# Open-Source_Control_Unitary_V2_R1.net
KiCad netlist of a schematic drawn in EAGLE
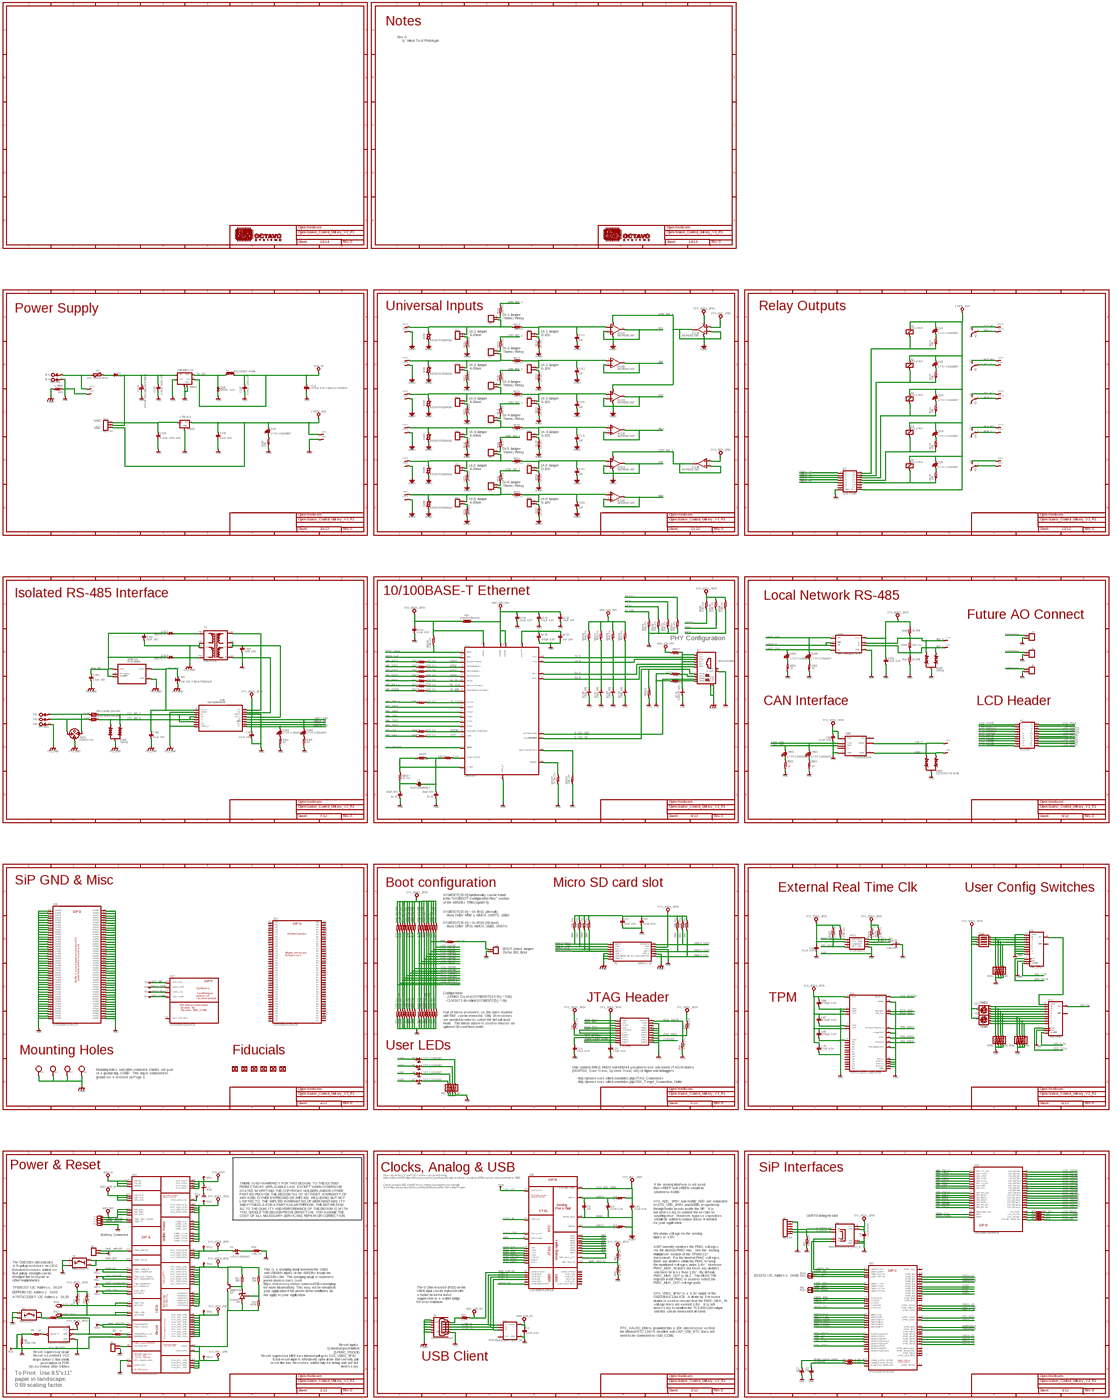
[diagram p0: schematic, sheet 1, overview]
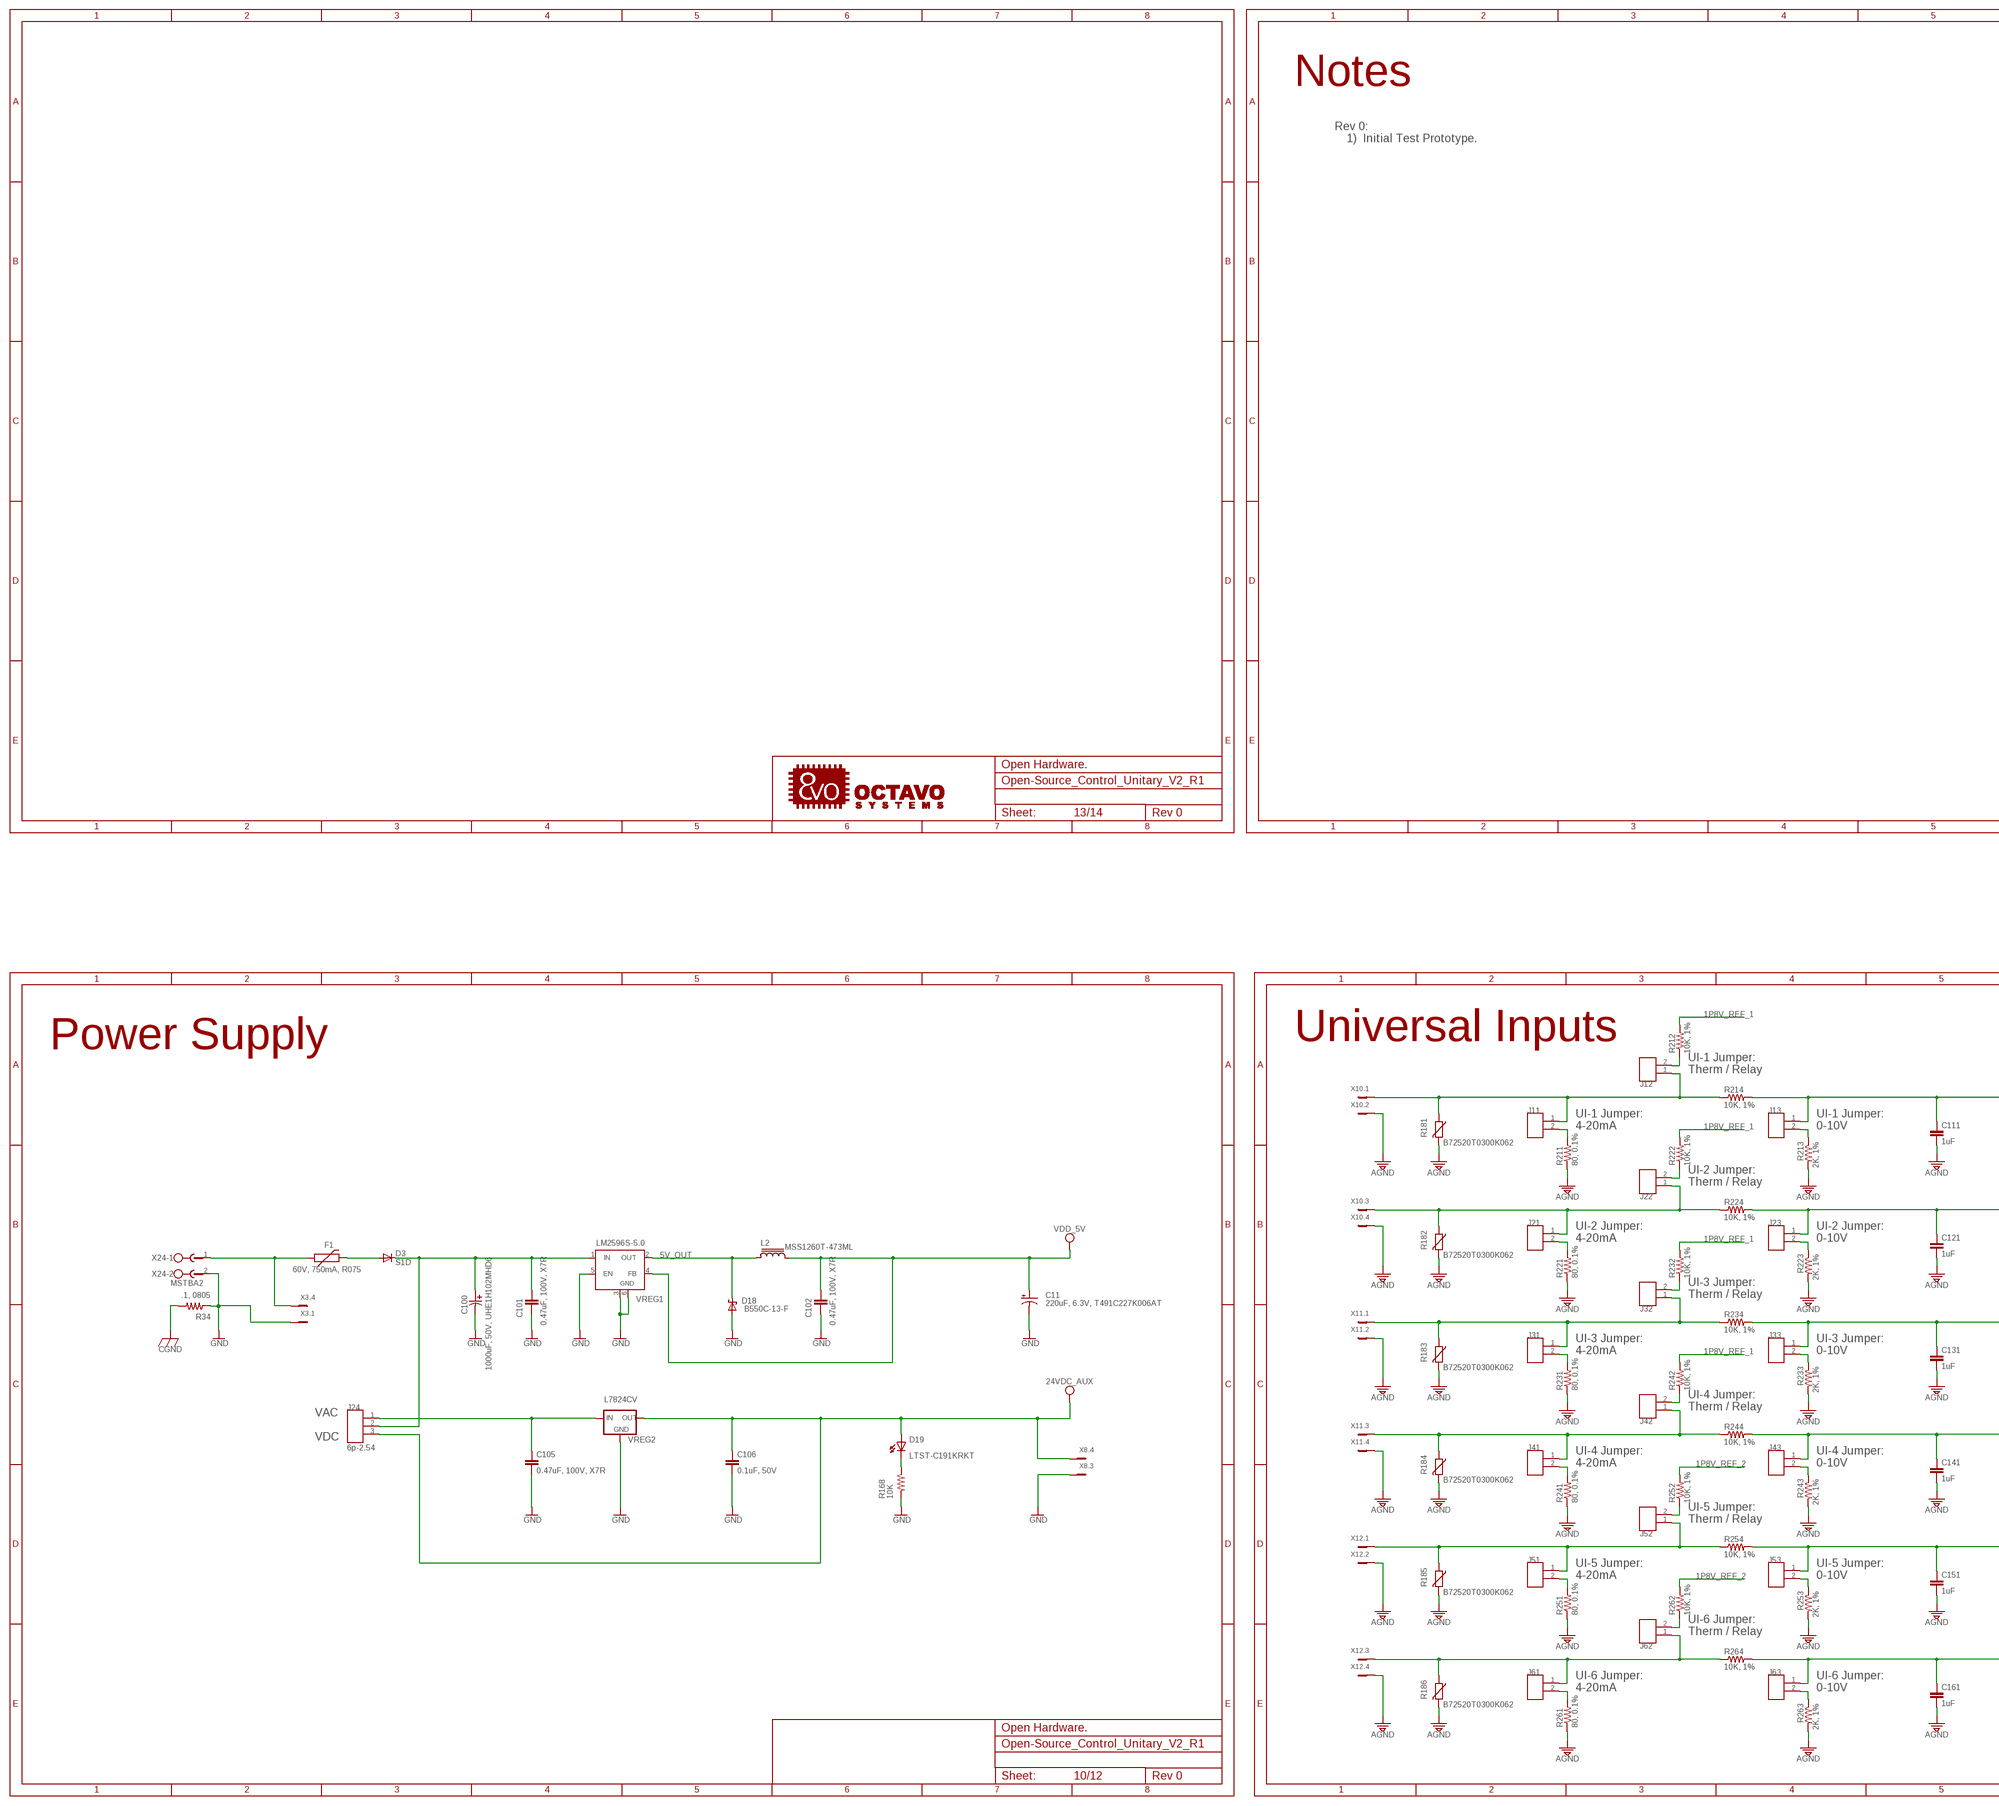
[diagram p1: schematic, sheet 1, part 1 of 6]
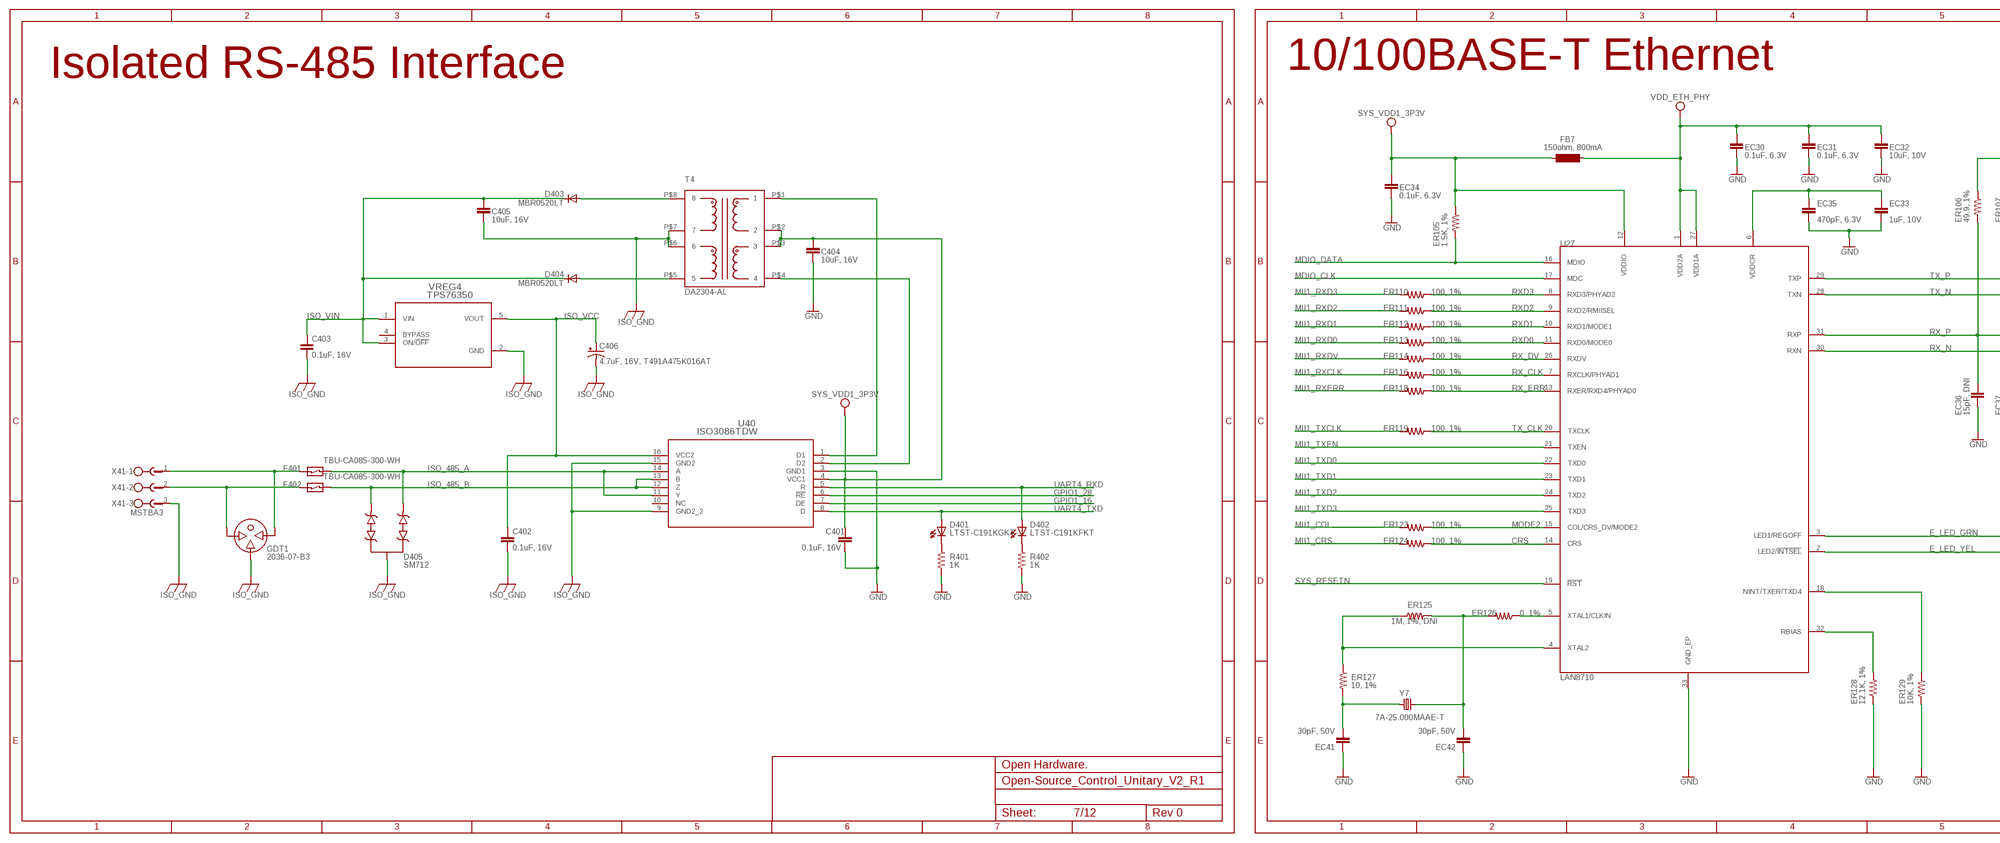
[diagram p2: schematic, sheet 1, part 2 of 6]
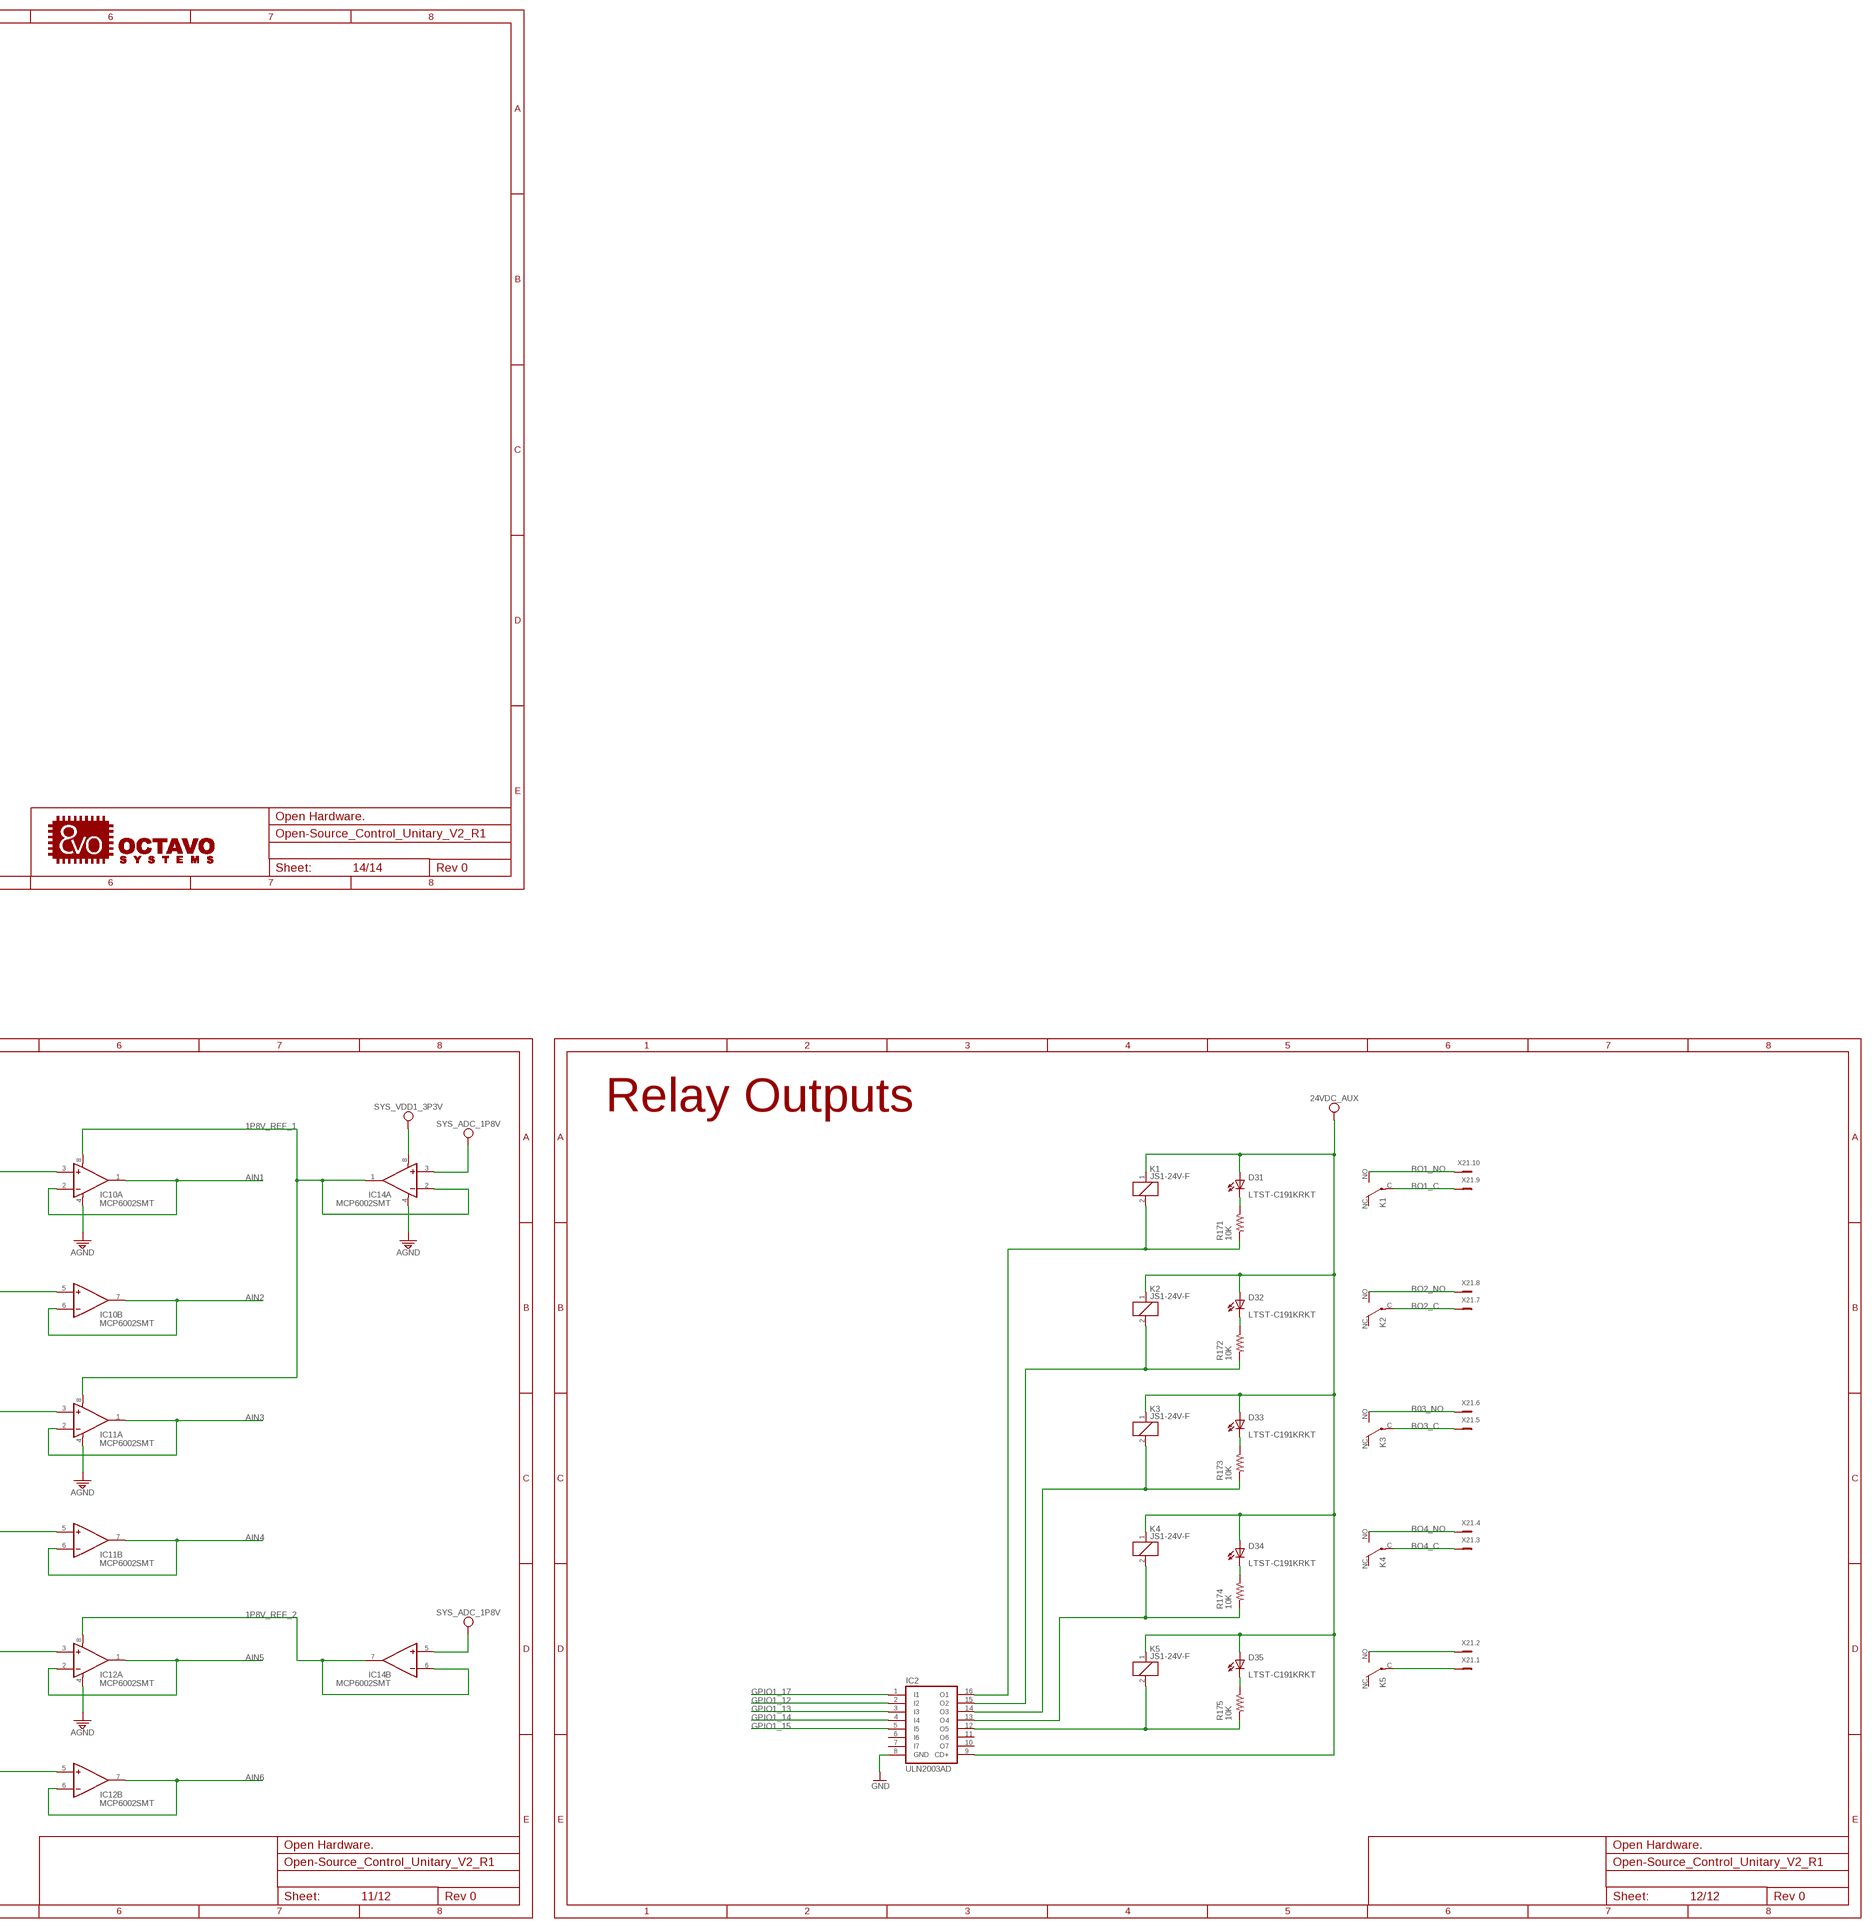
[diagram p3: schematic, sheet 1, part 3 of 6]
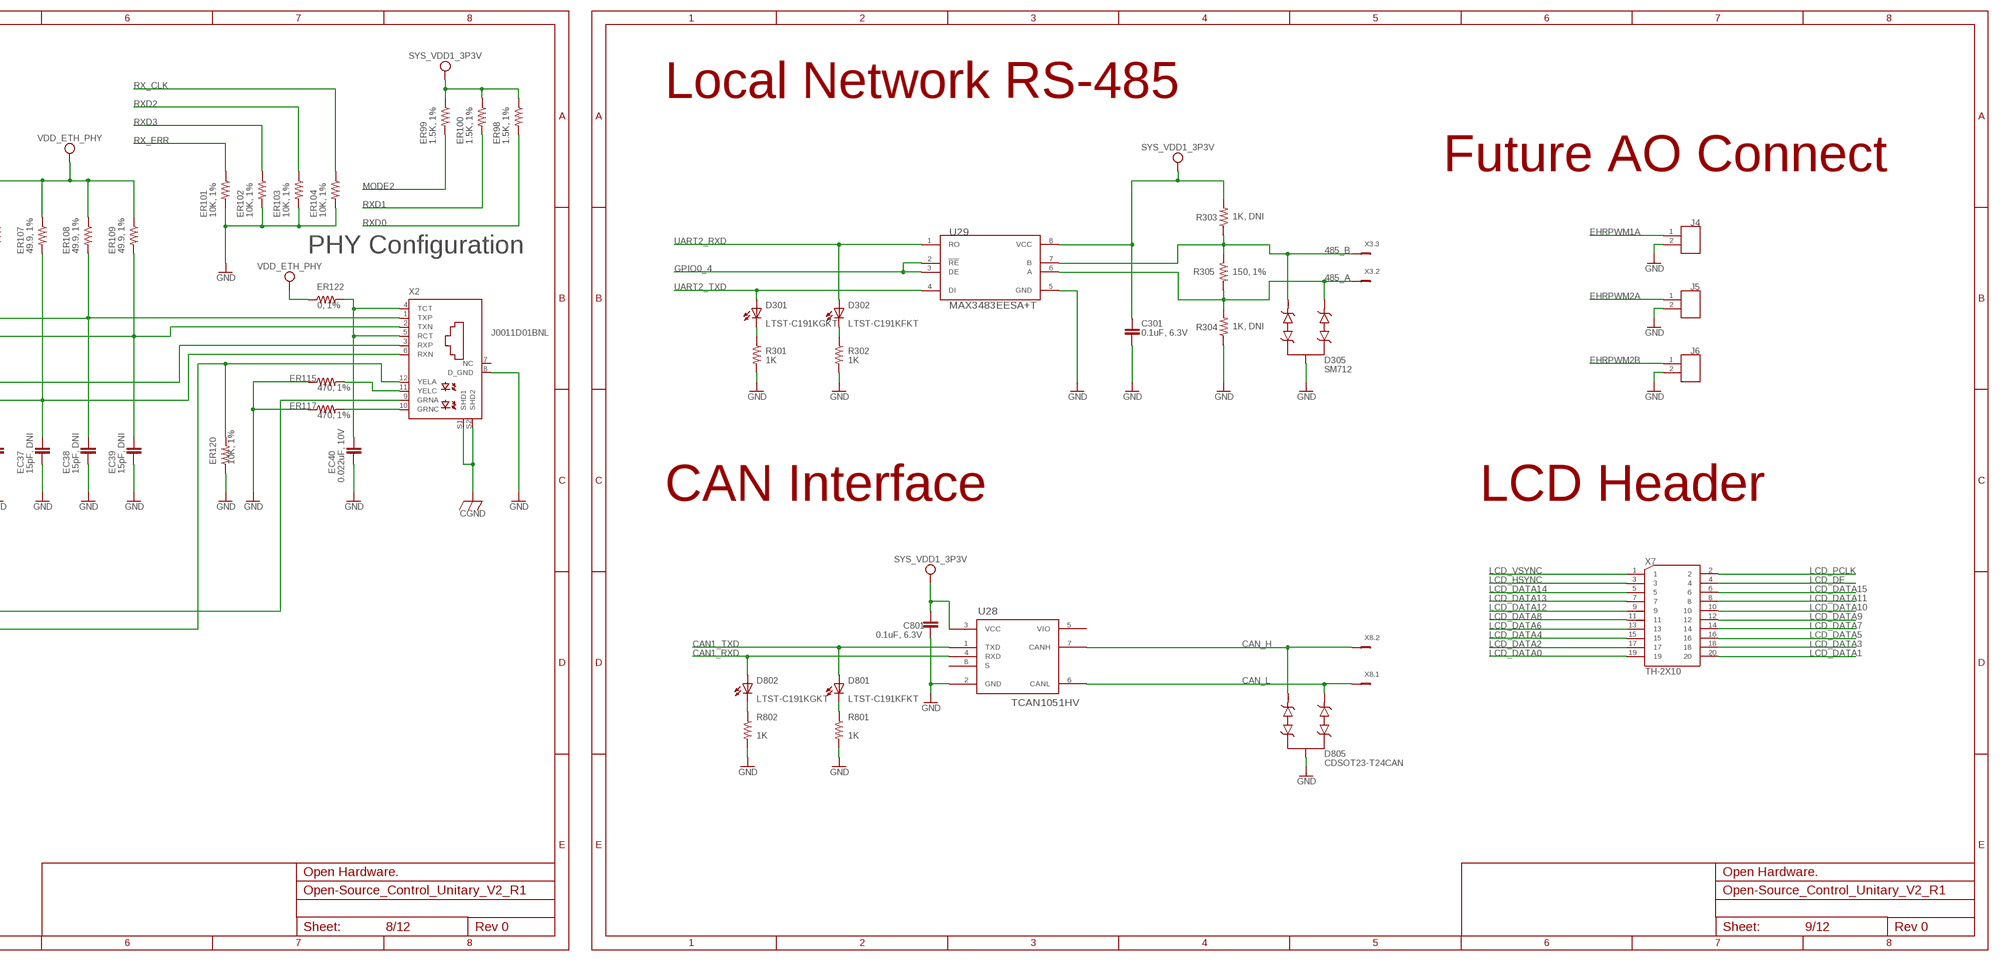
[diagram p4: schematic, sheet 1, part 4 of 6]
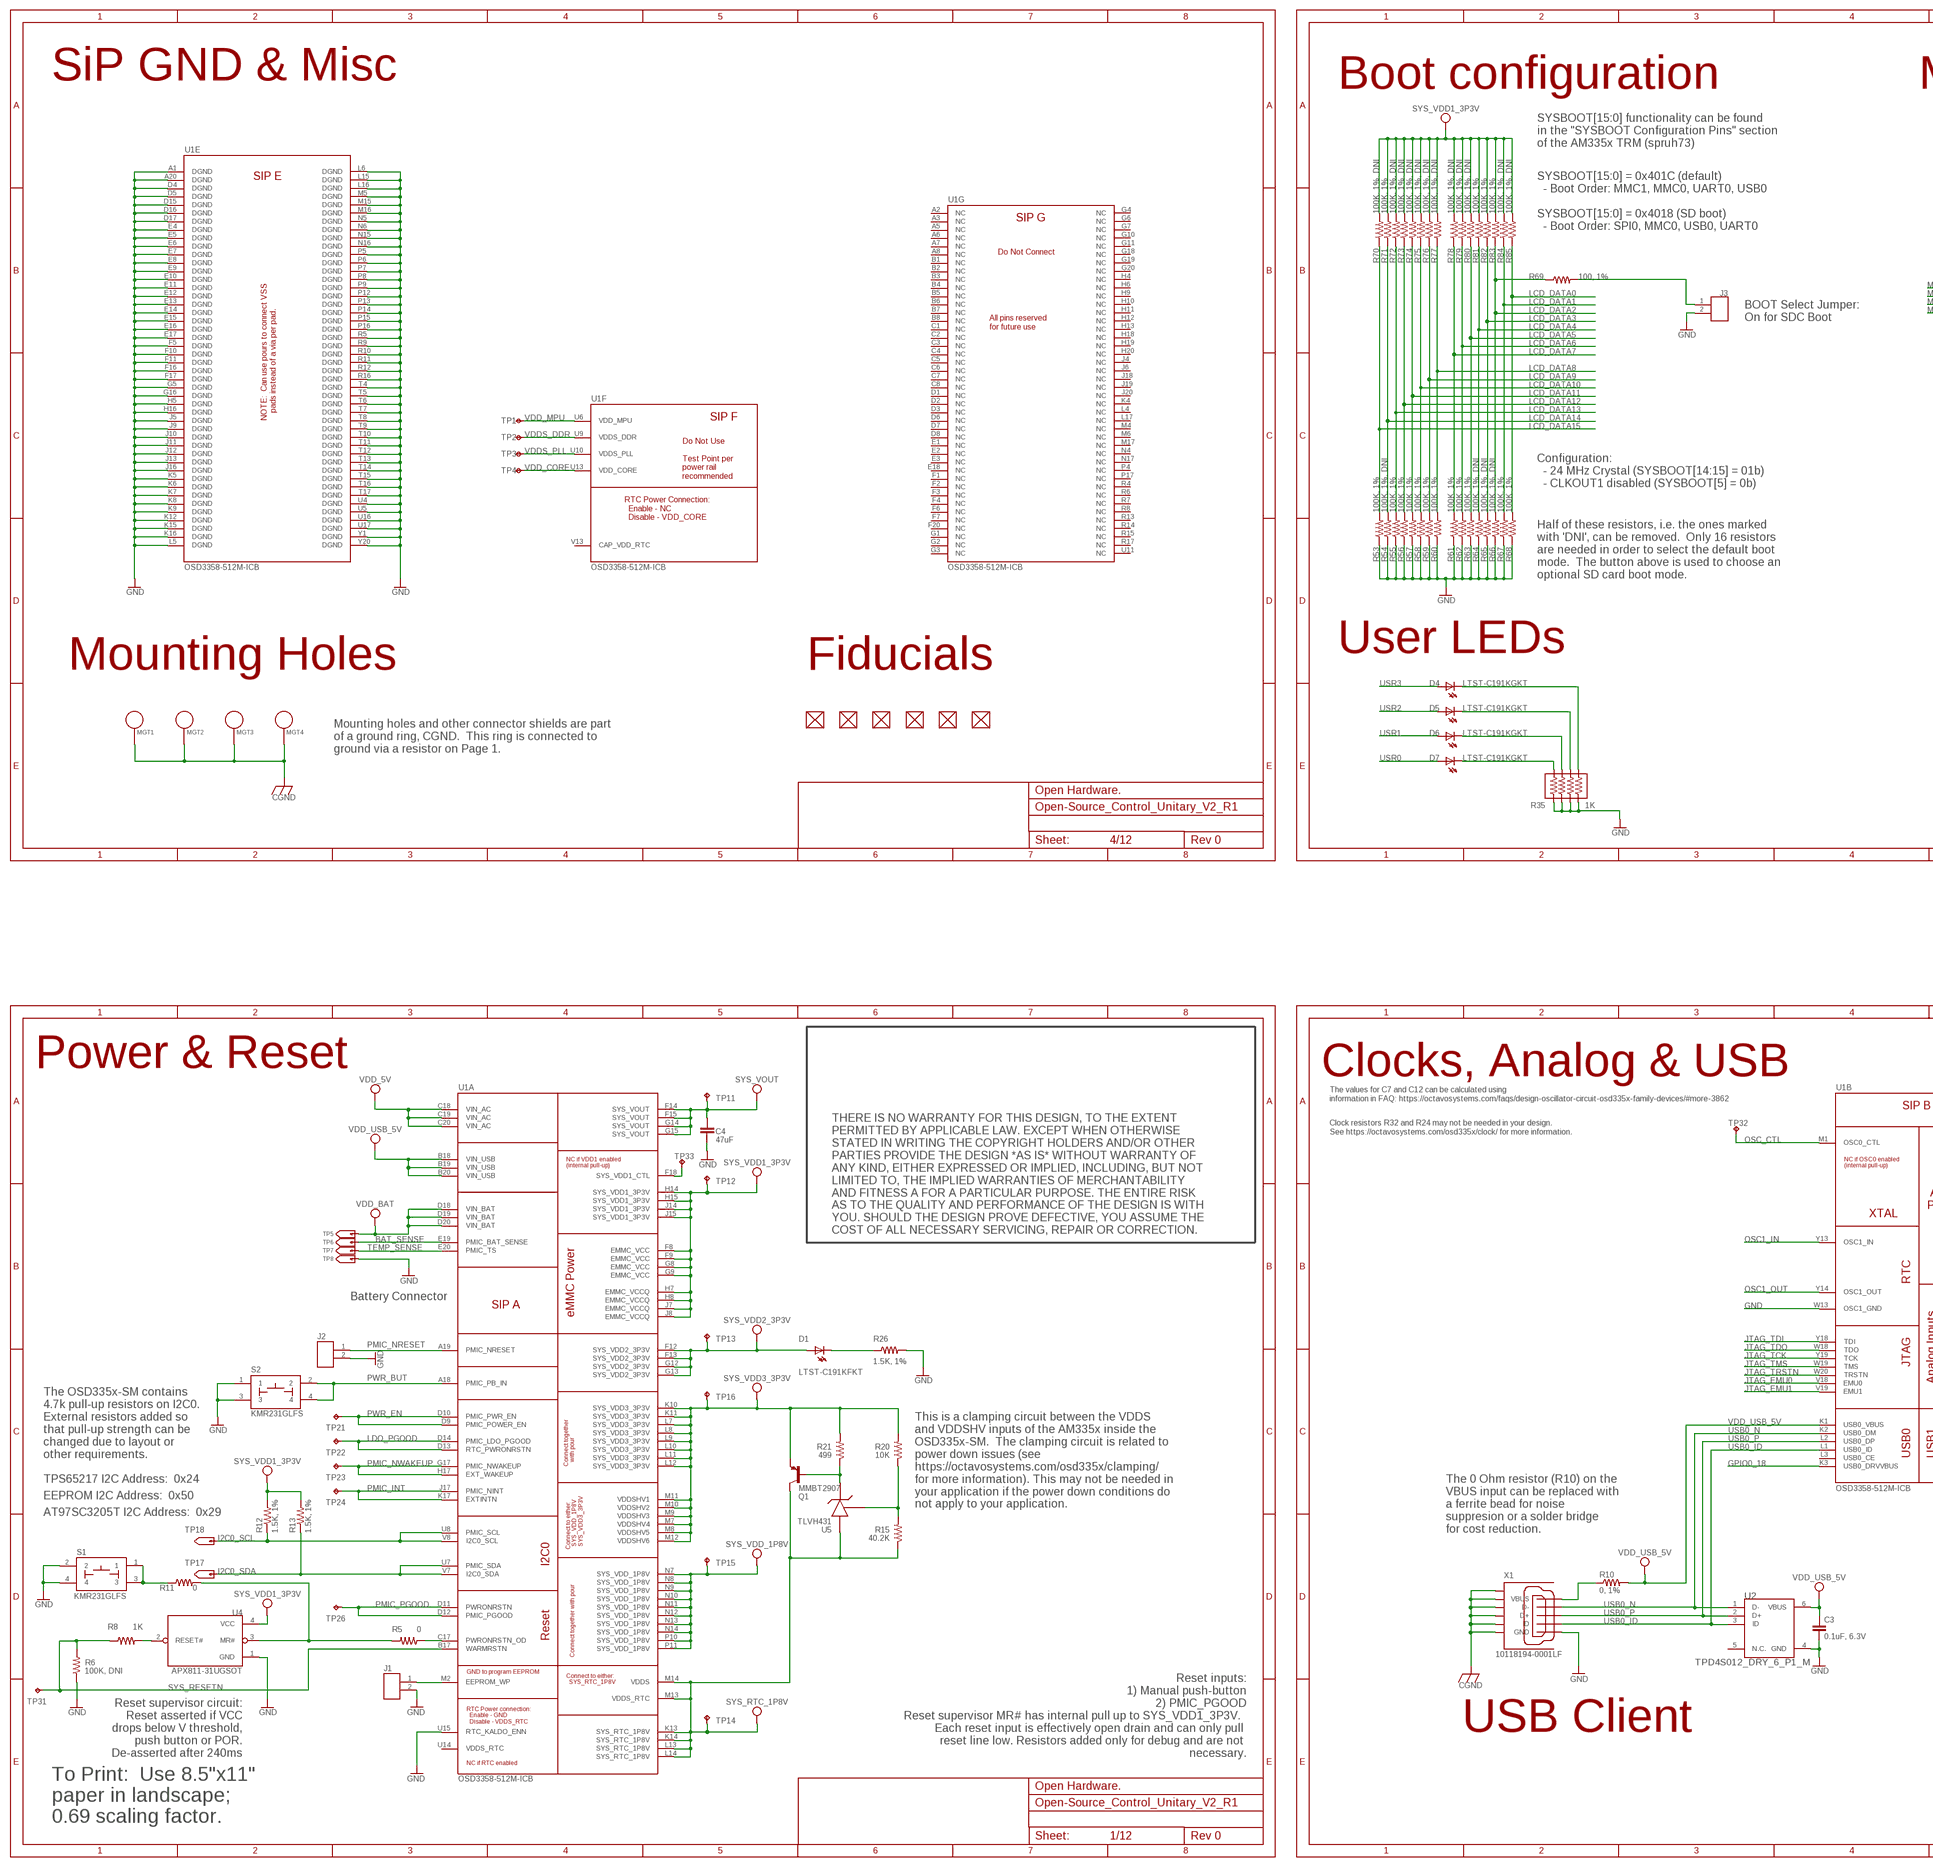
[diagram p5: schematic, sheet 1, part 5 of 6]
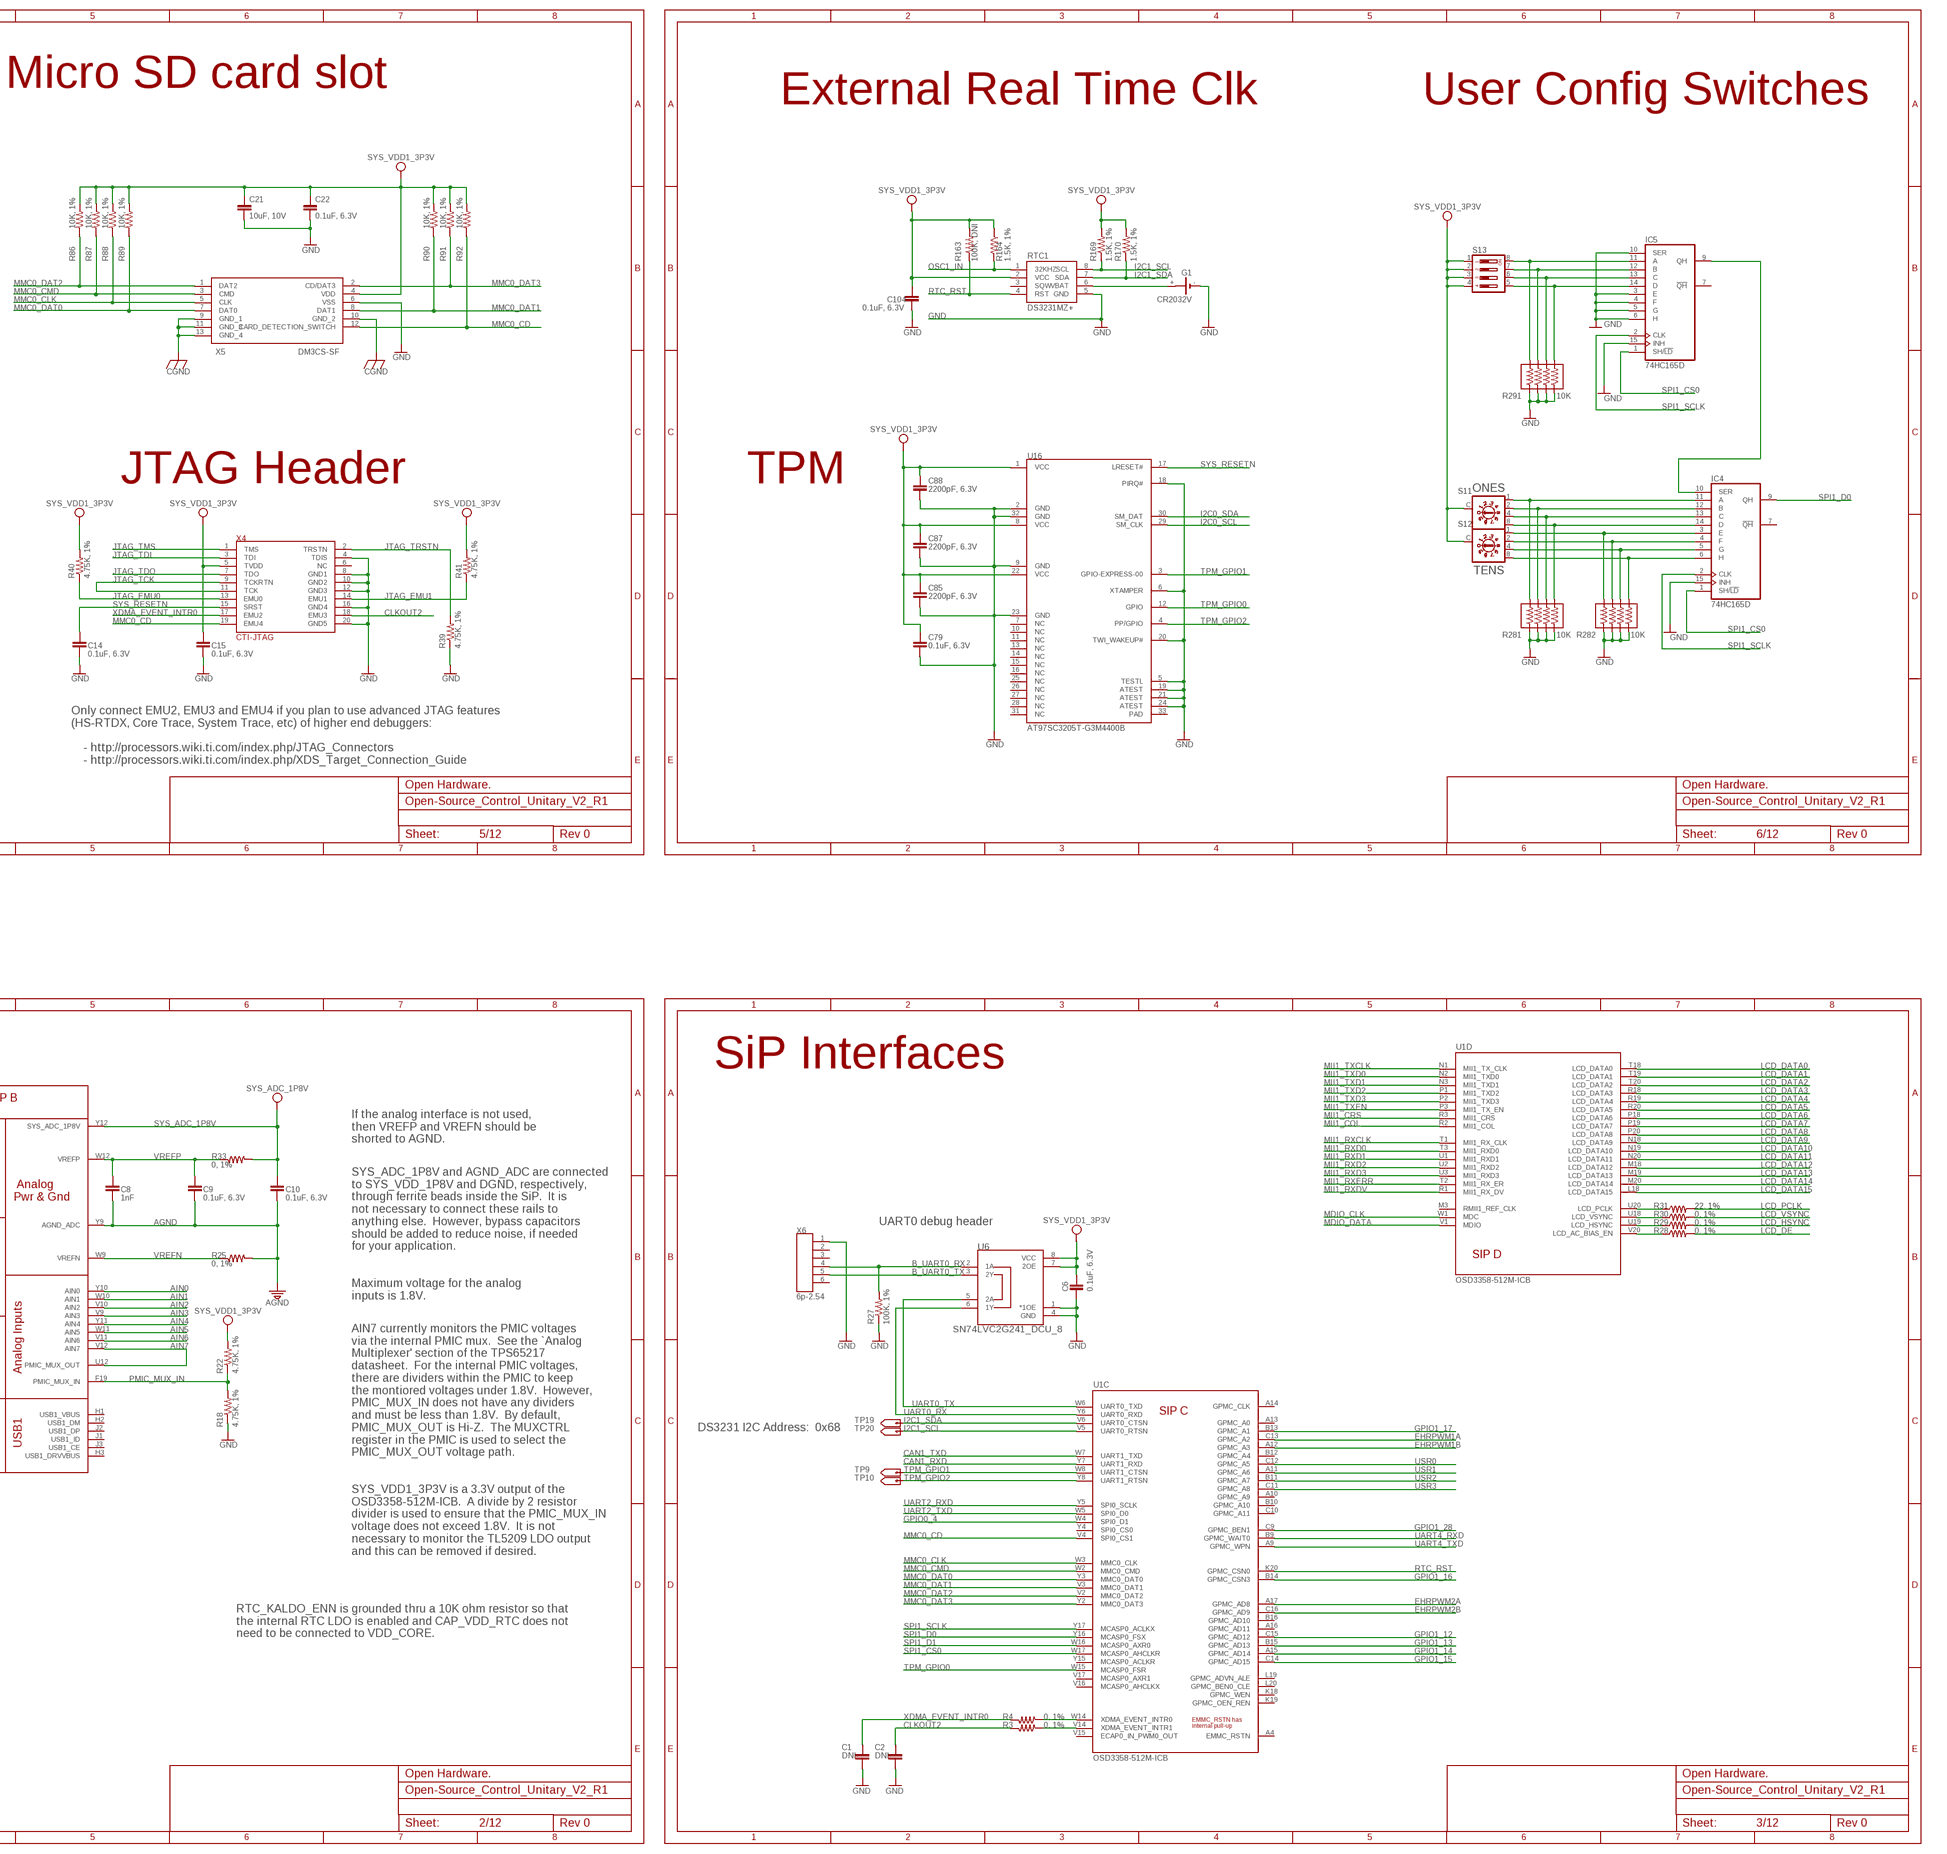
[diagram p6: schematic, sheet 1, part 6 of 6]

(export (version "E")
  (design (tool "Eeschema 10.0.6"))
  (components
    (comp (ref "C1")
      (value "DNI")
      (footprint "eagle-import:C0603")
      (libsource (lib "eagle-import") (part "CC0603"))
    )
    (comp (ref "C2")
      (value "DNI")
      (footprint "eagle-import:C0603")
      (libsource (lib "eagle-import") (part "CC0603"))
    )
    (comp (ref "C3")
      (value "0.1uF, 6.3V")
      (footprint "eagle-import:C0402")
      (libsource (lib "eagle-import") (part "CC0402"))
    )
    (comp (ref "C4")
      (value "47uF")
      (footprint "eagle-import:C0805")
      (libsource (lib "eagle-import") (part "CC0805"))
    )
    (comp (ref "C6")
      (value "0.1uF, 6.3V")
      (footprint "eagle-import:C0402")
      (libsource (lib "eagle-import") (part "CC0402"))
    )
    (comp (ref "C8")
      (value "1nF")
      (footprint "eagle-import:C0402")
      (libsource (lib "eagle-import") (part "CC0402"))
    )
    (comp (ref "C9")
      (value "0.1uF, 6.3V")
      (footprint "eagle-import:C0402")
      (libsource (lib "eagle-import") (part "CC0402"))
    )
    (comp (ref "C10")
      (value "0.1uF, 6.3V")
      (footprint "eagle-import:C0402")
      (libsource (lib "eagle-import") (part "CC0402"))
    )
    (comp (ref "C11")
      (value "220uF, 6.3V, T491C227K006AT")
      (footprint "eagle-import:C_6032-28R")
      (libsource (lib "eagle-import") (part "CPOL-USC/6032-28R"))
    )
    (comp (ref "C14")
      (value "0.1uF, 6.3V")
      (footprint "eagle-import:C0402")
      (libsource (lib "eagle-import") (part "CC0402"))
    )
    (comp (ref "C15")
      (value "0.1uF, 6.3V")
      (footprint "eagle-import:C0402")
      (libsource (lib "eagle-import") (part "CC0402"))
    )
    (comp (ref "C21")
      (value "10uF, 10V")
      (footprint "eagle-import:C0805")
      (libsource (lib "eagle-import") (part "CC0805"))
    )
    (comp (ref "C22")
      (value "0.1uF, 6.3V")
      (footprint "eagle-import:C0402")
      (libsource (lib "eagle-import") (part "CC0402"))
    )
    (comp (ref "C79")
      (value "0.1uF, 6.3V")
      (footprint "eagle-import:C0402")
      (libsource (lib "eagle-import") (part "CC0402"))
    )
    (comp (ref "C85")
      (value "2200pF, 6.3V")
      (footprint "eagle-import:C0402")
      (libsource (lib "eagle-import") (part "CC0402"))
    )
    (comp (ref "C87")
      (value "2200pF, 6.3V")
      (footprint "eagle-import:C0402")
      (libsource (lib "eagle-import") (part "CC0402"))
    )
    (comp (ref "C88")
      (value "2200pF, 6.3V")
      (footprint "eagle-import:C0402")
      (libsource (lib "eagle-import") (part "CC0402"))
    )
    (comp (ref "C100")
      (value "1000uF, 50V, UHE1H102MHD6")
      (footprint "eagle-import:PCAP_16X25-THRU-ELECT")
      (fields (field (name "MANUFACTURER_PART_NUMBER") "UHE1H102MHD6"))
      (libsource (lib "eagle-import") (part "UHE1H102MHD6"))
    )
    (comp (ref "C101")
      (value "0.47uF, 100V, X7R")
      (footprint "eagle-import:1206")
      (libsource (lib "eagle-import") (part "4.7UF-1206-16V-(+80/-20%)"))
    )
    (comp (ref "C102")
      (value "0.47uF, 100V, X7R")
      (footprint "eagle-import:1206")
      (libsource (lib "eagle-import") (part "4.7UF-1206-16V-(+80/-20%)"))
    )
    (comp (ref "C104")
      (value "0.1uF, 6.3V")
      (footprint "eagle-import:C0402")
      (libsource (lib "eagle-import") (part "CC0402"))
    )
    (comp (ref "C105")
      (value "0.47uF, 100V, X7R")
      (footprint "eagle-import:1206")
      (libsource (lib "eagle-import") (part "4.7UF-1206-16V-(+80/-20%)"))
    )
    (comp (ref "C106")
      (value "0.1uF, 50V")
      (footprint "eagle-import:1206")
      (libsource (lib "eagle-import") (part "4.7UF-1206-16V-(+80/-20%)"))
    )
    (comp (ref "C111")
      (value "1uF")
      (footprint "eagle-import:C0805")
      (libsource (lib "eagle-import") (part "CC0805"))
    )
    (comp (ref "C121")
      (value "1uF")
      (footprint "eagle-import:C0805")
      (libsource (lib "eagle-import") (part "CC0805"))
    )
    (comp (ref "C131")
      (value "1uF")
      (footprint "eagle-import:C0805")
      (libsource (lib "eagle-import") (part "CC0805"))
    )
    (comp (ref "C141")
      (value "1uF")
      (footprint "eagle-import:C0805")
      (libsource (lib "eagle-import") (part "CC0805"))
    )
    (comp (ref "C151")
      (value "1uF")
      (footprint "eagle-import:C0805")
      (libsource (lib "eagle-import") (part "CC0805"))
    )
    (comp (ref "C161")
      (value "1uF")
      (footprint "eagle-import:C0805")
      (libsource (lib "eagle-import") (part "CC0805"))
    )
    (comp (ref "C301")
      (value "0.1uF, 6.3V")
      (footprint "eagle-import:C0402")
      (libsource (lib "eagle-import") (part "CC0402"))
    )
    (comp (ref "C401")
      (value "0.1uF, 16V")
      (footprint "eagle-import:C0402")
      (libsource (lib "eagle-import") (part "CC0402"))
    )
    (comp (ref "C402")
      (value "0.1uF, 16V")
      (footprint "eagle-import:C0402")
      (libsource (lib "eagle-import") (part "CC0402"))
    )
    (comp (ref "C403")
      (value "0.1uF, 16V")
      (footprint "eagle-import:C0402")
      (libsource (lib "eagle-import") (part "CC0402"))
    )
    (comp (ref "C404")
      (value "10uF, 16V")
      (footprint "eagle-import:C0805")
      (libsource (lib "eagle-import") (part "CC0805"))
    )
    (comp (ref "C405")
      (value "10uF, 16V")
      (footprint "eagle-import:C0805")
      (libsource (lib "eagle-import") (part "CC0805"))
    )
    (comp (ref "C406")
      (value "4.7uF, 16V, T491A475K016AT")
      (footprint "eagle-import:A_3216-18R")
      (libsource (lib "eagle-import") (part "CPOL-USA/3216-18R"))
    )
    (comp (ref "C801")
      (value "0.1uF, 6.3V")
      (footprint "eagle-import:C0402")
      (libsource (lib "eagle-import") (part "CC0402"))
    )
    (comp (ref "D1")
      (value "LTST-C191KFKT")
      (footprint "eagle-import:EIA-STD")
      (libsource (lib "eagle-import") (part "LTST-C191KFKTLED_EIA-STD"))
    )
    (comp (ref "D3")
      (value "S1D")
      (footprint "eagle-import:SMA")
      (libsource (lib "eagle-import") (part "S1M"))
    )
    (comp (ref "D4")
      (value "LTST-C191KGKT")
      (footprint "eagle-import:EIA-STD")
      (libsource (lib "eagle-import") (part "LTST-C191KGKTLED_EIA-STD"))
    )
    (comp (ref "D5")
      (value "LTST-C191KGKT")
      (footprint "eagle-import:EIA-STD")
      (libsource (lib "eagle-import") (part "LTST-C191KGKTLED_EIA-STD"))
    )
    (comp (ref "D6")
      (value "LTST-C191KGKT")
      (footprint "eagle-import:EIA-STD")
      (libsource (lib "eagle-import") (part "LTST-C191KGKTLED_EIA-STD"))
    )
    (comp (ref "D7")
      (value "LTST-C191KGKT")
      (footprint "eagle-import:EIA-STD")
      (libsource (lib "eagle-import") (part "LTST-C191KGKTLED_EIA-STD"))
    )
    (comp (ref "D18")
      (value "B550C-13-F")
      (footprint "eagle-import:SMC")
      (libsource (lib "eagle-import") (part "B520C-13-F"))
    )
    (comp (ref "D19")
      (value "LTST-C191KRKT")
      (footprint "eagle-import:EIA-STD")
      (libsource (lib "eagle-import") (part "LTST-C191KRKTLED_EIA-STD"))
    )
    (comp (ref "D31")
      (value "LTST-C191KRKT")
      (footprint "eagle-import:EIA-STD")
      (libsource (lib "eagle-import") (part "LTST-C191KRKTLED_EIA-STD"))
    )
    (comp (ref "D32")
      (value "LTST-C191KRKT")
      (footprint "eagle-import:EIA-STD")
      (libsource (lib "eagle-import") (part "LTST-C191KRKTLED_EIA-STD"))
    )
    (comp (ref "D33")
      (value "LTST-C191KRKT")
      (footprint "eagle-import:EIA-STD")
      (libsource (lib "eagle-import") (part "LTST-C191KRKTLED_EIA-STD"))
    )
    (comp (ref "D34")
      (value "LTST-C191KRKT")
      (footprint "eagle-import:EIA-STD")
      (libsource (lib "eagle-import") (part "LTST-C191KRKTLED_EIA-STD"))
    )
    (comp (ref "D35")
      (value "LTST-C191KRKT")
      (footprint "eagle-import:EIA-STD")
      (libsource (lib "eagle-import") (part "LTST-C191KRKTLED_EIA-STD"))
    )
    (comp (ref "D301")
      (value "LTST-C191KGKT")
      (footprint "eagle-import:EIA-STD")
      (libsource (lib "eagle-import") (part "LTST-C191KGKTLED_EIA-STD"))
    )
    (comp (ref "D302")
      (value "LTST-C191KFKT")
      (footprint "eagle-import:EIA-STD")
      (libsource (lib "eagle-import") (part "LTST-C191KFKTLED_EIA-STD"))
    )
    (comp (ref "D305")
      (value "SM712")
      (footprint "eagle-import:SOT23-3")
      (libsource (lib "eagle-import") (part "SM712"))
    )
    (comp (ref "D401")
      (value "LTST-C191KGKT")
      (footprint "eagle-import:EIA-STD")
      (libsource (lib "eagle-import") (part "LTST-C191KGKTLED_EIA-STD"))
    )
    (comp (ref "D402")
      (value "LTST-C191KFKT")
      (footprint "eagle-import:EIA-STD")
      (libsource (lib "eagle-import") (part "LTST-C191KFKTLED_EIA-STD"))
    )
    (comp (ref "D403")
      (value "MBR0520LT")
      (footprint "eagle-import:SOD123")
      (libsource (lib "eagle-import") (part "MBR0520LT"))
    )
    (comp (ref "D404")
      (value "MBR0520LT")
      (footprint "eagle-import:SOD123")
      (libsource (lib "eagle-import") (part "MBR0520LT"))
    )
    (comp (ref "D405")
      (value "SM712")
      (footprint "eagle-import:SOT23-3")
      (libsource (lib "eagle-import") (part "SM712"))
    )
    (comp (ref "D801")
      (value "LTST-C191KFKT")
      (footprint "eagle-import:EIA-STD")
      (libsource (lib "eagle-import") (part "LTST-C191KFKTLED_EIA-STD"))
    )
    (comp (ref "D802")
      (value "LTST-C191KGKT")
      (footprint "eagle-import:EIA-STD")
      (libsource (lib "eagle-import") (part "LTST-C191KGKTLED_EIA-STD"))
    )
    (comp (ref "D805")
      (value "CDSOT23-T24CAN")
      (footprint "eagle-import:SOT23-3")
      (libsource (lib "eagle-import") (part "CDSOT23-T24CAN"))
    )
    (comp (ref "EC30")
      (value "0.1uF, 6.3V")
      (footprint "eagle-import:C0402")
      (libsource (lib "eagle-import") (part "CC0402"))
    )
    (comp (ref "EC31")
      (value "0.1uF, 6.3V")
      (footprint "eagle-import:C0402")
      (libsource (lib "eagle-import") (part "CC0402"))
    )
    (comp (ref "EC32")
      (value "10uF, 10V")
      (footprint "eagle-import:C0805")
      (libsource (lib "eagle-import") (part "CC0805"))
    )
    (comp (ref "EC33")
      (value "1uF, 10V")
      (footprint "eagle-import:C0402")
      (libsource (lib "eagle-import") (part "CC0402"))
    )
    (comp (ref "EC34")
      (value "0.1uF, 6.3V")
      (footprint "eagle-import:C0402")
      (libsource (lib "eagle-import") (part "CC0402"))
    )
    (comp (ref "EC35")
      (value "470pF, 6.3V")
      (footprint "eagle-import:C0402")
      (libsource (lib "eagle-import") (part "CC0402"))
    )
    (comp (ref "EC36")
      (value "15pF, DNI")
      (footprint "eagle-import:C0402")
      (libsource (lib "eagle-import") (part "CC0402"))
    )
    (comp (ref "EC37")
      (value "15pF, DNI")
      (footprint "eagle-import:C0402")
      (libsource (lib "eagle-import") (part "CC0402"))
    )
    (comp (ref "EC38")
      (value "15pF, DNI")
      (footprint "eagle-import:C0402")
      (libsource (lib "eagle-import") (part "CC0402"))
    )
    (comp (ref "EC39")
      (value "15pF, DNI")
      (footprint "eagle-import:C0402")
      (libsource (lib "eagle-import") (part "CC0402"))
    )
    (comp (ref "EC40")
      (value "0.022uF, 10V")
      (footprint "eagle-import:C0402")
      (libsource (lib "eagle-import") (part "CC0402"))
    )
    (comp (ref "EC41")
      (value "30pF, 50V")
      (footprint "eagle-import:C0402")
      (libsource (lib "eagle-import") (part "CC0402"))
    )
    (comp (ref "EC42")
      (value "30pF, 50V")
      (footprint "eagle-import:C0402")
      (libsource (lib "eagle-import") (part "CC0402"))
    )
    (comp (ref "ER98")
      (value "1.5K, 1%")
      (footprint "eagle-import:R0402")
      (libsource (lib "eagle-import") (part "OSD3358-SM-RED Platform_R-US_R0402"))
    )
    (comp (ref "ER99")
      (value "1.5K, 1%")
      (footprint "eagle-import:R0402")
      (libsource (lib "eagle-import") (part "OSD3358-SM-RED Platform_R-US_R0402"))
    )
    (comp (ref "ER100")
      (value "1.5K, 1%")
      (footprint "eagle-import:R0402")
      (libsource (lib "eagle-import") (part "OSD3358-SM-RED Platform_R-US_R0402"))
    )
    (comp (ref "ER101")
      (value "10K, 1%")
      (footprint "eagle-import:R0402")
      (libsource (lib "eagle-import") (part "OSD3358-SM-RED Platform_R-US_R0402"))
    )
    (comp (ref "ER102")
      (value "10K, 1%")
      (footprint "eagle-import:R0402")
      (libsource (lib "eagle-import") (part "OSD3358-SM-RED Platform_R-US_R0402"))
    )
    (comp (ref "ER103")
      (value "10K, 1%")
      (footprint "eagle-import:R0402")
      (libsource (lib "eagle-import") (part "OSD3358-SM-RED Platform_R-US_R0402"))
    )
    (comp (ref "ER104")
      (value "10K, 1%")
      (footprint "eagle-import:R0402")
      (libsource (lib "eagle-import") (part "OSD3358-SM-RED Platform_R-US_R0402"))
    )
    (comp (ref "ER105")
      (value "1.5K, 1%")
      (footprint "eagle-import:R0402")
      (libsource (lib "eagle-import") (part "OSD3358-SM-RED Platform_R-US_R0402"))
    )
    (comp (ref "ER106")
      (value "49.9, 1%")
      (footprint "eagle-import:R0402")
      (libsource (lib "eagle-import") (part "OSD3358-SM-RED Platform_R-US_R0402"))
    )
    (comp (ref "ER107")
      (value "49.9, 1%")
      (footprint "eagle-import:R0402")
      (libsource (lib "eagle-import") (part "OSD3358-SM-RED Platform_R-US_R0402"))
    )
    (comp (ref "ER108")
      (value "49.9, 1%")
      (footprint "eagle-import:R0402")
      (libsource (lib "eagle-import") (part "OSD3358-SM-RED Platform_R-US_R0402"))
    )
    (comp (ref "ER109")
      (value "49.9, 1%")
      (footprint "eagle-import:R0402")
      (libsource (lib "eagle-import") (part "OSD3358-SM-RED Platform_R-US_R0402"))
    )
    (comp (ref "ER110")
      (value "100, 1%")
      (footprint "eagle-import:R0402")
      (libsource (lib "eagle-import") (part "OSD3358-SM-RED Platform_R-US_R0402"))
    )
    (comp (ref "ER111")
      (value "100, 1%")
      (footprint "eagle-import:R0402")
      (libsource (lib "eagle-import") (part "OSD3358-SM-RED Platform_R-US_R0402"))
    )
    (comp (ref "ER112")
      (value "100, 1%")
      (footprint "eagle-import:R0402")
      (libsource (lib "eagle-import") (part "OSD3358-SM-RED Platform_R-US_R0402"))
    )
    (comp (ref "ER113")
      (value "100, 1%")
      (footprint "eagle-import:R0402")
      (libsource (lib "eagle-import") (part "OSD3358-SM-RED Platform_R-US_R0402"))
    )
    (comp (ref "ER114")
      (value "100, 1%")
      (footprint "eagle-import:R0402")
      (libsource (lib "eagle-import") (part "OSD3358-SM-RED Platform_R-US_R0402"))
    )
    (comp (ref "ER115")
      (value "470, 1%")
      (footprint "eagle-import:R0402")
      (libsource (lib "eagle-import") (part "OSD3358-SM-RED Platform_R-US_R0402"))
    )
    (comp (ref "ER116")
      (value "100, 1%")
      (footprint "eagle-import:R0402")
      (libsource (lib "eagle-import") (part "OSD3358-SM-RED Platform_R-US_R0402"))
    )
    (comp (ref "ER117")
      (value "470, 1%")
      (footprint "eagle-import:R0402")
      (libsource (lib "eagle-import") (part "OSD3358-SM-RED Platform_R-US_R0402"))
    )
    (comp (ref "ER118")
      (value "100, 1%")
      (footprint "eagle-import:R0402")
      (libsource (lib "eagle-import") (part "OSD3358-SM-RED Platform_R-US_R0402"))
    )
    (comp (ref "ER119")
      (value "100, 1%")
      (footprint "eagle-import:R0402")
      (libsource (lib "eagle-import") (part "OSD3358-SM-RED Platform_R-US_R0402"))
    )
    (comp (ref "ER120")
      (value "10K, 1%")
      (footprint "eagle-import:R0402")
      (libsource (lib "eagle-import") (part "OSD3358-SM-RED Platform_R-US_R0402"))
    )
    (comp (ref "ER122")
      (value "0, 1%")
      (footprint "eagle-import:R0402")
      (libsource (lib "eagle-import") (part "OSD3358-SM-RED Platform_R-US_R0402"))
    )
    (comp (ref "ER123")
      (value "100, 1%")
      (footprint "eagle-import:R0402")
      (libsource (lib "eagle-import") (part "OSD3358-SM-RED Platform_R-US_R0402"))
    )
    (comp (ref "ER124")
      (value "100, 1%")
      (footprint "eagle-import:R0402")
      (libsource (lib "eagle-import") (part "OSD3358-SM-RED Platform_R-US_R0402"))
    )
    (comp (ref "ER125")
      (value "1M, 1%, DNI")
      (footprint "eagle-import:R0402")
      (libsource (lib "eagle-import") (part "OSD3358-SM-RED Platform_R-US_R0402"))
    )
    (comp (ref "ER126")
      (value "0, 1%")
      (footprint "eagle-import:R0402")
      (libsource (lib "eagle-import") (part "OSD3358-SM-RED Platform_R-US_R0402"))
    )
    (comp (ref "ER127")
      (value "10, 1%")
      (footprint "eagle-import:R0402")
      (libsource (lib "eagle-import") (part "OSD3358-SM-RED Platform_R-US_R0402"))
    )
    (comp (ref "ER128")
      (value "12.1K, 1%")
      (footprint "eagle-import:R0402")
      (libsource (lib "eagle-import") (part "OSD3358-SM-RED Platform_R-US_R0402"))
    )
    (comp (ref "ER129")
      (value "10K, 1%")
      (footprint "eagle-import:R0402")
      (libsource (lib "eagle-import") (part "OSD3358-SM-RED Platform_R-US_R0402"))
    )
    (comp (ref "F1")
      (value "60V, 750mA, R075")
      (footprint "eagle-import:PTH")
      (libsource (lib "eagle-import") (part "PPTC_PTH"))
    )
    (comp (ref "F401")
      (value "TBU-CA085-300-WH")
      (footprint "eagle-import:TBU-CA")
      (libsource (lib "eagle-import") (part "TBU-CA085-300-WH"))
    )
    (comp (ref "F402")
      (value "TBU-CA085-300-WH")
      (footprint "eagle-import:TBU-CA")
      (libsource (lib "eagle-import") (part "TBU-CA085-300-WH"))
    )
    (comp (ref "FB7")
      (value "150ohm, 800mA")
      (footprint "eagle-import:C0805")
      (libsource (lib "eagle-import") (part "BLM21AG151SN1DFB_0805"))
    )
    (comp (ref "FUD1")
      (value "FIDUCIAL")
      (footprint "eagle-import:FIDUCIAL_40MIL")
      (libsource (lib "eagle-import") (part "FIDUCIAL"))
    )
    (comp (ref "FUD2")
      (value "FIDUCIAL")
      (footprint "eagle-import:FIDUCIAL_40MIL")
      (libsource (lib "eagle-import") (part "FIDUCIAL"))
    )
    (comp (ref "FUD3")
      (value "FIDUCIAL")
      (footprint "eagle-import:FIDUCIAL_40MIL")
      (libsource (lib "eagle-import") (part "FIDUCIAL"))
    )
    (comp (ref "FUD4")
      (value "FIDUCIAL")
      (footprint "eagle-import:FIDUCIAL_40MIL")
      (libsource (lib "eagle-import") (part "FIDUCIAL"))
    )
    (comp (ref "FUD5")
      (value "FIDUCIAL")
      (footprint "eagle-import:FIDUCIAL_40MIL")
      (libsource (lib "eagle-import") (part "FIDUCIAL"))
    )
    (comp (ref "FUD6")
      (value "FIDUCIAL")
      (footprint "eagle-import:FIDUCIAL_40MIL")
      (libsource (lib "eagle-import") (part "FIDUCIAL"))
    )
    (comp (ref "G1")
      (value "CR2032V")
      (footprint "eagle-import:CR2032V")
      (libsource (lib "eagle-import") (part "CR2032V"))
    )
    (comp (ref "GDT1")
      (value "2036-07-B3")
      (footprint "eagle-import:2036-XX-B3")
      (libsource (lib "eagle-import") (part "2036-09-B3"))
    )
    (comp (ref "IC2")
      (value "ULN2003AD")
      (footprint "eagle-import:SO16")
      (libsource (lib "eagle-import") (part "ULN2003AD"))
    )
    (comp (ref "IC4")
      (value "74HC165D")
      (footprint "eagle-import:SO16")
      (libsource (lib "eagle-import") (part "74165DHC"))
    )
    (comp (ref "IC5")
      (value "74HC165D")
      (footprint "eagle-import:SO16")
      (libsource (lib "eagle-import") (part "74165DHC"))
    )
    (comp (ref "IC10")
      (value "MCP6002SMT")
      (footprint "eagle-import:SOIC8")
      (libsource (lib "eagle-import") (part "MCP6002SMT"))
    )
    (comp (ref "IC11")
      (value "MCP6002SMT")
      (footprint "eagle-import:SOIC8")
      (libsource (lib "eagle-import") (part "MCP6002SMT"))
    )
    (comp (ref "IC12")
      (value "MCP6002SMT")
      (footprint "eagle-import:SOIC8")
      (libsource (lib "eagle-import") (part "MCP6002SMT"))
    )
    (comp (ref "IC14")
      (value "MCP6002SMT")
      (footprint "eagle-import:SOIC8")
      (libsource (lib "eagle-import") (part "MCP6002SMT"))
    )
    (comp (ref "J1")
      (value "826646-2")
      (footprint "eagle-import:H2-2.54")
      (libsource (lib "eagle-import") (part "826646-2"))
    )
    (comp (ref "J2")
      (value "826646-2")
      (footprint "eagle-import:H2-2.54")
      (libsource (lib "eagle-import") (part "OSD3358-SM-RED Platform_826646-2"))
    )
    (comp (ref "J3")
      (value "826646-2")
      (footprint "eagle-import:H2-2.54")
      (libsource (lib "eagle-import") (part "OSD3358-SM-RED Platform_826646-2"))
    )
    (comp (ref "J4")
      (value "826646-2")
      (footprint "eagle-import:H2-2.54")
      (libsource (lib "eagle-import") (part "OSD3358-SM-RED Platform_826646-2"))
    )
    (comp (ref "J5")
      (value "826646-2")
      (footprint "eagle-import:H2-2.54")
      (libsource (lib "eagle-import") (part "OSD3358-SM-RED Platform_826646-2"))
    )
    (comp (ref "J6")
      (value "826646-2")
      (footprint "eagle-import:H2-2.54")
      (libsource (lib "eagle-import") (part "OSD3358-SM-RED Platform_826646-2"))
    )
    (comp (ref "J11")
      (value "826646-2")
      (footprint "eagle-import:H2-2.54")
      (libsource (lib "eagle-import") (part "OSD3358-SM-RED Platform_826646-2"))
    )
    (comp (ref "J12")
      (value "826646-2")
      (footprint "eagle-import:H2-2.54")
      (libsource (lib "eagle-import") (part "OSD3358-SM-RED Platform_826646-2"))
    )
    (comp (ref "J13")
      (value "826646-2")
      (footprint "eagle-import:H2-2.54")
      (libsource (lib "eagle-import") (part "OSD3358-SM-RED Platform_826646-2"))
    )
    (comp (ref "J21")
      (value "826646-2")
      (footprint "eagle-import:H2-2.54")
      (libsource (lib "eagle-import") (part "OSD3358-SM-RED Platform_826646-2"))
    )
    (comp (ref "J22")
      (value "826646-2")
      (footprint "eagle-import:H2-2.54")
      (libsource (lib "eagle-import") (part "OSD3358-SM-RED Platform_826646-2"))
    )
    (comp (ref "J23")
      (value "826646-2")
      (footprint "eagle-import:H2-2.54")
      (libsource (lib "eagle-import") (part "OSD3358-SM-RED Platform_826646-2"))
    )
    (comp (ref "J24")
      (value "6p-2.54")
      (footprint "eagle-import:H3-2.54")
      (fields (field (name "MPN") "P125-1106A1BS116A1"))
      (libsource (lib "eagle-import") (part "826646-3"))
    )
    (comp (ref "J31")
      (value "826646-2")
      (footprint "eagle-import:H2-2.54")
      (libsource (lib "eagle-import") (part "OSD3358-SM-RED Platform_826646-2"))
    )
    (comp (ref "J32")
      (value "826646-2")
      (footprint "eagle-import:H2-2.54")
      (libsource (lib "eagle-import") (part "OSD3358-SM-RED Platform_826646-2"))
    )
    (comp (ref "J33")
      (value "826646-2")
      (footprint "eagle-import:H2-2.54")
      (libsource (lib "eagle-import") (part "OSD3358-SM-RED Platform_826646-2"))
    )
    (comp (ref "J41")
      (value "826646-2")
      (footprint "eagle-import:H2-2.54")
      (libsource (lib "eagle-import") (part "OSD3358-SM-RED Platform_826646-2"))
    )
    (comp (ref "J42")
      (value "826646-2")
      (footprint "eagle-import:H2-2.54")
      (libsource (lib "eagle-import") (part "OSD3358-SM-RED Platform_826646-2"))
    )
    (comp (ref "J43")
      (value "826646-2")
      (footprint "eagle-import:H2-2.54")
      (libsource (lib "eagle-import") (part "OSD3358-SM-RED Platform_826646-2"))
    )
    (comp (ref "J51")
      (value "826646-2")
      (footprint "eagle-import:H2-2.54")
      (libsource (lib "eagle-import") (part "OSD3358-SM-RED Platform_826646-2"))
    )
    (comp (ref "J52")
      (value "826646-2")
      (footprint "eagle-import:H2-2.54")
      (libsource (lib "eagle-import") (part "OSD3358-SM-RED Platform_826646-2"))
    )
    (comp (ref "J53")
      (value "826646-2")
      (footprint "eagle-import:H2-2.54")
      (libsource (lib "eagle-import") (part "OSD3358-SM-RED Platform_826646-2"))
    )
    (comp (ref "J61")
      (value "826646-2")
      (footprint "eagle-import:H2-2.54")
      (libsource (lib "eagle-import") (part "OSD3358-SM-RED Platform_826646-2"))
    )
    (comp (ref "J62")
      (value "826646-2")
      (footprint "eagle-import:H2-2.54")
      (libsource (lib "eagle-import") (part "OSD3358-SM-RED Platform_826646-2"))
    )
    (comp (ref "J63")
      (value "826646-2")
      (footprint "eagle-import:H2-2.54")
      (libsource (lib "eagle-import") (part "OSD3358-SM-RED Platform_826646-2"))
    )
    (comp (ref "K1")
      (value "JS1-24V-F")
      (footprint "eagle-import:JS-M")
      (fields (field (name "MF") "FARNELL") (field (name "MPN") "JSM1-12V-5"))
      (libsource (lib "eagle-import") (part "JS-M1-12V-5"))
    )
    (comp (ref "K2")
      (value "JS1-24V-F")
      (footprint "eagle-import:JS-M")
      (fields (field (name "MF") "FARNELL") (field (name "MPN") "JSM1-12V-5"))
      (libsource (lib "eagle-import") (part "JS-M1-12V-5"))
    )
    (comp (ref "K3")
      (value "JS1-24V-F")
      (footprint "eagle-import:JS-M")
      (fields (field (name "MF") "FARNELL") (field (name "MPN") "JSM1-12V-5"))
      (libsource (lib "eagle-import") (part "JS-M1-12V-5"))
    )
    (comp (ref "K4")
      (value "JS1-24V-F")
      (footprint "eagle-import:JS-M")
      (fields (field (name "MF") "FARNELL") (field (name "MPN") "JSM1-12V-5"))
      (libsource (lib "eagle-import") (part "JS-M1-12V-5"))
    )
    (comp (ref "K5")
      (value "JS1-24V-F")
      (footprint "eagle-import:JS-M")
      (fields (field (name "MF") "FARNELL") (field (name "MPN") "JSM1-12V-5"))
      (libsource (lib "eagle-import") (part "JS-M1-12V-5"))
    )
    (comp (ref "L2")
      (value "MSS1260T-473ML")
      (footprint "eagle-import:MSS1260")
      (libsource (lib "eagle-import") (part "MSS1260"))
    )
    (comp (ref "MGT1")
      (value "MOUNTING_HOLE")
      (footprint "eagle-import:MOUNTING_HOLE")
      (libsource (lib "eagle-import") (part "MOUNTING_HOLE"))
    )
    (comp (ref "MGT2")
      (value "MOUNTING_HOLE")
      (footprint "eagle-import:MOUNTING_HOLE")
      (libsource (lib "eagle-import") (part "MOUNTING_HOLE"))
    )
    (comp (ref "MGT3")
      (value "MOUNTING_HOLE")
      (footprint "eagle-import:MOUNTING_HOLE")
      (libsource (lib "eagle-import") (part "MOUNTING_HOLE"))
    )
    (comp (ref "MGT4")
      (value "MOUNTING_HOLE")
      (footprint "eagle-import:MOUNTING_HOLE")
      (libsource (lib "eagle-import") (part "MOUNTING_HOLE"))
    )
    (comp (ref "Q1")
      (value "MMBT2907")
      (footprint "eagle-import:SOT23-BEC")
      (libsource (lib "eagle-import") (part "MMBT2907SMD"))
    )
    (comp (ref "R3")
      (value "0, 1%")
      (footprint "eagle-import:R0402")
      (libsource (lib "eagle-import") (part "OSD3358-SM-RED Platform_R-US_R0402"))
    )
    (comp (ref "R4")
      (value "0, 1%")
      (footprint "eagle-import:R0402")
      (libsource (lib "eagle-import") (part "OSD3358-SM-RED Platform_R-US_R0402"))
    )
    (comp (ref "R5")
      (value "0")
      (footprint "eagle-import:R0402")
      (libsource (lib "eagle-import") (part "R-US_R0402"))
    )
    (comp (ref "R6")
      (value "100K, DNI")
      (footprint "eagle-import:R0402")
      (libsource (lib "eagle-import") (part "R-US_R0402"))
    )
    (comp (ref "R8")
      (value "1K")
      (footprint "eagle-import:R0402")
      (libsource (lib "eagle-import") (part "R-US_R0402"))
    )
    (comp (ref "R10")
      (value "0, 1%")
      (footprint "eagle-import:R0805")
      (libsource (lib "eagle-import") (part "OSD3358-SM-RED Platform_R-US_R0805"))
    )
    (comp (ref "R11")
      (value "0")
      (footprint "eagle-import:R0402")
      (libsource (lib "eagle-import") (part "R-US_R0402"))
    )
    (comp (ref "R12")
      (value "1.5K, 1%")
      (footprint "eagle-import:R0402")
      (libsource (lib "eagle-import") (part "OSD3358-SM-RED Platform_R-US_R0402"))
    )
    (comp (ref "R13")
      (value "1.5K, 1%")
      (footprint "eagle-import:R0402")
      (libsource (lib "eagle-import") (part "OSD3358-SM-RED Platform_R-US_R0402"))
    )
    (comp (ref "R15")
      (value "40.2K")
      (footprint "eagle-import:R0402")
      (libsource (lib "eagle-import") (part "R-US_R0402"))
    )
    (comp (ref "R18")
      (value "4.75K, 1%")
      (footprint "eagle-import:R0402")
      (libsource (lib "eagle-import") (part "OSD3358-SM-RED Platform_R-US_R0402"))
    )
    (comp (ref "R20")
      (value "10K")
      (footprint "eagle-import:R0402")
      (libsource (lib "eagle-import") (part "R-US_R0402"))
    )
    (comp (ref "R21")
      (value "499")
      (footprint "eagle-import:R0402")
      (libsource (lib "eagle-import") (part "R-US_R0402"))
    )
    (comp (ref "R22")
      (value "4.75K, 1%")
      (footprint "eagle-import:R0402")
      (libsource (lib "eagle-import") (part "OSD3358-SM-RED Platform_R-US_R0402"))
    )
    (comp (ref "R25")
      (value "0, 1%")
      (footprint "eagle-import:R0402")
      (libsource (lib "eagle-import") (part "OSD3358-SM-RED Platform_R-US_R0402"))
    )
    (comp (ref "R26")
      (value "1.5K, 1%")
      (footprint "eagle-import:R0402")
      (libsource (lib "eagle-import") (part "OSD3358-SM-RED Platform_R-US_R0402"))
    )
    (comp (ref "R27")
      (value "100K, 1%")
      (footprint "eagle-import:R0402")
      (libsource (lib "eagle-import") (part "OSD3358-SM-RED Platform_R-US_R0402"))
    )
    (comp (ref "R28")
      (value "0, 1%")
      (footprint "eagle-import:R0402")
      (libsource (lib "eagle-import") (part "OSD3358-SM-RED Platform_R-US_R0402"))
    )
    (comp (ref "R29")
      (value "0, 1%")
      (footprint "eagle-import:R0402")
      (libsource (lib "eagle-import") (part "OSD3358-SM-RED Platform_R-US_R0402"))
    )
    (comp (ref "R30")
      (value "0, 1%")
      (footprint "eagle-import:R0402")
      (libsource (lib "eagle-import") (part "OSD3358-SM-RED Platform_R-US_R0402"))
    )
    (comp (ref "R31")
      (value "22, 1%")
      (footprint "eagle-import:R0402")
      (libsource (lib "eagle-import") (part "OSD3358-SM-RED Platform_R-US_R0402"))
    )
    (comp (ref "R33")
      (value "0, 1%")
      (footprint "eagle-import:R0402")
      (libsource (lib "eagle-import") (part "OSD3358-SM-RED Platform_R-US_R0402"))
    )
    (comp (ref "R34")
      (value ".1, 0805")
      (footprint "eagle-import:R0805")
      (libsource (lib "eagle-import") (part "OSD3358-SM-RED Platform_R-US_R0805"))
    )
    (comp (ref "R35")
      (value "1K")
      (footprint "eagle-import:RN0804")
      (libsource (lib "eagle-import") (part "RESISTOR.NETWORK-(4)"))
    )
    (comp (ref "R39")
      (value "4.75K, 1%")
      (footprint "eagle-import:R0402")
      (libsource (lib "eagle-import") (part "OSD3358-SM-RED Platform_R-US_R0402"))
    )
    (comp (ref "R40")
      (value "4.75K, 1%")
      (footprint "eagle-import:R0402")
      (libsource (lib "eagle-import") (part "OSD3358-SM-RED Platform_R-US_R0402"))
    )
    (comp (ref "R41")
      (value "4.75K, 1%")
      (footprint "eagle-import:R0402")
      (libsource (lib "eagle-import") (part "OSD3358-SM-RED Platform_R-US_R0402"))
    )
    (comp (ref "R53")
      (value "100K, 1%")
      (footprint "eagle-import:R0402")
      (libsource (lib "eagle-import") (part "OSD3358-SM-RED Platform_R-US_R0402"))
    )
    (comp (ref "R54")
      (value "100K, 1%, DNI")
      (footprint "eagle-import:R0402")
      (libsource (lib "eagle-import") (part "OSD3358-SM-RED Platform_R-US_R0402"))
    )
    (comp (ref "R55")
      (value "100K, 1%")
      (footprint "eagle-import:R0402")
      (libsource (lib "eagle-import") (part "OSD3358-SM-RED Platform_R-US_R0402"))
    )
    (comp (ref "R56")
      (value "100K, 1%")
      (footprint "eagle-import:R0402")
      (libsource (lib "eagle-import") (part "OSD3358-SM-RED Platform_R-US_R0402"))
    )
    (comp (ref "R57")
      (value "100K, 1%")
      (footprint "eagle-import:R0402")
      (libsource (lib "eagle-import") (part "OSD3358-SM-RED Platform_R-US_R0402"))
    )
    (comp (ref "R58")
      (value "100K, 1%")
      (footprint "eagle-import:R0402")
      (libsource (lib "eagle-import") (part "OSD3358-SM-RED Platform_R-US_R0402"))
    )
    (comp (ref "R59")
      (value "100K, 1%")
      (footprint "eagle-import:R0402")
      (libsource (lib "eagle-import") (part "OSD3358-SM-RED Platform_R-US_R0402"))
    )
    (comp (ref "R60")
      (value "100K, 1%")
      (footprint "eagle-import:R0402")
      (libsource (lib "eagle-import") (part "OSD3358-SM-RED Platform_R-US_R0402"))
    )
    (comp (ref "R61")
      (value "100K, 1%")
      (footprint "eagle-import:R0402")
      (libsource (lib "eagle-import") (part "OSD3358-SM-RED Platform_R-US_R0402"))
    )
    (comp (ref "R62")
      (value "100K, 1%")
      (footprint "eagle-import:R0402")
      (libsource (lib "eagle-import") (part "OSD3358-SM-RED Platform_R-US_R0402"))
    )
    (comp (ref "R63")
      (value "100K, 1%")
      (footprint "eagle-import:R0402")
      (libsource (lib "eagle-import") (part "OSD3358-SM-RED Platform_R-US_R0402"))
    )
    (comp (ref "R64")
      (value "100K, 1%, DNI")
      (footprint "eagle-import:R0402")
      (libsource (lib "eagle-import") (part "OSD3358-SM-RED Platform_R-US_R0402"))
    )
    (comp (ref "R65")
      (value "100K, 1%, DNI")
      (footprint "eagle-import:R0402")
      (libsource (lib "eagle-import") (part "OSD3358-SM-RED Platform_R-US_R0402"))
    )
    (comp (ref "R66")
      (value "100K, 1%, DNI")
      (footprint "eagle-import:R0402")
      (libsource (lib "eagle-import") (part "OSD3358-SM-RED Platform_R-US_R0402"))
    )
    (comp (ref "R67")
      (value "100K, 1%")
      (footprint "eagle-import:R0402")
      (libsource (lib "eagle-import") (part "OSD3358-SM-RED Platform_R-US_R0402"))
    )
    (comp (ref "R68")
      (value "100K, 1%")
      (footprint "eagle-import:R0402")
      (libsource (lib "eagle-import") (part "OSD3358-SM-RED Platform_R-US_R0402"))
    )
    (comp (ref "R69")
      (value "100, 1%")
      (footprint "eagle-import:R0402")
      (libsource (lib "eagle-import") (part "OSD3358-SM-RED Platform_R-US_R0402"))
    )
    (comp (ref "R70")
      (value "100K, 1%, DNI")
      (footprint "eagle-import:R0402")
      (libsource (lib "eagle-import") (part "OSD3358-SM-RED Platform_R-US_R0402"))
    )
    (comp (ref "R71")
      (value "100K, 1%")
      (footprint "eagle-import:R0402")
      (libsource (lib "eagle-import") (part "OSD3358-SM-RED Platform_R-US_R0402"))
    )
    (comp (ref "R72")
      (value "100K, 1%, DNI")
      (footprint "eagle-import:R0402")
      (libsource (lib "eagle-import") (part "OSD3358-SM-RED Platform_R-US_R0402"))
    )
    (comp (ref "R73")
      (value "100K, 1%, DNI")
      (footprint "eagle-import:R0402")
      (libsource (lib "eagle-import") (part "OSD3358-SM-RED Platform_R-US_R0402"))
    )
    (comp (ref "R74")
      (value "100K, 1%, DNI")
      (footprint "eagle-import:R0402")
      (libsource (lib "eagle-import") (part "OSD3358-SM-RED Platform_R-US_R0402"))
    )
    (comp (ref "R75")
      (value "100K, 1%, DNI")
      (footprint "eagle-import:R0402")
      (libsource (lib "eagle-import") (part "OSD3358-SM-RED Platform_R-US_R0402"))
    )
    (comp (ref "R76")
      (value "100K, 1%, DNI")
      (footprint "eagle-import:R0402")
      (libsource (lib "eagle-import") (part "OSD3358-SM-RED Platform_R-US_R0402"))
    )
    (comp (ref "R77")
      (value "100K, 1%, DNI")
      (footprint "eagle-import:R0402")
      (libsource (lib "eagle-import") (part "OSD3358-SM-RED Platform_R-US_R0402"))
    )
    (comp (ref "R78")
      (value "100K, 1%, DNI")
      (footprint "eagle-import:R0402")
      (libsource (lib "eagle-import") (part "OSD3358-SM-RED Platform_R-US_R0402"))
    )
    (comp (ref "R79")
      (value "100K, 1%, DNI")
      (footprint "eagle-import:R0402")
      (libsource (lib "eagle-import") (part "OSD3358-SM-RED Platform_R-US_R0402"))
    )
    (comp (ref "R80")
      (value "100K, 1%, DNI")
      (footprint "eagle-import:R0402")
      (libsource (lib "eagle-import") (part "OSD3358-SM-RED Platform_R-US_R0402"))
    )
    (comp (ref "R81")
      (value "100K, 1%")
      (footprint "eagle-import:R0402")
      (libsource (lib "eagle-import") (part "OSD3358-SM-RED Platform_R-US_R0402"))
    )
    (comp (ref "R82")
      (value "100K, 1%")
      (footprint "eagle-import:R0402")
      (libsource (lib "eagle-import") (part "OSD3358-SM-RED Platform_R-US_R0402"))
    )
    (comp (ref "R83")
      (value "100K, 1%")
      (footprint "eagle-import:R0402")
      (libsource (lib "eagle-import") (part "OSD3358-SM-RED Platform_R-US_R0402"))
    )
    (comp (ref "R84")
      (value "100K, 1%, DNI")
      (footprint "eagle-import:R0402")
      (libsource (lib "eagle-import") (part "OSD3358-SM-RED Platform_R-US_R0402"))
    )
    (comp (ref "R85")
      (value "100K, 1%, DNI")
      (footprint "eagle-import:R0402")
      (libsource (lib "eagle-import") (part "OSD3358-SM-RED Platform_R-US_R0402"))
    )
    (comp (ref "R86")
      (value "10K, 1%")
      (footprint "eagle-import:R0402")
      (libsource (lib "eagle-import") (part "OSD3358-SM-RED Platform_R-US_R0402"))
    )
    (comp (ref "R87")
      (value "10K, 1%")
      (footprint "eagle-import:R0402")
      (libsource (lib "eagle-import") (part "OSD3358-SM-RED Platform_R-US_R0402"))
    )
    (comp (ref "R88")
      (value "10K, 1%")
      (footprint "eagle-import:R0402")
      (libsource (lib "eagle-import") (part "OSD3358-SM-RED Platform_R-US_R0402"))
    )
    (comp (ref "R89")
      (value "10K, 1%")
      (footprint "eagle-import:R0402")
      (libsource (lib "eagle-import") (part "OSD3358-SM-RED Platform_R-US_R0402"))
    )
    (comp (ref "R90")
      (value "10K, 1%")
      (footprint "eagle-import:R0402")
      (libsource (lib "eagle-import") (part "OSD3358-SM-RED Platform_R-US_R0402"))
    )
    (comp (ref "R91")
      (value "10K, 1%")
      (footprint "eagle-import:R0402")
      (libsource (lib "eagle-import") (part "OSD3358-SM-RED Platform_R-US_R0402"))
    )
    (comp (ref "R92")
      (value "10K, 1%")
      (footprint "eagle-import:R0402")
      (libsource (lib "eagle-import") (part "OSD3358-SM-RED Platform_R-US_R0402"))
    )
    (comp (ref "R163")
      (value "100K, DNI")
      (footprint "eagle-import:R0402")
      (libsource (lib "eagle-import") (part "OSD3358-SM-RED Platform_R-US_R0402"))
    )
    (comp (ref "R164")
      (value "1.5K, 1%")
      (footprint "eagle-import:R0402")
      (libsource (lib "eagle-import") (part "OSD3358-SM-RED Platform_R-US_R0402"))
    )
    (comp (ref "R168")
      (value "10K")
      (footprint "eagle-import:R0402")
      (libsource (lib "eagle-import") (part "OSD3358-SM-RED Platform_R-US_R0402"))
    )
    (comp (ref "R169")
      (value "1.5K, 1%")
      (footprint "eagle-import:R0402")
      (libsource (lib "eagle-import") (part "OSD3358-SM-RED Platform_R-US_R0402"))
    )
    (comp (ref "R170")
      (value "1.5K, 1%")
      (footprint "eagle-import:R0402")
      (libsource (lib "eagle-import") (part "OSD3358-SM-RED Platform_R-US_R0402"))
    )
    (comp (ref "R171")
      (value "10K")
      (footprint "eagle-import:R0402")
      (libsource (lib "eagle-import") (part "OSD3358-SM-RED Platform_R-US_R0402"))
    )
    (comp (ref "R172")
      (value "10K")
      (footprint "eagle-import:R0402")
      (libsource (lib "eagle-import") (part "OSD3358-SM-RED Platform_R-US_R0402"))
    )
    (comp (ref "R173")
      (value "10K")
      (footprint "eagle-import:R0402")
      (libsource (lib "eagle-import") (part "OSD3358-SM-RED Platform_R-US_R0402"))
    )
    (comp (ref "R174")
      (value "10K")
      (footprint "eagle-import:R0402")
      (libsource (lib "eagle-import") (part "OSD3358-SM-RED Platform_R-US_R0402"))
    )
    (comp (ref "R175")
      (value "10K")
      (footprint "eagle-import:R0402")
      (libsource (lib "eagle-import") (part "OSD3358-SM-RED Platform_R-US_R0402"))
    )
    (comp (ref "R181")
      (value "B72520T0300K062")
      (footprint "eagle-import:CT_CN1206")
      (libsource (lib "eagle-import") (part "VARISTORCN1206"))
    )
    (comp (ref "R182")
      (value "B72520T0300K062")
      (footprint "eagle-import:CT_CN1206")
      (libsource (lib "eagle-import") (part "VARISTORCN1206"))
    )
    (comp (ref "R183")
      (value "B72520T0300K062")
      (footprint "eagle-import:CT_CN1206")
      (libsource (lib "eagle-import") (part "VARISTORCN1206"))
    )
    (comp (ref "R184")
      (value "B72520T0300K062")
      (footprint "eagle-import:CT_CN1206")
      (libsource (lib "eagle-import") (part "VARISTORCN1206"))
    )
    (comp (ref "R185")
      (value "B72520T0300K062")
      (footprint "eagle-import:CT_CN1206")
      (libsource (lib "eagle-import") (part "VARISTORCN1206"))
    )
    (comp (ref "R186")
      (value "B72520T0300K062")
      (footprint "eagle-import:CT_CN1206")
      (libsource (lib "eagle-import") (part "VARISTORCN1206"))
    )
    (comp (ref "R211")
      (value "80, 0.1%")
      (footprint "eagle-import:0309_12")
      (libsource (lib "eagle-import") (part "resistor_348_R-US_0309/12"))
    )
    (comp (ref "R212")
      (value "10K, 1%")
      (footprint "eagle-import:R0805")
      (libsource (lib "eagle-import") (part "OSD3358-SM-RED Platform_R-US_R0805"))
    )
    (comp (ref "R213")
      (value "2K, 1%")
      (footprint "eagle-import:R0805")
      (libsource (lib "eagle-import") (part "OSD3358-SM-RED Platform_R-US_R0805"))
    )
    (comp (ref "R214")
      (value "10K, 1%")
      (footprint "eagle-import:R0805")
      (libsource (lib "eagle-import") (part "OSD3358-SM-RED Platform_R-US_R0805"))
    )
    (comp (ref "R221")
      (value "80, 0.1%")
      (footprint "eagle-import:0309_12")
      (libsource (lib "eagle-import") (part "resistor_348_R-US_0309/12"))
    )
    (comp (ref "R222")
      (value "10K, 1%")
      (footprint "eagle-import:R0805")
      (libsource (lib "eagle-import") (part "OSD3358-SM-RED Platform_R-US_R0805"))
    )
    (comp (ref "R223")
      (value "2K, 1%")
      (footprint "eagle-import:R0805")
      (libsource (lib "eagle-import") (part "OSD3358-SM-RED Platform_R-US_R0805"))
    )
    (comp (ref "R224")
      (value "10K, 1%")
      (footprint "eagle-import:R0805")
      (libsource (lib "eagle-import") (part "OSD3358-SM-RED Platform_R-US_R0805"))
    )
    (comp (ref "R231")
      (value "80, 0.1%")
      (footprint "eagle-import:0309_12")
      (libsource (lib "eagle-import") (part "resistor_348_R-US_0309/12"))
    )
    (comp (ref "R232")
      (value "10K, 1%")
      (footprint "eagle-import:R0805")
      (libsource (lib "eagle-import") (part "OSD3358-SM-RED Platform_R-US_R0805"))
    )
    (comp (ref "R233")
      (value "2K, 1%")
      (footprint "eagle-import:R0805")
      (libsource (lib "eagle-import") (part "OSD3358-SM-RED Platform_R-US_R0805"))
    )
    (comp (ref "R234")
      (value "10K, 1%")
      (footprint "eagle-import:R0805")
      (libsource (lib "eagle-import") (part "OSD3358-SM-RED Platform_R-US_R0805"))
    )
    (comp (ref "R241")
      (value "80, 0.1%")
      (footprint "eagle-import:0309_12")
      (libsource (lib "eagle-import") (part "resistor_348_R-US_0309/12"))
    )
    (comp (ref "R242")
      (value "10K, 1%")
      (footprint "eagle-import:R0805")
      (libsource (lib "eagle-import") (part "OSD3358-SM-RED Platform_R-US_R0805"))
    )
    (comp (ref "R243")
      (value "2K, 1%")
      (footprint "eagle-import:R0805")
      (libsource (lib "eagle-import") (part "OSD3358-SM-RED Platform_R-US_R0805"))
    )
    (comp (ref "R244")
      (value "10K, 1%")
      (footprint "eagle-import:R0805")
      (libsource (lib "eagle-import") (part "OSD3358-SM-RED Platform_R-US_R0805"))
    )
    (comp (ref "R251")
      (value "80, 0.1%")
      (footprint "eagle-import:0309_12")
      (libsource (lib "eagle-import") (part "resistor_348_R-US_0309/12"))
    )
    (comp (ref "R252")
      (value "10K, 1%")
      (footprint "eagle-import:R0805")
      (libsource (lib "eagle-import") (part "OSD3358-SM-RED Platform_R-US_R0805"))
    )
    (comp (ref "R253")
      (value "2K, 1%")
      (footprint "eagle-import:R0805")
      (libsource (lib "eagle-import") (part "OSD3358-SM-RED Platform_R-US_R0805"))
    )
    (comp (ref "R254")
      (value "10K, 1%")
      (footprint "eagle-import:R0805")
      (libsource (lib "eagle-import") (part "OSD3358-SM-RED Platform_R-US_R0805"))
    )
    (comp (ref "R261")
      (value "80, 0.1%")
      (footprint "eagle-import:0309_12")
      (libsource (lib "eagle-import") (part "resistor_348_R-US_0309/12"))
    )
    (comp (ref "R262")
      (value "10K, 1%")
      (footprint "eagle-import:R0805")
      (libsource (lib "eagle-import") (part "OSD3358-SM-RED Platform_R-US_R0805"))
    )
    (comp (ref "R263")
      (value "2K, 1%")
      (footprint "eagle-import:R0805")
      (libsource (lib "eagle-import") (part "OSD3358-SM-RED Platform_R-US_R0805"))
    )
    (comp (ref "R264")
      (value "10K, 1%")
      (footprint "eagle-import:R0805")
      (libsource (lib "eagle-import") (part "OSD3358-SM-RED Platform_R-US_R0805"))
    )
    (comp (ref "R281")
      (value "10K")
      (footprint "eagle-import:RN0804")
      (libsource (lib "eagle-import") (part "RESISTOR.NETWORK-(4)"))
    )
    (comp (ref "R282")
      (value "10K")
      (footprint "eagle-import:RN0804")
      (libsource (lib "eagle-import") (part "RESISTOR.NETWORK-(4)"))
    )
    (comp (ref "R291")
      (value "10K")
      (footprint "eagle-import:RN0804")
      (libsource (lib "eagle-import") (part "RESISTOR.NETWORK-(4)"))
    )
    (comp (ref "R301")
      (value "1K")
      (footprint "eagle-import:R0402")
      (libsource (lib "eagle-import") (part "OSD3358-SM-RED Platform_R-US_R0402"))
    )
    (comp (ref "R302")
      (value "1K")
      (footprint "eagle-import:R0402")
      (libsource (lib "eagle-import") (part "OSD3358-SM-RED Platform_R-US_R0402"))
    )
    (comp (ref "R303")
      (value "1K, DNI")
      (footprint "eagle-import:R0402")
      (libsource (lib "eagle-import") (part "OSD3358-SM-RED Platform_R-US_R0402"))
    )
    (comp (ref "R304")
      (value "1K, DNI")
      (footprint "eagle-import:R0402")
      (libsource (lib "eagle-import") (part "OSD3358-SM-RED Platform_R-US_R0402"))
    )
    (comp (ref "R305")
      (value "150, 1%")
      (footprint "eagle-import:R0805")
      (libsource (lib "eagle-import") (part "OSD3358-SM-RED Platform_R-US_R0805"))
    )
    (comp (ref "R401")
      (value "1K")
      (footprint "eagle-import:R0402")
      (libsource (lib "eagle-import") (part "OSD3358-SM-RED Platform_R-US_R0402"))
    )
    (comp (ref "R402")
      (value "1K")
      (footprint "eagle-import:R0402")
      (libsource (lib "eagle-import") (part "OSD3358-SM-RED Platform_R-US_R0402"))
    )
    (comp (ref "R801")
      (value "1K")
      (footprint "eagle-import:R0402")
      (libsource (lib "eagle-import") (part "OSD3358-SM-RED Platform_R-US_R0402"))
    )
    (comp (ref "R802")
      (value "1K")
      (footprint "eagle-import:R0402")
      (libsource (lib "eagle-import") (part "OSD3358-SM-RED Platform_R-US_R0402"))
    )
    (comp (ref "RTC1")
      (value "DS3231MZ+")
      (footprint "eagle-import:SO08")
      (libsource (lib "eagle-import") (part "DS3231M"))
    )
    (comp (ref "S1")
      (value "KMR231GLFS")
      (footprint "eagle-import:SW4SMD_63X161LS")
      (libsource (lib "eagle-import") (part "KMR231GLFS"))
    )
    (comp (ref "S2")
      (value "KMR231GLFS")
      (footprint "eagle-import:SW4SMD_63X161LS")
      (libsource (lib "eagle-import") (part "OSD3358-SM-RED Platform_KMR231GLFS"))
    )
    (comp (ref "S11")
      (value "P101")
      (footprint "eagle-import:P101")
      (libsource (lib "eagle-import") (part "P101"))
    )
    (comp (ref "S12")
      (value "P101")
      (footprint "eagle-import:P101")
      (libsource (lib "eagle-import") (part "P101"))
    )
    (comp (ref "S13")
      (value "DS04")
      (footprint "eagle-import:DS-04")
      (libsource (lib "eagle-import") (part "DS04"))
    )
    (comp (ref "T4")
      (value "DA2304-AL")
      (footprint "eagle-import:DA230X-AL")
      (libsource (lib "eagle-import") (part "DA2304-AL"))
    )
    (comp (ref "TP1")
      (value "TPB0,65")
      (footprint "eagle-import:TP_B0,65")
      (libsource (lib "eagle-import") (part "OSD3358-SM-RED Platform_TPB0,65"))
    )
    (comp (ref "TP2")
      (value "TPB0,65")
      (footprint "eagle-import:TP_B0,65")
      (libsource (lib "eagle-import") (part "OSD3358-SM-RED Platform_TPB0,65"))
    )
    (comp (ref "TP3")
      (value "TPB0,65")
      (footprint "eagle-import:TP_B0,65")
      (libsource (lib "eagle-import") (part "OSD3358-SM-RED Platform_TPB0,65"))
    )
    (comp (ref "TP4")
      (value "TPB0,65")
      (footprint "eagle-import:TP_B0,65")
      (libsource (lib "eagle-import") (part "OSD3358-SM-RED Platform_TPB0,65"))
    )
    (comp (ref "TP5")
      (value "TESTPAD/W_HOLE_1X1")
      (footprint "eagle-import:TESTPAD_W_HOLE_1X1")
      (libsource (lib "eagle-import") (part "TESTPAD/W_HOLE_1X1"))
    )
    (comp (ref "TP6")
      (value "TESTPAD/W_HOLE_1X1")
      (footprint "eagle-import:TESTPAD_W_HOLE_1X1")
      (libsource (lib "eagle-import") (part "TESTPAD/W_HOLE_1X1"))
    )
    (comp (ref "TP7")
      (value "TESTPAD/W_HOLE_1X1")
      (footprint "eagle-import:TESTPAD_W_HOLE_1X1")
      (libsource (lib "eagle-import") (part "TESTPAD/W_HOLE_1X1"))
    )
    (comp (ref "TP8")
      (value "TESTPAD/W_HOLE_1X1")
      (footprint "eagle-import:TESTPAD_W_HOLE_1X1")
      (libsource (lib "eagle-import") (part "TESTPAD/W_HOLE_1X1"))
    )
    (comp (ref "TP9")
      (value "TESTPAD/W_HOLE_1X1")
      (footprint "eagle-import:TESTPAD_W_HOLE_1X1")
      (libsource (lib "eagle-import") (part "TESTPAD/W_HOLE_1X1"))
    )
    (comp (ref "TP10")
      (value "TESTPAD/W_HOLE_1X1")
      (footprint "eagle-import:TESTPAD_W_HOLE_1X1")
      (libsource (lib "eagle-import") (part "TESTPAD/W_HOLE_1X1"))
    )
    (comp (ref "TP11")
      (value "TPB0,65")
      (footprint "eagle-import:TP_B0,65")
      (libsource (lib "eagle-import") (part "OSD3358-SM-RED Platform_TPB0,65"))
    )
    (comp (ref "TP12")
      (value "TPB0,65")
      (footprint "eagle-import:TP_B0,65")
      (libsource (lib "eagle-import") (part "OSD3358-SM-RED Platform_TPB0,65"))
    )
    (comp (ref "TP13")
      (value "TPB0,65")
      (footprint "eagle-import:TP_B0,65")
      (libsource (lib "eagle-import") (part "OSD3358-SM-RED Platform_TPB0,65"))
    )
    (comp (ref "TP14")
      (value "TPB0,65")
      (footprint "eagle-import:TP_B0,65")
      (libsource (lib "eagle-import") (part "OSD3358-SM-RED Platform_TPB0,65"))
    )
    (comp (ref "TP15")
      (value "TPB0,65")
      (footprint "eagle-import:TP_B0,65")
      (libsource (lib "eagle-import") (part "OSD3358-SM-RED Platform_TPB0,65"))
    )
    (comp (ref "TP16")
      (value "TPB0,65")
      (footprint "eagle-import:TP_B0,65")
      (libsource (lib "eagle-import") (part "OSD3358-SM-RED Platform_TPB0,65"))
    )
    (comp (ref "TP17")
      (value "TESTPAD/W_HOLE_1X1")
      (footprint "eagle-import:TESTPAD_W_HOLE_1X1")
      (libsource (lib "eagle-import") (part "TESTPAD/W_HOLE_1X1"))
    )
    (comp (ref "TP18")
      (value "TESTPAD/W_HOLE_1X1")
      (footprint "eagle-import:TESTPAD_W_HOLE_1X1")
      (libsource (lib "eagle-import") (part "TESTPAD/W_HOLE_1X1"))
    )
    (comp (ref "TP19")
      (value "TESTPAD/W_HOLE_1X1")
      (footprint "eagle-import:TESTPAD_W_HOLE_1X1")
      (libsource (lib "eagle-import") (part "TESTPAD/W_HOLE_1X1"))
    )
    (comp (ref "TP20")
      (value "TESTPAD/W_HOLE_1X1")
      (footprint "eagle-import:TESTPAD_W_HOLE_1X1")
      (libsource (lib "eagle-import") (part "TESTPAD/W_HOLE_1X1"))
    )
    (comp (ref "TP21")
      (value "TPB0,65")
      (footprint "eagle-import:TP_B0,65")
      (libsource (lib "eagle-import") (part "OSD3358-SM-RED Platform_TPB0,65"))
    )
    (comp (ref "TP22")
      (value "TPB0,65")
      (footprint "eagle-import:TP_B0,65")
      (libsource (lib "eagle-import") (part "OSD3358-SM-RED Platform_TPB0,65"))
    )
    (comp (ref "TP23")
      (value "TPB0,65")
      (footprint "eagle-import:TP_B0,65")
      (libsource (lib "eagle-import") (part "OSD3358-SM-RED Platform_TPB0,65"))
    )
    (comp (ref "TP24")
      (value "TPB0,65")
      (footprint "eagle-import:TP_B0,65")
      (libsource (lib "eagle-import") (part "OSD3358-SM-RED Platform_TPB0,65"))
    )
    (comp (ref "TP26")
      (value "TPB0,65")
      (footprint "eagle-import:TP_B0,65")
      (libsource (lib "eagle-import") (part "TPB0,65"))
    )
    (comp (ref "TP31")
      (value "TPB0,65")
      (footprint "eagle-import:TP_B0,65")
      (libsource (lib "eagle-import") (part "TPB0,65"))
    )
    (comp (ref "TP32")
      (value "TPB0,65")
      (footprint "eagle-import:TP_B0,65")
      (libsource (lib "eagle-import") (part "OSD3358-SM-RED Platform_TPB0,65"))
    )
    (comp (ref "TP33")
      (value "TPB0,65")
      (footprint "eagle-import:TP_B0,65")
      (libsource (lib "eagle-import") (part "OSD3358-SM-RED Platform_TPB0,65"))
    )
    (comp (ref "U1")
      (value "OSD3358-512M-ICB")
      (footprint "eagle-import:OSD335X-BGA-400")
      (libsource (lib "eagle-import") (part "OSD3358-512M-ICB"))
    )
    (comp (ref "U2")
      (value "TPD4S012_DRY_6_P1_M")
      (footprint "eagle-import:DRY6")
      (fields
        (field (name "GENERIC_PART_NUMBER") "TPD4S012")
        (field (name "MANUFACTURER") "Texas Instruments")
        (field (name "MANUFACTURER_PART_NUMBER") "tpd4s012_dry_6")
      )
      (libsource (lib "eagle-import") (part "TPD4S012_DRY_6_P1_M"))
    )
    (comp (ref "U4")
      (value "APX811-31UGSOT")
      (footprint "eagle-import:SOT143-R")
      (libsource (lib "eagle-import") (part "APX811-31UGSOT"))
    )
    (comp (ref "U5")
      (value "TLVH431")
      (footprint "eagle-import:SOT23-3")
      (libsource (lib "eagle-import") (part "TLVH431"))
    )
    (comp (ref "U6")
      (value "SN74LVC2G241_DCU_8")
      (footprint "eagle-import:DCU8")
      (fields
        (field (name "GENERIC_PART_NUMBER") "SN74LVC2G241")
        (field (name "MANUFACTURER") "Texas Instruments")
        (field (name "MANUFACTURER_PART_NUMBER") "sn74lvc2g241_dcu_8")
      )
      (libsource (lib "eagle-import") (part "SN74LVC2G241_DCU_8"))
    )
    (comp (ref "U16")
      (value "AT97SC3205T-G3M4400B")
      (footprint "eagle-import:QFN32-0.4-4X4MM")
      (libsource (lib "eagle-import") (part "AT97SC3205T-G3M4400B"))
    )
    (comp (ref "U27")
      (value "LAN8710")
      (footprint "eagle-import:LAN8710A-QFN32")
      (libsource (lib "eagle-import") (part "LAN8710"))
    )
    (comp (ref "U28")
      (value "TCAN1051HV")
      (footprint "eagle-import:BEAGLEBONE_BLUE_D8")
      (fields
        (field (name "MANUFACTURER") "Texas Instruments")
        (field (name "MANUFACTURER_PART_NUMBER") "TCAN1051HVD")
      )
      (libsource (lib "eagle-import") (part "TCAN1051HV"))
    )
    (comp (ref "U29")
      (value "MAX3483EESA+T")
      (footprint "eagle-import:21-0041B_8")
      (libsource (lib "eagle-import") (part "MAX3483EESA+T"))
    )
    (comp (ref "U40")
      (value "ISO3086TDW")
      (footprint "eagle-import:DW16")
      (libsource (lib "eagle-import") (part "ISO3086TDW"))
    )
    (comp (ref "VREG1")
      (value "LM2596S-5.0")
      (footprint "eagle-import:TO263-5")
      (libsource (lib "eagle-import") (part "LM2596S"))
    )
    (comp (ref "VREG2")
      (value "L7824CV")
      (footprint "eagle-import:78XXL")
      (libsource (lib "eagle-import") (part "78XXL"))
    )
    (comp (ref "VREG4")
      (value "TPS76350")
      (footprint "eagle-import:DBV5")
      (fields (field (name "MANUFACTURER_PART_NUMBER") "LP2985A33DBVR"))
      (libsource (lib "eagle-import") (part "LP2985A-33DBVR"))
    )
    (comp (ref "X1")
      (value "10118194-0001LF")
      (footprint "eagle-import:10118194-0001LF(MICRO-USB-B-AMPHENOL-FCI)")
      (libsource (lib "eagle-import") (part "10118194-0001LF"))
    )
    (comp (ref "X2")
      (value "J0011D01BNL")
      (footprint "eagle-import:J0011D01BNL")
      (libsource (lib "eagle-import") (part "J0011D01BNL"))
    )
    (comp (ref "X3")
      (value "MC4")
      (footprint "eagle-import:MC4")
      (libsource (lib "eagle-import") (part "MC4"))
    )
    (comp (ref "X4")
      (value "CTI-JTAG")
      (footprint "eagle-import:CTI-JTAG")
      (libsource (lib "eagle-import") (part "CTI-JTAG"))
    )
    (comp (ref "X5")
      (value "DM3CS-SF")
      (footprint "eagle-import:DM3CS-SF")
      (fields (field (name "MOUSER_PART_NUMBER") "798-DM3CSSF"))
      (libsource (lib "eagle-import") (part "DM3CS-SF"))
    )
    (comp (ref "X6")
      (value "6p-2.54")
      (footprint "eagle-import:H6-2.54")
      (fields (field (name "MPN") "P125-1106A1BS116A1"))
      (libsource (lib "eagle-import") (part "826646-6"))
    )
    (comp (ref "X7")
      (value "TH-2X10")
      (footprint "eagle-import:H2X10-2.54")
      (libsource (lib "eagle-import") (part "TH-2X10"))
    )
    (comp (ref "X8")
      (value "MC4")
      (footprint "eagle-import:MC4")
      (libsource (lib "eagle-import") (part "MC4"))
    )
    (comp (ref "X10")
      (value "MC4")
      (footprint "eagle-import:MC4")
      (libsource (lib "eagle-import") (part "MC4"))
    )
    (comp (ref "X11")
      (value "MC4")
      (footprint "eagle-import:MC4")
      (libsource (lib "eagle-import") (part "MC4"))
    )
    (comp (ref "X12")
      (value "MC4")
      (footprint "eagle-import:MC4")
      (libsource (lib "eagle-import") (part "MC4"))
    )
    (comp (ref "X21")
      (value "MC10")
      (footprint "eagle-import:MC10")
      (libsource (lib "eagle-import") (part "MC10"))
    )
    (comp (ref "X24")
      (value "MSTBA2")
      (footprint "eagle-import:MSTBA2")
      (fields (field (name "MF") "FARNELL") (field (name "MPN") "1757242"))
      (libsource (lib "eagle-import") (part "MSTBA2"))
    )
    (comp (ref "X41")
      (value "MSTBA3")
      (footprint "eagle-import:MSTBA3")
      (fields (field (name "MF") "FARNELL") (field (name "MPN") "1757255"))
      (libsource (lib "eagle-import") (part "MSTBA3"))
    )
    (comp (ref "Y7")
      (value "7A-25.000MAAE-T")
      (footprint "eagle-import:CRYSTAL-TXC-7A")
      (libsource (lib "eagle-import") (part "7A-25.000MAAE-T"))
    )
  )
  (nets
    (net (code "1") (name "/1P8V_REF_1") (class "Default")
      (node (ref "IC10") (pin "8") (pinfunction "V+_8") (pintype "power_in"))
      (node (ref "IC11") (pin "8") (pinfunction "V+_8") (pintype "power_in"))
      (node (ref "IC14") (pin "1") (pinfunction "OUT_1") (pintype "output"))
      (node (ref "IC14") (pin "2") (pinfunction "-IN_2") (pintype "input"))
      (node (ref "R212") (pin "2") (pinfunction "2_2") (pintype "passive"))
      (node (ref "R222") (pin "2") (pinfunction "2_2") (pintype "passive"))
      (node (ref "R232") (pin "2") (pinfunction "2_2") (pintype "passive"))
      (node (ref "R242") (pin "2") (pinfunction "2_2") (pintype "passive"))
    )
    (net (code "2") (name "/1P8V_REF_2") (class "Default")
      (node (ref "IC12") (pin "8") (pinfunction "V+_8") (pintype "power_in"))
      (node (ref "IC14") (pin "6") (pinfunction "-IN_6") (pintype "input"))
      (node (ref "IC14") (pin "7") (pinfunction "OUT_7") (pintype "output"))
      (node (ref "R252") (pin "2") (pinfunction "2_2") (pintype "passive"))
      (node (ref "R262") (pin "2") (pinfunction "2_2") (pintype "passive"))
    )
    (net (code "3") (name "/5V_OUT") (class "Default")
      (node (ref "D18") (pin "C") (pinfunction "C_C") (pintype "passive"))
      (node (ref "L2") (pin "1") (pinfunction "1_1") (pintype "passive"))
      (node (ref "VREG1") (pin "2") (pinfunction "OUT_2") (pintype "output"))
    )
    (net (code "4") (name "/485_A") (class "Default")
      (node (ref "D305") (pin "1") (pinfunction "1_1") (pintype "passive"))
      (node (ref "R304") (pin "2") (pinfunction "2_2") (pintype "passive"))
      (node (ref "R305") (pin "2") (pinfunction "2_2") (pintype "passive"))
      (node (ref "U29") (pin "6") (pinfunction "A_6") (pintype "bidirectional"))
      (node (ref "X3") (pin "2") (pinfunction "SK_2") (pintype "passive"))
    )
    (net (code "5") (name "/485_B") (class "Default")
      (node (ref "D305") (pin "2") (pinfunction "2_2") (pintype "passive"))
      (node (ref "R303") (pin "1") (pinfunction "1_1") (pintype "passive"))
      (node (ref "R305") (pin "1") (pinfunction "1_1") (pintype "passive"))
      (node (ref "U29") (pin "7") (pinfunction "B_7") (pintype "bidirectional"))
      (node (ref "X3") (pin "3") (pinfunction "SK_3") (pintype "passive"))
    )
    (net (code "6") (name "/AIN0") (class "Default")
      (node (ref "U1") (pin "Y10") (pinfunction "AIN0_Y10") (pintype "bidirectional"))
    )
    (net (code "7") (name "/AIN1") (class "Default")
      (node (ref "IC10") (pin "1") (pinfunction "OUT_1") (pintype "output"))
      (node (ref "IC10") (pin "2") (pinfunction "-IN_2") (pintype "input"))
      (node (ref "U1") (pin "W10") (pinfunction "AIN1_W10") (pintype "bidirectional"))
    )
    (net (code "8") (name "/AIN2") (class "Default")
      (node (ref "IC10") (pin "6") (pinfunction "-IN_6") (pintype "input"))
      (node (ref "IC10") (pin "7") (pinfunction "OUT_7") (pintype "output"))
      (node (ref "U1") (pin "V10") (pinfunction "AIN2_V10") (pintype "bidirectional"))
    )
    (net (code "9") (name "/AIN3") (class "Default")
      (node (ref "IC11") (pin "1") (pinfunction "OUT_1") (pintype "output"))
      (node (ref "IC11") (pin "2") (pinfunction "-IN_2") (pintype "input"))
      (node (ref "U1") (pin "V9") (pinfunction "AIN3_V9") (pintype "bidirectional"))
    )
    (net (code "10") (name "/AIN4") (class "Default")
      (node (ref "IC11") (pin "6") (pinfunction "-IN_6") (pintype "input"))
      (node (ref "IC11") (pin "7") (pinfunction "OUT_7") (pintype "output"))
      (node (ref "U1") (pin "Y11") (pinfunction "AIN4_Y11") (pintype "bidirectional"))
    )
    (net (code "11") (name "/AIN5") (class "Default")
      (node (ref "IC12") (pin "1") (pinfunction "OUT_1") (pintype "output"))
      (node (ref "IC12") (pin "2") (pinfunction "-IN_2") (pintype "input"))
      (node (ref "U1") (pin "W11") (pinfunction "AIN5_W11") (pintype "bidirectional"))
    )
    (net (code "12") (name "/AIN6") (class "Default")
      (node (ref "IC12") (pin "6") (pinfunction "-IN_6") (pintype "input"))
      (node (ref "IC12") (pin "7") (pinfunction "OUT_7") (pintype "output"))
      (node (ref "U1") (pin "V11") (pinfunction "AIN6_V11") (pintype "bidirectional"))
    )
    (net (code "13") (name "/AIN7") (class "Default")
      (node (ref "U1") (pin "U12") (pinfunction "PMIC_MUX_OUT_U12") (pintype "bidirectional"))
      (node (ref "U1") (pin "V12") (pinfunction "AIN7_V12") (pintype "bidirectional"))
    )
    (net (code "14") (name "/B03_NO") (class "Default")
      (node (ref "K3") (pin "NO") (pinfunction "S_NO") (pintype "passive"))
      (node (ref "X21") (pin "6") (pinfunction "SK_6") (pintype "passive"))
    )
    (net (code "15") (name "/BAT_SENSE") (class "Default")
      (node (ref "TP6") (pin "P$1") (pinfunction "TP_P$1") (pintype "bidirectional"))
      (node (ref "U1") (pin "E19") (pinfunction "PMIC_BAT_SENSE_E19") (pintype "bidirectional"))
    )
    (net (code "16") (name "/BO1_C") (class "Default")
      (node (ref "K1") (pin "C") (pinfunction "P_C") (pintype "passive"))
      (node (ref "X21") (pin "9") (pinfunction "SK_9") (pintype "passive"))
    )
    (net (code "17") (name "/BO1_NO") (class "Default")
      (node (ref "K1") (pin "NO") (pinfunction "S_NO") (pintype "passive"))
      (node (ref "X21") (pin "10") (pinfunction "SK_10") (pintype "passive"))
    )
    (net (code "18") (name "/BO2_C") (class "Default")
      (node (ref "K2") (pin "C") (pinfunction "P_C") (pintype "passive"))
      (node (ref "X21") (pin "7") (pinfunction "SK_7") (pintype "passive"))
    )
    (net (code "19") (name "/BO2_NO") (class "Default")
      (node (ref "K2") (pin "NO") (pinfunction "S_NO") (pintype "passive"))
      (node (ref "X21") (pin "8") (pinfunction "SK_8") (pintype "passive"))
    )
    (net (code "20") (name "/BO3_C") (class "Default")
      (node (ref "K3") (pin "C") (pinfunction "P_C") (pintype "passive"))
      (node (ref "X21") (pin "5") (pinfunction "SK_5") (pintype "passive"))
    )
    (net (code "21") (name "/BO4_C") (class "Default")
      (node (ref "K4") (pin "C") (pinfunction "P_C") (pintype "passive"))
      (node (ref "X21") (pin "3") (pinfunction "SK_3") (pintype "passive"))
    )
    (net (code "22") (name "/BO4_NO") (class "Default")
      (node (ref "K4") (pin "NO") (pinfunction "S_NO") (pintype "passive"))
      (node (ref "X21") (pin "4") (pinfunction "SK_4") (pintype "passive"))
    )
    (net (code "23") (name "/B_UART0_RX") (class "Default")
      (node (ref "R27") (pin "2") (pinfunction "2_2") (pintype "passive"))
      (node (ref "U6") (pin "2") (pinfunction "1A_2") (pintype "input"))
      (node (ref "X6") (pin "4") (pinfunction "4_4") (pintype "bidirectional"))
    )
    (net (code "24") (name "/B_UART0_TX") (class "Default")
      (node (ref "U6") (pin "3") (pinfunction "2Y_3") (pintype "output"))
      (node (ref "X6") (pin "5") (pinfunction "5_5") (pintype "bidirectional"))
    )
    (net (code "25") (name "/CAN1_RXD") (class "Default")
      (node (ref "D802") (pin "1") (pinfunction "A_1") (pintype "passive"))
      (node (ref "U1") (pin "Y7") (pinfunction "UART1_RXD_Y7") (pintype "bidirectional"))
      (node (ref "U28") (pin "4") (pinfunction "RXD_4") (pintype "output"))
    )
    (net (code "26") (name "/CAN1_TXD") (class "Default")
      (node (ref "D801") (pin "1") (pinfunction "A_1") (pintype "passive"))
      (node (ref "U1") (pin "W7") (pinfunction "UART1_TXD_W7") (pintype "bidirectional"))
      (node (ref "U28") (pin "1") (pinfunction "TXD_1") (pintype "input"))
    )
    (net (code "27") (name "/CAN_H") (class "Default")
      (node (ref "D805") (pin "2") (pinfunction "2_2") (pintype "passive"))
      (node (ref "U28") (pin "7") (pinfunction "CANH_7") (pintype "bidirectional"))
      (node (ref "X8") (pin "2") (pinfunction "SK_2") (pintype "passive"))
    )
    (net (code "28") (name "/CAN_L") (class "Default")
      (node (ref "D805") (pin "1") (pinfunction "1_1") (pintype "passive"))
      (node (ref "U28") (pin "6") (pinfunction "CANL_6") (pintype "bidirectional"))
      (node (ref "X8") (pin "1") (pinfunction "SK_1") (pintype "passive"))
    )
    (net (code "29") (name "/CLKOUT2") (class "Default")
      (node (ref "C2") (pin "2") (pinfunction "2_2") (pintype "passive"))
      (node (ref "R3") (pin "2") (pinfunction "2_2") (pintype "passive"))
      (node (ref "X4") (pin "18") (pinfunction "EMU3_18") (pintype "bidirectional"))
    )
    (net (code "30") (name "/CRS") (class "Default")
      (node (ref "ER124") (pin "1") (pinfunction "1_1") (pintype "passive"))
      (node (ref "U27") (pin "14") (pinfunction "CRS_14") (pintype "bidirectional"))
    )
    (net (code "31") (name "/EHRPWM1A") (class "Default")
      (node (ref "J4") (pin "1") (pinfunction "1_1") (pintype "bidirectional"))
      (node (ref "U1") (pin "C13") (pinfunction "GPMC_A2_C13") (pintype "bidirectional"))
    )
    (net (code "32") (name "/EHRPWM1B") (class "Default")
      (node (ref "U1") (pin "A12") (pinfunction "GPMC_A3_A12") (pintype "bidirectional"))
    )
    (net (code "33") (name "/EHRPWM2A") (class "Default")
      (node (ref "J5") (pin "1") (pinfunction "1_1") (pintype "bidirectional"))
      (node (ref "U1") (pin "A17") (pinfunction "GPMC_AD8_A17") (pintype "bidirectional"))
    )
    (net (code "34") (name "/EHRPWM2B") (class "Default")
      (node (ref "J6") (pin "1") (pinfunction "1_1") (pintype "bidirectional"))
      (node (ref "U1") (pin "C16") (pinfunction "GPMC_AD9_C16") (pintype "bidirectional"))
    )
    (net (code "35") (name "/E_LED_GRN") (class "Default")
      (node (ref "U27") (pin "3") (pinfunction "LED1/REGOFF_3") (pintype "bidirectional"))
      (node (ref "X2") (pin "9") (pinfunction "GRNA_9") (pintype "passive"))
    )
    (net (code "36") (name "/E_LED_YEL") (class "Default")
      (node (ref "ER120") (pin "2") (pinfunction "2_2") (pintype "passive"))
      (node (ref "U27") (pin "2") (pinfunction "LED2/~{INTSEL}_2") (pintype "bidirectional"))
      (node (ref "X2") (pin "12") (pinfunction "YELA_12") (pintype "passive"))
    )
    (net (code "37") (name "/GPIO0_4") (class "Default")
      (node (ref "U1") (pin "W4") (pinfunction "SPI0_D1_W4") (pintype "bidirectional"))
      (node (ref "U29") (pin "2") (pinfunction "~{RE}_2") (pintype "input"))
      (node (ref "U29") (pin "3") (pinfunction "DE_3") (pintype "input"))
    )
    (net (code "38") (name "/GPIO0_18") (class "Default")
      (node (ref "U1") (pin "K3") (pinfunction "USB0_DRVVBUS_K3") (pintype "bidirectional"))
    )
    (net (code "39") (name "/GPIO1_12") (class "Default")
      (node (ref "IC2") (pin "2") (pinfunction "I2_2") (pintype "input"))
      (node (ref "U1") (pin "C15") (pinfunction "GPMC_AD12_C15") (pintype "bidirectional"))
    )
    (net (code "40") (name "/GPIO1_13") (class "Default")
      (node (ref "IC2") (pin "3") (pinfunction "I3_3") (pintype "input"))
      (node (ref "U1") (pin "B15") (pinfunction "GPMC_AD13_B15") (pintype "bidirectional"))
    )
    (net (code "41") (name "/GPIO1_14") (class "Default")
      (node (ref "IC2") (pin "4") (pinfunction "I4_4") (pintype "input"))
      (node (ref "U1") (pin "A15") (pinfunction "GPMC_AD14_A15") (pintype "bidirectional"))
    )
    (net (code "42") (name "/GPIO1_15") (class "Default")
      (node (ref "IC2") (pin "5") (pinfunction "I5_5") (pintype "input"))
      (node (ref "U1") (pin "C14") (pinfunction "GPMC_AD15_C14") (pintype "bidirectional"))
    )
    (net (code "43") (name "/GPIO1_16") (class "Default")
      (node (ref "U1") (pin "B14") (pinfunction "GPMC_CSN3_B14") (pintype "bidirectional"))
      (node (ref "U40") (pin "7") (pinfunction "DE_7") (pintype "passive"))
    )
    (net (code "44") (name "/GPIO1_17") (class "Default")
      (node (ref "IC2") (pin "1") (pinfunction "I1_1") (pintype "input"))
      (node (ref "U1") (pin "B13") (pinfunction "GPMC_A1_B13") (pintype "bidirectional"))
    )
    (net (code "45") (name "/GPIO1_28") (class "Default")
      (node (ref "U1") (pin "C9") (pinfunction "GPMC_BEN1_C9") (pintype "bidirectional"))
      (node (ref "U40") (pin "6") (pinfunction "~{RE}_6") (pintype "passive"))
    )
    (net (code "46") (name "/I2C0_SCL") (class "Default")
      (node (ref "R12") (pin "1") (pinfunction "1_1") (pintype "passive"))
      (node (ref "TP18") (pin "P$1") (pinfunction "TP_P$1") (pintype "bidirectional"))
      (node (ref "U1") (pin "U8") (pinfunction "PMIC_SCL_U8") (pintype "bidirectional"))
      (node (ref "U1") (pin "V8") (pinfunction "I2C0_SCL_V8") (pintype "bidirectional"))
      (node (ref "U16") (pin "29") (pinfunction "SM_CLK_29") (pintype "bidirectional"))
    )
    (net (code "47") (name "/I2C0_SDA") (class "Default")
      (node (ref "R13") (pin "1") (pinfunction "1_1") (pintype "passive"))
      (node (ref "TP17") (pin "P$1") (pinfunction "TP_P$1") (pintype "bidirectional"))
      (node (ref "U1") (pin "U7") (pinfunction "PMIC_SDA_U7") (pintype "bidirectional"))
      (node (ref "U1") (pin "V7") (pinfunction "I2C0_SDA_V7") (pintype "bidirectional"))
      (node (ref "U16") (pin "30") (pinfunction "SM_DAT_30") (pintype "bidirectional"))
    )
    (net (code "48") (name "/I2C1_SCL") (class "Default")
      (node (ref "R169") (pin "1") (pinfunction "1_1") (pintype "passive"))
      (node (ref "RTC1") (pin "8") (pinfunction "SCL_8") (pintype "bidirectional"))
      (node (ref "TP20") (pin "P$1") (pinfunction "TP_P$1") (pintype "bidirectional"))
      (node (ref "U1") (pin "V5") (pinfunction "UART0_RTSN_V5") (pintype "bidirectional"))
    )
    (net (code "49") (name "/I2C1_SDA") (class "Default")
      (node (ref "R170") (pin "1") (pinfunction "1_1") (pintype "passive"))
      (node (ref "RTC1") (pin "7") (pinfunction "SDA_7") (pintype "bidirectional"))
      (node (ref "TP19") (pin "P$1") (pinfunction "TP_P$1") (pintype "bidirectional"))
      (node (ref "U1") (pin "V6") (pinfunction "UART0_CTSN_V6") (pintype "bidirectional"))
    )
    (net (code "50") (name "/ISO_485_A") (class "Default")
      (node (ref "D405") (pin "1") (pinfunction "1_1") (pintype "passive"))
      (node (ref "F401") (pin "3") (pinfunction "3_3") (pintype "passive"))
      (node (ref "U40") (pin "11") (pinfunction "Y_11") (pintype "passive"))
      (node (ref "U40") (pin "14") (pinfunction "A_14") (pintype "passive"))
    )
    (net (code "51") (name "/ISO_485_B") (class "Default")
      (node (ref "D405") (pin "2") (pinfunction "2_2") (pintype "passive"))
      (node (ref "F402") (pin "3") (pinfunction "3_3") (pintype "passive"))
      (node (ref "U40") (pin "12") (pinfunction "Z_12") (pintype "passive"))
      (node (ref "U40") (pin "13") (pinfunction "B_13") (pintype "passive"))
    )
    (net (code "52") (name "/ISO_VCC") (class "Default")
      (node (ref "C402") (pin "1") (pinfunction "1_1") (pintype "passive"))
      (node (ref "C406") (pin "+") (pinfunction "+_+") (pintype "passive"))
      (node (ref "U40") (pin "16") (pinfunction "VCC2_16") (pintype "power_in"))
      (node (ref "VREG4") (pin "5") (pinfunction "VOUT_5") (pintype "output"))
    )
    (net (code "53") (name "/ISO_VIN") (class "Default")
      (node (ref "C403") (pin "1") (pinfunction "1_1") (pintype "passive"))
      (node (ref "C405") (pin "1") (pinfunction "1_1") (pintype "passive"))
      (node (ref "D403") (pin "C") (pinfunction "C_C") (pintype "passive"))
      (node (ref "D404") (pin "C") (pinfunction "C_C") (pintype "passive"))
      (node (ref "VREG4") (pin "1") (pinfunction "VIN_1") (pintype "input"))
      (node (ref "VREG4") (pin "3") (pinfunction "ON/~{OFF}_3") (pintype "passive"))
    )
    (net (code "54") (name "/JTAG_EMU0") (class "Default")
      (node (ref "R40") (pin "1") (pinfunction "1_1") (pintype "passive"))
      (node (ref "U1") (pin "V18") (pinfunction "EMU0_V18") (pintype "bidirectional"))
      (node (ref "X4") (pin "13") (pinfunction "EMU0_13") (pintype "bidirectional"))
    )
    (net (code "55") (name "/JTAG_EMU1") (class "Default")
      (node (ref "R41") (pin "1") (pinfunction "1_1") (pintype "passive"))
      (node (ref "U1") (pin "V19") (pinfunction "EMU1_V19") (pintype "bidirectional"))
      (node (ref "X4") (pin "14") (pinfunction "EMU1_14") (pintype "bidirectional"))
    )
    (net (code "56") (name "/JTAG_TCK") (class "Default")
      (node (ref "U1") (pin "Y19") (pinfunction "TCK_Y19") (pintype "bidirectional"))
      (node (ref "X4") (pin "11") (pinfunction "TCK_11") (pintype "bidirectional"))
      (node (ref "X4") (pin "9") (pinfunction "TCKRTN_9") (pintype "bidirectional"))
    )
    (net (code "57") (name "/JTAG_TDI") (class "Default")
      (node (ref "U1") (pin "Y18") (pinfunction "TDI_Y18") (pintype "bidirectional"))
      (node (ref "X4") (pin "3") (pinfunction "TDI_3") (pintype "bidirectional"))
    )
    (net (code "58") (name "/JTAG_TDO") (class "Default")
      (node (ref "U1") (pin "W18") (pinfunction "TDO_W18") (pintype "bidirectional"))
      (node (ref "X4") (pin "7") (pinfunction "TDO_7") (pintype "bidirectional"))
    )
    (net (code "59") (name "/JTAG_TMS") (class "Default")
      (node (ref "U1") (pin "W19") (pinfunction "TMS_W19") (pintype "bidirectional"))
      (node (ref "X4") (pin "1") (pinfunction "TMS_1") (pintype "bidirectional"))
    )
    (net (code "60") (name "/JTAG_TRSTN") (class "Default")
      (node (ref "R39") (pin "2") (pinfunction "2_2") (pintype "passive"))
      (node (ref "U1") (pin "W20") (pinfunction "TRSTN_W20") (pintype "bidirectional"))
      (node (ref "X4") (pin "2") (pinfunction "TRSTN_2") (pintype "bidirectional"))
    )
    (net (code "61") (name "/LCD_DATA0") (class "Default")
      (node (ref "R68") (pin "2") (pinfunction "2_2") (pintype "passive"))
      (node (ref "R85") (pin "1") (pinfunction "1_1") (pintype "passive"))
      (node (ref "U1") (pin "T18") (pinfunction "LCD_DATA0_T18") (pintype "bidirectional"))
      (node (ref "X7") (pin "19") (pinfunction "19_19") (pintype "bidirectional"))
    )
    (net (code "62") (name "/LCD_DATA1") (class "Default")
      (node (ref "R67") (pin "2") (pinfunction "2_2") (pintype "passive"))
      (node (ref "R84") (pin "1") (pinfunction "1_1") (pintype "passive"))
      (node (ref "U1") (pin "T19") (pinfunction "LCD_DATA1_T19") (pintype "bidirectional"))
      (node (ref "X7") (pin "20") (pinfunction "20_20") (pintype "bidirectional"))
    )
    (net (code "63") (name "/LCD_DATA2") (class "Default")
      (node (ref "R66") (pin "2") (pinfunction "2_2") (pintype "passive"))
      (node (ref "R69") (pin "1") (pinfunction "1_1") (pintype "passive"))
      (node (ref "R83") (pin "1") (pinfunction "1_1") (pintype "passive"))
      (node (ref "U1") (pin "T20") (pinfunction "LCD_DATA2_T20") (pintype "bidirectional"))
      (node (ref "X7") (pin "17") (pinfunction "17_17") (pintype "bidirectional"))
    )
    (net (code "64") (name "/LCD_DATA3") (class "Default")
      (node (ref "R65") (pin "2") (pinfunction "2_2") (pintype "passive"))
      (node (ref "R82") (pin "1") (pinfunction "1_1") (pintype "passive"))
      (node (ref "U1") (pin "R18") (pinfunction "LCD_DATA3_R18") (pintype "bidirectional"))
      (node (ref "X7") (pin "18") (pinfunction "18_18") (pintype "bidirectional"))
    )
    (net (code "65") (name "/LCD_DATA4") (class "Default")
      (node (ref "R64") (pin "2") (pinfunction "2_2") (pintype "passive"))
      (node (ref "R81") (pin "1") (pinfunction "1_1") (pintype "passive"))
      (node (ref "U1") (pin "R19") (pinfunction "LCD_DATA4_R19") (pintype "bidirectional"))
      (node (ref "X7") (pin "15") (pinfunction "15_15") (pintype "bidirectional"))
    )
    (net (code "66") (name "/LCD_DATA5") (class "Default")
      (node (ref "R63") (pin "2") (pinfunction "2_2") (pintype "passive"))
      (node (ref "R80") (pin "1") (pinfunction "1_1") (pintype "passive"))
      (node (ref "U1") (pin "R20") (pinfunction "LCD_DATA5_R20") (pintype "bidirectional"))
      (node (ref "X7") (pin "16") (pinfunction "16_16") (pintype "bidirectional"))
    )
    (net (code "67") (name "/LCD_DATA6") (class "Default")
      (node (ref "R62") (pin "2") (pinfunction "2_2") (pintype "passive"))
      (node (ref "R79") (pin "1") (pinfunction "1_1") (pintype "passive"))
      (node (ref "U1") (pin "P18") (pinfunction "LCD_DATA6_P18") (pintype "bidirectional"))
      (node (ref "X7") (pin "13") (pinfunction "13_13") (pintype "bidirectional"))
    )
    (net (code "68") (name "/LCD_DATA7") (class "Default")
      (node (ref "R61") (pin "2") (pinfunction "2_2") (pintype "passive"))
      (node (ref "R78") (pin "1") (pinfunction "1_1") (pintype "passive"))
      (node (ref "U1") (pin "P19") (pinfunction "LCD_DATA7_P19") (pintype "bidirectional"))
      (node (ref "X7") (pin "14") (pinfunction "14_14") (pintype "bidirectional"))
    )
    (net (code "69") (name "/LCD_DATA8") (class "Default")
      (node (ref "R60") (pin "2") (pinfunction "2_2") (pintype "passive"))
      (node (ref "R77") (pin "1") (pinfunction "1_1") (pintype "passive"))
      (node (ref "U1") (pin "P20") (pinfunction "LCD_DATA8_P20") (pintype "bidirectional"))
      (node (ref "X7") (pin "11") (pinfunction "11_11") (pintype "bidirectional"))
    )
    (net (code "70") (name "/LCD_DATA9") (class "Default")
      (node (ref "R59") (pin "2") (pinfunction "2_2") (pintype "passive"))
      (node (ref "R76") (pin "1") (pinfunction "1_1") (pintype "passive"))
      (node (ref "U1") (pin "N18") (pinfunction "LCD_DATA9_N18") (pintype "bidirectional"))
      (node (ref "X7") (pin "12") (pinfunction "12_12") (pintype "bidirectional"))
    )
    (net (code "71") (name "/LCD_DATA10") (class "Default")
      (node (ref "R58") (pin "2") (pinfunction "2_2") (pintype "passive"))
      (node (ref "R75") (pin "1") (pinfunction "1_1") (pintype "passive"))
      (node (ref "U1") (pin "N19") (pinfunction "LCD_DATA10_N19") (pintype "bidirectional"))
      (node (ref "X7") (pin "10") (pinfunction "10_10") (pintype "bidirectional"))
    )
    (net (code "72") (name "/LCD_DATA11") (class "Default")
      (node (ref "R57") (pin "2") (pinfunction "2_2") (pintype "passive"))
      (node (ref "R74") (pin "1") (pinfunction "1_1") (pintype "passive"))
      (node (ref "U1") (pin "N20") (pinfunction "LCD_DATA11_N20") (pintype "bidirectional"))
      (node (ref "X7") (pin "8") (pinfunction "8_8") (pintype "bidirectional"))
    )
    (net (code "73") (name "/LCD_DATA12") (class "Default")
      (node (ref "R56") (pin "2") (pinfunction "2_2") (pintype "passive"))
      (node (ref "R73") (pin "1") (pinfunction "1_1") (pintype "passive"))
      (node (ref "U1") (pin "M18") (pinfunction "LCD_DATA12_M18") (pintype "bidirectional"))
      (node (ref "X7") (pin "9") (pinfunction "9_9") (pintype "bidirectional"))
    )
    (net (code "74") (name "/LCD_DATA13") (class "Default")
      (node (ref "R55") (pin "2") (pinfunction "2_2") (pintype "passive"))
      (node (ref "R72") (pin "1") (pinfunction "1_1") (pintype "passive"))
      (node (ref "U1") (pin "M19") (pinfunction "LCD_DATA13_M19") (pintype "bidirectional"))
      (node (ref "X7") (pin "7") (pinfunction "7_7") (pintype "bidirectional"))
    )
    (net (code "75") (name "/LCD_DATA14") (class "Default")
      (node (ref "R54") (pin "2") (pinfunction "2_2") (pintype "passive"))
      (node (ref "R71") (pin "1") (pinfunction "1_1") (pintype "passive"))
      (node (ref "U1") (pin "M20") (pinfunction "LCD_DATA14_M20") (pintype "bidirectional"))
      (node (ref "X7") (pin "5") (pinfunction "5_5") (pintype "bidirectional"))
    )
    (net (code "76") (name "/LCD_DATA15") (class "Default")
      (node (ref "R53") (pin "2") (pinfunction "2_2") (pintype "passive"))
      (node (ref "R70") (pin "1") (pinfunction "1_1") (pintype "passive"))
      (node (ref "U1") (pin "L18") (pinfunction "LCD_DATA15_L18") (pintype "bidirectional"))
      (node (ref "X7") (pin "6") (pinfunction "6_6") (pintype "bidirectional"))
    )
    (net (code "77") (name "/LCD_DE") (class "Default")
      (node (ref "R28") (pin "2") (pinfunction "2_2") (pintype "passive"))
      (node (ref "X7") (pin "4") (pinfunction "4_4") (pintype "bidirectional"))
    )
    (net (code "78") (name "/LCD_HSYNC") (class "Default")
      (node (ref "R29") (pin "2") (pinfunction "2_2") (pintype "passive"))
      (node (ref "X7") (pin "3") (pinfunction "3_3") (pintype "bidirectional"))
    )
    (net (code "79") (name "/LCD_PCLK") (class "Default")
      (node (ref "R31") (pin "2") (pinfunction "2_2") (pintype "passive"))
      (node (ref "X7") (pin "2") (pinfunction "2_2") (pintype "bidirectional"))
    )
    (net (code "80") (name "/LCD_VSYNC") (class "Default")
      (node (ref "R30") (pin "2") (pinfunction "2_2") (pintype "passive"))
      (node (ref "X7") (pin "1") (pinfunction "1_1") (pintype "bidirectional"))
    )
    (net (code "81") (name "/LDO_PGOOD") (class "Default")
      (node (ref "TP22") (pin "TP") (pinfunction "TP_TP") (pintype "input"))
      (node (ref "U1") (pin "D13") (pinfunction "RTC_PWRONRSTN_D13") (pintype "bidirectional"))
      (node (ref "U1") (pin "D14") (pinfunction "PMIC_LDO_PGOOD_D14") (pintype "output"))
    )
    (net (code "82") (name "/MDIO_CLK") (class "Default")
      (node (ref "U1") (pin "W1") (pinfunction "MDC_W1") (pintype "bidirectional"))
      (node (ref "U27") (pin "17") (pinfunction "MDC_17") (pintype "input"))
    )
    (net (code "83") (name "/MDIO_DATA") (class "Default")
      (node (ref "ER105") (pin "2") (pinfunction "2_2") (pintype "passive"))
      (node (ref "U1") (pin "V1") (pinfunction "MDIO_V1") (pintype "bidirectional"))
      (node (ref "U27") (pin "16") (pinfunction "MDIO_16") (pintype "bidirectional"))
    )
    (net (code "84") (name "/MII1_COL") (class "Default")
      (node (ref "ER123") (pin "2") (pinfunction "2_2") (pintype "passive"))
      (node (ref "U1") (pin "R2") (pinfunction "MII1_COL_R2") (pintype "bidirectional"))
    )
    (net (code "85") (name "/MII1_CRS") (class "Default")
      (node (ref "ER124") (pin "2") (pinfunction "2_2") (pintype "passive"))
      (node (ref "U1") (pin "R3") (pinfunction "MII1_CRS_R3") (pintype "bidirectional"))
    )
    (net (code "86") (name "/MII1_RXCLK") (class "Default")
      (node (ref "ER116") (pin "2") (pinfunction "2_2") (pintype "passive"))
      (node (ref "U1") (pin "T1") (pinfunction "MII1_RX_CLK_T1") (pintype "bidirectional"))
    )
    (net (code "87") (name "/MII1_RXD0") (class "Default")
      (node (ref "ER113") (pin "2") (pinfunction "2_2") (pintype "passive"))
      (node (ref "U1") (pin "T3") (pinfunction "MII1_RXD0_T3") (pintype "bidirectional"))
    )
    (net (code "88") (name "/MII1_RXD1") (class "Default")
      (node (ref "ER112") (pin "2") (pinfunction "2_2") (pintype "passive"))
      (node (ref "U1") (pin "U1") (pinfunction "MII1_RXD1_U1") (pintype "bidirectional"))
    )
    (net (code "89") (name "/MII1_RXD2") (class "Default")
      (node (ref "ER111") (pin "2") (pinfunction "2_2") (pintype "passive"))
      (node (ref "U1") (pin "U2") (pinfunction "MII1_RXD2_U2") (pintype "bidirectional"))
    )
    (net (code "90") (name "/MII1_RXD3") (class "Default")
      (node (ref "ER110") (pin "2") (pinfunction "2_2") (pintype "passive"))
      (node (ref "U1") (pin "U3") (pinfunction "MII1_RXD3_U3") (pintype "bidirectional"))
    )
    (net (code "91") (name "/MII1_RXDV") (class "Default")
      (node (ref "ER114") (pin "2") (pinfunction "2_2") (pintype "passive"))
      (node (ref "U1") (pin "R1") (pinfunction "MII1_RX_DV_R1") (pintype "bidirectional"))
    )
    (net (code "92") (name "/MII1_RXERR") (class "Default")
      (node (ref "ER118") (pin "2") (pinfunction "2_2") (pintype "passive"))
      (node (ref "U1") (pin "T2") (pinfunction "MII1_RX_ER_T2") (pintype "bidirectional"))
    )
    (net (code "93") (name "/MII1_TXCLK") (class "Default")
      (node (ref "ER119") (pin "2") (pinfunction "2_2") (pintype "passive"))
      (node (ref "U1") (pin "N1") (pinfunction "MII1_TX_CLK_N1") (pintype "bidirectional"))
    )
    (net (code "94") (name "/MII1_TXD0") (class "Default")
      (node (ref "U1") (pin "N2") (pinfunction "MII1_TXD0_N2") (pintype "bidirectional"))
      (node (ref "U27") (pin "22") (pinfunction "TXD0_22") (pintype "input"))
    )
    (net (code "95") (name "/MII1_TXD1") (class "Default")
      (node (ref "U1") (pin "N3") (pinfunction "MII1_TXD1_N3") (pintype "bidirectional"))
      (node (ref "U27") (pin "23") (pinfunction "TXD1_23") (pintype "input"))
    )
    (net (code "96") (name "/MII1_TXD2") (class "Default")
      (node (ref "U1") (pin "P1") (pinfunction "MII1_TXD2_P1") (pintype "bidirectional"))
      (node (ref "U27") (pin "24") (pinfunction "TXD2_24") (pintype "input"))
    )
    (net (code "97") (name "/MII1_TXD3") (class "Default")
      (node (ref "U1") (pin "P2") (pinfunction "MII1_TXD3_P2") (pintype "bidirectional"))
      (node (ref "U27") (pin "25") (pinfunction "TXD3_25") (pintype "input"))
    )
    (net (code "98") (name "/MII1_TXEN") (class "Default")
      (node (ref "U1") (pin "P3") (pinfunction "MII1_TX_EN_P3") (pintype "bidirectional"))
      (node (ref "U27") (pin "21") (pinfunction "TXEN_21") (pintype "input"))
    )
    (net (code "99") (name "/MMC0_CD") (class "Default")
      (node (ref "R92") (pin "1") (pinfunction "1_1") (pintype "passive"))
      (node (ref "U1") (pin "V4") (pinfunction "SPI0_CS1_V4") (pintype "bidirectional"))
      (node (ref "X4") (pin "19") (pinfunction "EMU4_19") (pintype "bidirectional"))
      (node (ref "X5") (pin "12") (pinfunction "CARD_DETECTION_SWITCH_12") (pintype "bidirectional"))
    )
    (net (code "100") (name "/MMC0_CLK") (class "Default")
      (node (ref "R88") (pin "1") (pinfunction "1_1") (pintype "passive"))
      (node (ref "U1") (pin "W3") (pinfunction "MMC0_CLK_W3") (pintype "bidirectional"))
      (node (ref "X5") (pin "5") (pinfunction "CLK_5") (pintype "bidirectional"))
    )
    (net (code "101") (name "/MMC0_CMD") (class "Default")
      (node (ref "R87") (pin "1") (pinfunction "1_1") (pintype "passive"))
      (node (ref "U1") (pin "W2") (pinfunction "MMC0_CMD_W2") (pintype "bidirectional"))
      (node (ref "X5") (pin "3") (pinfunction "CMD_3") (pintype "bidirectional"))
    )
    (net (code "102") (name "/MMC0_DAT0") (class "Default")
      (node (ref "R89") (pin "1") (pinfunction "1_1") (pintype "passive"))
      (node (ref "U1") (pin "Y3") (pinfunction "MMC0_DAT0_Y3") (pintype "bidirectional"))
      (node (ref "X5") (pin "7") (pinfunction "DAT0_7") (pintype "bidirectional"))
    )
    (net (code "103") (name "/MMC0_DAT1") (class "Default")
      (node (ref "R90") (pin "1") (pinfunction "1_1") (pintype "passive"))
      (node (ref "U1") (pin "V3") (pinfunction "MMC0_DAT1_V3") (pintype "bidirectional"))
      (node (ref "X5") (pin "8") (pinfunction "DAT1_8") (pintype "bidirectional"))
    )
    (net (code "104") (name "/MMC0_DAT2") (class "Default")
      (node (ref "R86") (pin "1") (pinfunction "1_1") (pintype "passive"))
      (node (ref "U1") (pin "V2") (pinfunction "MMC0_DAT2_V2") (pintype "bidirectional"))
      (node (ref "X5") (pin "1") (pinfunction "DAT2_1") (pintype "bidirectional"))
    )
    (net (code "105") (name "/MMC0_DAT3") (class "Default")
      (node (ref "R91") (pin "1") (pinfunction "1_1") (pintype "passive"))
      (node (ref "U1") (pin "Y2") (pinfunction "MMC0_DAT3_Y2") (pintype "bidirectional"))
      (node (ref "X5") (pin "2") (pinfunction "CD/DAT3_2") (pintype "bidirectional"))
    )
    (net (code "106") (name "/MODE2") (class "Default")
      (node (ref "ER123") (pin "1") (pinfunction "1_1") (pintype "passive"))
      (node (ref "ER99") (pin "2") (pinfunction "2_2") (pintype "passive"))
      (node (ref "U27") (pin "15") (pinfunction "COL/CRS_DV/MODE2_15") (pintype "bidirectional"))
    )
    (net (code "107") (name "/OSC1_IN") (class "Default")
      (node (ref "R164") (pin "2") (pinfunction "2_2") (pintype "passive"))
      (node (ref "RTC1") (pin "1") (pinfunction "32KHZ_1") (pintype "output"))
      (node (ref "U1") (pin "Y13") (pinfunction "OSC1_IN_Y13") (pintype "bidirectional"))
    )
    (net (code "108") (name "/OSC1_OUT") (class "Default")
      (node (ref "U1") (pin "Y14") (pinfunction "OSC1_OUT_Y14") (pintype "bidirectional"))
    )
    (net (code "109") (name "/OSC_CTL") (class "Default")
      (node (ref "TP32") (pin "TP") (pinfunction "TP_TP") (pintype "input"))
      (node (ref "U1") (pin "M1") (pinfunction "OSC0_CTL_M1") (pintype "bidirectional"))
    )
    (net (code "110") (name "/PMIC_INT") (class "Default")
      (node (ref "TP24") (pin "TP") (pinfunction "TP_TP") (pintype "input"))
      (node (ref "U1") (pin "J17") (pinfunction "PMIC_NINT_J17") (pintype "output"))
      (node (ref "U1") (pin "K17") (pinfunction "EXTINTN_K17") (pintype "bidirectional"))
    )
    (net (code "111") (name "/PMIC_MUX_IN") (class "Default")
      (node (ref "R18") (pin "2") (pinfunction "2_2") (pintype "passive"))
      (node (ref "R22") (pin "1") (pinfunction "1_1") (pintype "passive"))
      (node (ref "U1") (pin "F19") (pinfunction "PMIC_MUX_IN_F19") (pintype "bidirectional"))
    )
    (net (code "112") (name "/PMIC_NRESET") (class "Default")
      (node (ref "J2") (pin "1") (pinfunction "1_1") (pintype "bidirectional"))
      (node (ref "U1") (pin "A19") (pinfunction "PMIC_NRESET_A19") (pintype "bidirectional"))
    )
    (net (code "113") (name "/PMIC_NWAKEUP") (class "Default")
      (node (ref "TP23") (pin "TP") (pinfunction "TP_TP") (pintype "input"))
      (node (ref "U1") (pin "G17") (pinfunction "PMIC_NWAKEUP_G17") (pintype "output"))
      (node (ref "U1") (pin "H17") (pinfunction "EXT_WAKEUP_H17") (pintype "bidirectional"))
    )
    (net (code "114") (name "/PMIC_PGOOD") (class "Default")
      (node (ref "TP26") (pin "TP") (pinfunction "TP_TP") (pintype "input"))
      (node (ref "U1") (pin "D11") (pinfunction "PWRONRSTN_D11") (pintype "bidirectional"))
      (node (ref "U1") (pin "D12") (pinfunction "PMIC_PGOOD_D12") (pintype "output"))
    )
    (net (code "115") (name "/PWR_BUT") (class "Default")
      (node (ref "S2") (pin "2") (pinfunction "2_2") (pintype "bidirectional"))
      (node (ref "S2") (pin "4") (pinfunction "4_4") (pintype "bidirectional"))
      (node (ref "U1") (pin "A18") (pinfunction "PMIC_PB_IN_A18") (pintype "bidirectional"))
    )
    (net (code "116") (name "/PWR_EN") (class "Default")
      (node (ref "TP21") (pin "TP") (pinfunction "TP_TP") (pintype "input"))
      (node (ref "U1") (pin "D10") (pinfunction "PMIC_PWR_EN_D10") (pintype "input"))
      (node (ref "U1") (pin "D9") (pinfunction "PMIC_POWER_EN_D9") (pintype "output"))
    )
    (net (code "117") (name "/RTC_RST") (class "Default")
      (node (ref "R163") (pin "1") (pinfunction "1_1") (pintype "passive"))
      (node (ref "RTC1") (pin "4") (pinfunction "RST_4") (pintype "bidirectional"))
      (node (ref "U1") (pin "K20") (pinfunction "GPMC_CSN0_K20") (pintype "bidirectional"))
    )
    (net (code "118") (name "/RXD0") (class "Default")
      (node (ref "ER113") (pin "1") (pinfunction "1_1") (pintype "passive"))
      (node (ref "ER98") (pin "2") (pinfunction "2_2") (pintype "passive"))
      (node (ref "U27") (pin "11") (pinfunction "RXD0/MODE0_11") (pintype "bidirectional"))
    )
    (net (code "119") (name "/RXD1") (class "Default")
      (node (ref "ER100") (pin "2") (pinfunction "2_2") (pintype "passive"))
      (node (ref "ER112") (pin "1") (pinfunction "1_1") (pintype "passive"))
      (node (ref "U27") (pin "10") (pinfunction "RXD1/MODE1_10") (pintype "bidirectional"))
    )
    (net (code "120") (name "/RXD2") (class "Default")
      (node (ref "ER103") (pin "1") (pinfunction "1_1") (pintype "passive"))
      (node (ref "ER111") (pin "1") (pinfunction "1_1") (pintype "passive"))
      (node (ref "U27") (pin "9") (pinfunction "RXD2/RMIISEL_9") (pintype "bidirectional"))
    )
    (net (code "121") (name "/RXD3") (class "Default")
      (node (ref "ER102") (pin "1") (pinfunction "1_1") (pintype "passive"))
      (node (ref "ER110") (pin "1") (pinfunction "1_1") (pintype "passive"))
      (node (ref "U27") (pin "8") (pinfunction "RXD3/PHYAD2_8") (pintype "bidirectional"))
    )
    (net (code "122") (name "/RX_CLK") (class "Default")
      (node (ref "ER104") (pin "1") (pinfunction "1_1") (pintype "passive"))
      (node (ref "ER116") (pin "1") (pinfunction "1_1") (pintype "passive"))
      (node (ref "U27") (pin "7") (pinfunction "RXCLK/PHYAD1_7") (pintype "bidirectional"))
    )
    (net (code "123") (name "/RX_DV") (class "Default")
      (node (ref "ER114") (pin "1") (pinfunction "1_1") (pintype "passive"))
      (node (ref "U27") (pin "26") (pinfunction "RXDV_26") (pintype "bidirectional"))
    )
    (net (code "124") (name "/RX_ERR") (class "Default")
      (node (ref "ER101") (pin "1") (pinfunction "1_1") (pintype "passive"))
      (node (ref "ER118") (pin "1") (pinfunction "1_1") (pintype "passive"))
      (node (ref "U27") (pin "13") (pinfunction "RXER/RXD4/PHYAD0_13") (pintype "bidirectional"))
    )
    (net (code "125") (name "/RX_N") (class "Default")
      (node (ref "EC37") (pin "1") (pinfunction "1_1") (pintype "passive"))
      (node (ref "ER107") (pin "2") (pinfunction "2_2") (pintype "passive"))
      (node (ref "U27") (pin "30") (pinfunction "RXN_30") (pintype "bidirectional"))
      (node (ref "X2") (pin "6") (pinfunction "RXN_6") (pintype "passive"))
    )
    (net (code "126") (name "/RX_P") (class "Default")
      (node (ref "EC36") (pin "1") (pinfunction "1_1") (pintype "passive"))
      (node (ref "ER106") (pin "2") (pinfunction "2_2") (pintype "passive"))
      (node (ref "U27") (pin "31") (pinfunction "RXP_31") (pintype "bidirectional"))
      (node (ref "X2") (pin "3") (pinfunction "RXP_3") (pintype "passive"))
    )
    (net (code "127") (name "/SPI1_CS0") (class "Default")
      (node (ref "IC4") (pin "1") (pinfunction "SH/~{LD}_1") (pintype "input"))
      (node (ref "IC5") (pin "1") (pinfunction "SH/~{LD}_1") (pintype "input"))
      (node (ref "U1") (pin "W17") (pinfunction "MCASP0_AHCLKR_W17") (pintype "bidirectional"))
    )
    (net (code "128") (name "/SPI1_D0") (class "Default")
      (node (ref "IC4") (pin "9") (pinfunction "QH_9") (pintype "output"))
      (node (ref "U1") (pin "Y16") (pinfunction "MCASP0_FSX_Y16") (pintype "bidirectional"))
    )
    (net (code "129") (name "/SPI1_D1") (class "Default")
      (node (ref "U1") (pin "W16") (pinfunction "MCASP0_AXR0_W16") (pintype "bidirectional"))
    )
    (net (code "130") (name "/SPI1_SCLK") (class "Default")
      (node (ref "IC4") (pin "2") (pinfunction "CLK_2") (pintype "input"))
      (node (ref "IC5") (pin "2") (pinfunction "CLK_2") (pintype "input"))
      (node (ref "U1") (pin "Y17") (pinfunction "MCASP0_ACLKX_Y17") (pintype "bidirectional"))
    )
    (net (code "131") (name "/SYS_RESETN") (class "Default")
      (node (ref "C14") (pin "1") (pinfunction "1_1") (pintype "passive"))
      (node (ref "R6") (pin "2") (pinfunction "2_2") (pintype "passive"))
      (node (ref "R8") (pin "1") (pinfunction "1_1") (pintype "passive"))
      (node (ref "TP31") (pin "TP") (pinfunction "TP_TP") (pintype "input"))
      (node (ref "U1") (pin "B17") (pinfunction "WARMRSTN_B17") (pintype "bidirectional"))
      (node (ref "U16") (pin "17") (pinfunction "LRESET#_17") (pintype "bidirectional"))
      (node (ref "U27") (pin "19") (pinfunction "~{RST}_19") (pintype "bidirectional"))
      (node (ref "X4") (pin "15") (pinfunction "SRST_15") (pintype "bidirectional"))
    )
    (net (code "132") (name "/TEMP_SENSE") (class "Default")
      (node (ref "TP7") (pin "P$1") (pinfunction "TP_P$1") (pintype "bidirectional"))
      (node (ref "U1") (pin "E20") (pinfunction "PMIC_TS_E20") (pintype "bidirectional"))
    )
    (net (code "133") (name "/TPM_GPIO0") (class "Default")
      (node (ref "U1") (pin "W15") (pinfunction "MCASP0_FSR_W15") (pintype "bidirectional"))
      (node (ref "U16") (pin "12") (pinfunction "GPIO_12") (pintype "bidirectional"))
    )
    (net (code "134") (name "/TPM_GPIO1") (class "Default")
      (node (ref "TP9") (pin "P$1") (pinfunction "TP_P$1") (pintype "bidirectional"))
      (node (ref "U1") (pin "W8") (pinfunction "UART1_CTSN_W8") (pintype "bidirectional"))
      (node (ref "U16") (pin "3") (pinfunction "GPIO-EXPRESS-00_3") (pintype "bidirectional"))
    )
    (net (code "135") (name "/TPM_GPIO2") (class "Default")
      (node (ref "TP10") (pin "P$1") (pinfunction "TP_P$1") (pintype "bidirectional"))
      (node (ref "U1") (pin "Y8") (pinfunction "UART1_RTSN_Y8") (pintype "bidirectional"))
      (node (ref "U16") (pin "4") (pinfunction "PP/GPIO_4") (pintype "bidirectional"))
    )
    (net (code "136") (name "/TX_CLK") (class "Default")
      (node (ref "ER119") (pin "1") (pinfunction "1_1") (pintype "passive"))
      (node (ref "U27") (pin "20") (pinfunction "TXCLK_20") (pintype "bidirectional"))
    )
    (net (code "137") (name "/TX_N") (class "Default")
      (node (ref "EC39") (pin "1") (pinfunction "1_1") (pintype "passive"))
      (node (ref "ER109") (pin "2") (pinfunction "2_2") (pintype "passive"))
      (node (ref "U27") (pin "28") (pinfunction "TXN_28") (pintype "bidirectional"))
      (node (ref "X2") (pin "2") (pinfunction "TXN_2") (pintype "passive"))
    )
    (net (code "138") (name "/TX_P") (class "Default")
      (node (ref "EC38") (pin "1") (pinfunction "1_1") (pintype "passive"))
      (node (ref "ER108") (pin "2") (pinfunction "2_2") (pintype "passive"))
      (node (ref "U27") (pin "29") (pinfunction "TXP_29") (pintype "bidirectional"))
      (node (ref "X2") (pin "1") (pinfunction "TXP_1") (pintype "passive"))
    )
    (net (code "139") (name "/UART0_RX") (class "Default")
      (node (ref "U1") (pin "Y6") (pinfunction "UART0_RXD_Y6") (pintype "bidirectional"))
      (node (ref "U6") (pin "6") (pinfunction "1Y_6") (pintype "output"))
    )
    (net (code "140") (name "/UART0_TX") (class "Default")
      (node (ref "U1") (pin "W6") (pinfunction "UART0_TXD_W6") (pintype "bidirectional"))
      (node (ref "U6") (pin "5") (pinfunction "2A_5") (pintype "input"))
    )
    (net (code "141") (name "/UART2_RXD") (class "Default")
      (node (ref "D302") (pin "1") (pinfunction "A_1") (pintype "passive"))
      (node (ref "U1") (pin "Y5") (pinfunction "SPI0_SCLK_Y5") (pintype "bidirectional"))
      (node (ref "U29") (pin "1") (pinfunction "RO_1") (pintype "output"))
    )
    (net (code "142") (name "/UART2_TXD") (class "Default")
      (node (ref "D301") (pin "1") (pinfunction "A_1") (pintype "passive"))
      (node (ref "U1") (pin "W5") (pinfunction "SPI0_D0_W5") (pintype "bidirectional"))
      (node (ref "U29") (pin "4") (pinfunction "DI_4") (pintype "input"))
    )
    (net (code "143") (name "/UART4_RXD") (class "Default")
      (node (ref "D402") (pin "1") (pinfunction "A_1") (pintype "passive"))
      (node (ref "U1") (pin "B9") (pinfunction "GPMC_WAIT0_B9") (pintype "bidirectional"))
      (node (ref "U40") (pin "5") (pinfunction "R_5") (pintype "passive"))
    )
    (net (code "144") (name "/UART4_TXD") (class "Default")
      (node (ref "D401") (pin "1") (pinfunction "A_1") (pintype "passive"))
      (node (ref "U1") (pin "A9") (pinfunction "GPMC_WPN_A9") (pintype "bidirectional"))
      (node (ref "U40") (pin "8") (pinfunction "D_8") (pintype "passive"))
    )
    (net (code "145") (name "/USB0_ID") (class "Default")
      (node (ref "U1") (pin "L1") (pinfunction "USB0_ID_L1") (pintype "bidirectional"))
      (node (ref "U2") (pin "3") (pinfunction "ID_3") (pintype "passive"))
      (node (ref "X1") (pin "ID") (pinfunction "ID_ID") (pintype "input"))
    )
    (net (code "146") (name "/USB0_N") (class "Default")
      (node (ref "U1") (pin "K2") (pinfunction "USB0_DM_K2") (pintype "bidirectional"))
      (node (ref "U2") (pin "1") (pinfunction "D-_1") (pintype "passive"))
      (node (ref "X1") (pin "D-") (pinfunction "D-_D-") (pintype "input"))
    )
    (net (code "147") (name "/USB0_P") (class "Default")
      (node (ref "U1") (pin "L2") (pinfunction "USB0_DP_L2") (pintype "bidirectional"))
      (node (ref "U2") (pin "2") (pinfunction "D+_2") (pintype "passive"))
      (node (ref "X1") (pin "D+") (pinfunction "D+_D+") (pintype "input"))
    )
    (net (code "148") (name "/USR0") (class "Default")
      (node (ref "D7") (pin "1") (pinfunction "A_1") (pintype "passive"))
      (node (ref "U1") (pin "C12") (pinfunction "GPMC_A5_C12") (pintype "bidirectional"))
    )
    (net (code "149") (name "/USR1") (class "Default")
      (node (ref "D6") (pin "1") (pinfunction "A_1") (pintype "passive"))
      (node (ref "U1") (pin "A11") (pinfunction "GPMC_A6_A11") (pintype "bidirectional"))
    )
    (net (code "150") (name "/USR2") (class "Default")
      (node (ref "D5") (pin "1") (pinfunction "A_1") (pintype "passive"))
      (node (ref "U1") (pin "B11") (pinfunction "GPMC_A7_B11") (pintype "bidirectional"))
    )
    (net (code "151") (name "/USR3") (class "Default")
      (node (ref "D4") (pin "1") (pinfunction "A_1") (pintype "passive"))
      (node (ref "U1") (pin "C11") (pinfunction "GPMC_A8_C11") (pintype "bidirectional"))
    )
    (net (code "152") (name "/VDDS_DDR") (class "Default")
      (node (ref "TP2") (pin "TP") (pinfunction "TP_TP") (pintype "input"))
      (node (ref "U1") (pin "U9") (pinfunction "VDDS_DDR_U9") (pintype "bidirectional"))
    )
    (net (code "153") (name "/VDDS_PLL") (class "Default")
      (node (ref "TP3") (pin "TP") (pinfunction "TP_TP") (pintype "input"))
      (node (ref "U1") (pin "U10") (pinfunction "VDDS_PLL_U10") (pintype "bidirectional"))
    )
    (net (code "154") (name "/VDD_CORE") (class "Default")
      (node (ref "TP4") (pin "TP") (pinfunction "TP_TP") (pintype "input"))
      (node (ref "U1") (pin "U13") (pinfunction "VDD_CORE_U13") (pintype "bidirectional"))
    )
    (net (code "155") (name "/VDD_MPU") (class "Default")
      (node (ref "TP1") (pin "TP") (pinfunction "TP_TP") (pintype "input"))
      (node (ref "U1") (pin "U6") (pinfunction "VDD_MPU_U6") (pintype "bidirectional"))
    )
    (net (code "156") (name "/VIO") (class "Default")
      (node (ref "U28") (pin "5") (pinfunction "VIO_5") (pintype "power_in"))
    )
    (net (code "157") (name "/VREFN") (class "Default")
      (node (ref "R25") (pin "1") (pinfunction "1_1") (pintype "passive"))
      (node (ref "U1") (pin "W9") (pinfunction "VREFN_W9") (pintype "bidirectional"))
    )
    (net (code "158") (name "/VREFP") (class "Default")
      (node (ref "C8") (pin "1") (pinfunction "1_1") (pintype "passive"))
      (node (ref "C9") (pin "1") (pinfunction "1_1") (pintype "passive"))
      (node (ref "R33") (pin "1") (pinfunction "1_1") (pintype "passive"))
      (node (ref "U1") (pin "W12") (pinfunction "VREFP_W12") (pintype "bidirectional"))
    )
    (net (code "159") (name "/XDMA_EVENT_INTR0") (class "Default")
      (node (ref "C1") (pin "2") (pinfunction "2_2") (pintype "passive"))
      (node (ref "R4") (pin "2") (pinfunction "2_2") (pintype "passive"))
      (node (ref "X4") (pin "17") (pinfunction "EMU2_17") (pintype "bidirectional"))
    )
    (net (code "160") (name "24VDC_AUX") (class "Default")
      (node (ref "C106") (pin "1") (pinfunction "1_1") (pintype "passive"))
      (node (ref "D19") (pin "1") (pinfunction "A_1") (pintype "passive"))
      (node (ref "D31") (pin "1") (pinfunction "A_1") (pintype "passive"))
      (node (ref "D32") (pin "1") (pinfunction "A_1") (pintype "passive"))
      (node (ref "D33") (pin "1") (pinfunction "A_1") (pintype "passive"))
      (node (ref "D34") (pin "1") (pinfunction "A_1") (pintype "passive"))
      (node (ref "D35") (pin "1") (pinfunction "A_1") (pintype "passive"))
      (node (ref "IC2") (pin "9") (pinfunction "CD+_9") (pintype "passive"))
      (node (ref "J24") (pin "3") (pinfunction "3_3") (pintype "bidirectional"))
      (node (ref "K1") (pin "1") (pinfunction "1_1") (pintype "passive"))
      (node (ref "K2") (pin "1") (pinfunction "1_1") (pintype "passive"))
      (node (ref "K3") (pin "1") (pinfunction "1_1") (pintype "passive"))
      (node (ref "K4") (pin "1") (pinfunction "1_1") (pintype "passive"))
      (node (ref "K5") (pin "1") (pinfunction "1_1") (pintype "passive"))
      (node (ref "VREG2") (pin "OUT") (pinfunction "OUT_OUT") (pintype "passive"))
      (node (ref "X8") (pin "4") (pinfunction "SK_4") (pintype "passive"))
    )
    (net (code "161") (name "AGND") (class "Default")
      (node (ref "C10") (pin "2") (pinfunction "2_2") (pintype "passive"))
      (node (ref "C111") (pin "2") (pinfunction "2_2") (pintype "passive"))
      (node (ref "C121") (pin "2") (pinfunction "2_2") (pintype "passive"))
      (node (ref "C131") (pin "2") (pinfunction "2_2") (pintype "passive"))
      (node (ref "C141") (pin "2") (pinfunction "2_2") (pintype "passive"))
      (node (ref "C151") (pin "2") (pinfunction "2_2") (pintype "passive"))
      (node (ref "C161") (pin "2") (pinfunction "2_2") (pintype "passive"))
      (node (ref "C8") (pin "2") (pinfunction "2_2") (pintype "passive"))
      (node (ref "C9") (pin "2") (pinfunction "2_2") (pintype "passive"))
      (node (ref "IC10") (pin "4") (pinfunction "V-_4") (pintype "power_in"))
      (node (ref "IC11") (pin "4") (pinfunction "V-_4") (pintype "power_in"))
      (node (ref "IC12") (pin "4") (pinfunction "V-_4") (pintype "power_in"))
      (node (ref "IC14") (pin "4") (pinfunction "V-_4") (pintype "power_in"))
      (node (ref "R181") (pin "2") (pinfunction "2_2") (pintype "passive"))
      (node (ref "R182") (pin "2") (pinfunction "2_2") (pintype "passive"))
      (node (ref "R183") (pin "2") (pinfunction "2_2") (pintype "passive"))
      (node (ref "R184") (pin "2") (pinfunction "2_2") (pintype "passive"))
      (node (ref "R185") (pin "2") (pinfunction "2_2") (pintype "passive"))
      (node (ref "R186") (pin "2") (pinfunction "2_2") (pintype "passive"))
      (node (ref "R211") (pin "1") (pinfunction "1_1") (pintype "passive"))
      (node (ref "R213") (pin "2") (pinfunction "2_2") (pintype "passive"))
      (node (ref "R221") (pin "1") (pinfunction "1_1") (pintype "passive"))
      (node (ref "R223") (pin "2") (pinfunction "2_2") (pintype "passive"))
      (node (ref "R231") (pin "1") (pinfunction "1_1") (pintype "passive"))
      (node (ref "R233") (pin "2") (pinfunction "2_2") (pintype "passive"))
      (node (ref "R241") (pin "1") (pinfunction "1_1") (pintype "passive"))
      (node (ref "R243") (pin "2") (pinfunction "2_2") (pintype "passive"))
      (node (ref "R25") (pin "2") (pinfunction "2_2") (pintype "passive"))
      (node (ref "R251") (pin "1") (pinfunction "1_1") (pintype "passive"))
      (node (ref "R253") (pin "2") (pinfunction "2_2") (pintype "passive"))
      (node (ref "R261") (pin "1") (pinfunction "1_1") (pintype "passive"))
      (node (ref "R263") (pin "2") (pinfunction "2_2") (pintype "passive"))
      (node (ref "U1") (pin "Y9") (pinfunction "AGND_ADC_Y9") (pintype "bidirectional"))
      (node (ref "X10") (pin "2") (pinfunction "SK_2") (pintype "passive"))
      (node (ref "X10") (pin "4") (pinfunction "SK_4") (pintype "passive"))
      (node (ref "X11") (pin "2") (pinfunction "SK_2") (pintype "passive"))
      (node (ref "X11") (pin "4") (pinfunction "SK_4") (pintype "passive"))
      (node (ref "X12") (pin "2") (pinfunction "SK_2") (pintype "passive"))
      (node (ref "X12") (pin "4") (pinfunction "SK_4") (pintype "passive"))
    )
    (net (code "162") (name "CGND") (class "Default")
      (node (ref "MGT1") (pin "P$1") (pinfunction "P$1_P$1") (pintype "bidirectional"))
      (node (ref "MGT2") (pin "P$1") (pinfunction "P$1_P$1") (pintype "bidirectional"))
      (node (ref "MGT3") (pin "P$1") (pinfunction "P$1_P$1") (pintype "bidirectional"))
      (node (ref "MGT4") (pin "P$1") (pinfunction "P$1_P$1") (pintype "bidirectional"))
      (node (ref "R34") (pin "2") (pinfunction "2_2") (pintype "passive"))
      (node (ref "X1") (pin "CGND1") (pinfunction "SGND1_CGND1") (pintype "bidirectional"))
      (node (ref "X1") (pin "CGND2") (pinfunction "SGND2_CGND2") (pintype "bidirectional"))
      (node (ref "X1") (pin "CGND3") (pinfunction "SGND3_CGND3") (pintype "bidirectional"))
      (node (ref "X1") (pin "CGND4") (pinfunction "SGND4_CGND4") (pintype "bidirectional"))
      (node (ref "X1") (pin "CGND5") (pinfunction "SGND5_CGND5") (pintype "bidirectional"))
      (node (ref "X1") (pin "CGND6") (pinfunction "SGND6_CGND6") (pintype "bidirectional"))
      (node (ref "X2") (pin "S1") (pinfunction "SHD1_S1") (pintype "passive"))
      (node (ref "X2") (pin "S2") (pinfunction "SHD2_S2") (pintype "passive"))
      (node (ref "X5") (pin "10") (pinfunction "GND_2_10") (pintype "bidirectional"))
      (node (ref "X5") (pin "11") (pinfunction "GND_3_11") (pintype "bidirectional"))
      (node (ref "X5") (pin "13") (pinfunction "GND_4_13") (pintype "bidirectional"))
      (node (ref "X5") (pin "9") (pinfunction "GND_1_9") (pintype "bidirectional"))
    )
    (net (code "163") (name "GND") (class "Default")
      (node (ref "C1") (pin "1") (pinfunction "1_1") (pintype "passive"))
      (node (ref "C100") (pin "2") (pinfunction "2_2") (pintype "passive"))
      (node (ref "C101") (pin "2") (pinfunction "2_2") (pintype "passive"))
      (node (ref "C102") (pin "2") (pinfunction "2_2") (pintype "passive"))
      (node (ref "C104") (pin "2") (pinfunction "2_2") (pintype "passive"))
      (node (ref "C105") (pin "2") (pinfunction "2_2") (pintype "passive"))
      (node (ref "C106") (pin "2") (pinfunction "2_2") (pintype "passive"))
      (node (ref "C11") (pin "-") (pinfunction "-_-") (pintype "passive"))
      (node (ref "C14") (pin "2") (pinfunction "2_2") (pintype "passive"))
      (node (ref "C15") (pin "2") (pinfunction "2_2") (pintype "passive"))
      (node (ref "C2") (pin "1") (pinfunction "1_1") (pintype "passive"))
      (node (ref "C21") (pin "2") (pinfunction "2_2") (pintype "passive"))
      (node (ref "C22") (pin "2") (pinfunction "2_2") (pintype "passive"))
      (node (ref "C3") (pin "2") (pinfunction "2_2") (pintype "passive"))
      (node (ref "C301") (pin "2") (pinfunction "2_2") (pintype "passive"))
      (node (ref "C4") (pin "2") (pinfunction "2_2") (pintype "passive"))
      (node (ref "C401") (pin "2") (pinfunction "2_2") (pintype "passive"))
      (node (ref "C404") (pin "2") (pinfunction "2_2") (pintype "passive"))
      (node (ref "C6") (pin "1") (pinfunction "1_1") (pintype "passive"))
      (node (ref "C79") (pin "2") (pinfunction "2_2") (pintype "passive"))
      (node (ref "C801") (pin "2") (pinfunction "2_2") (pintype "passive"))
      (node (ref "C85") (pin "2") (pinfunction "2_2") (pintype "passive"))
      (node (ref "C87") (pin "2") (pinfunction "2_2") (pintype "passive"))
      (node (ref "C88") (pin "2") (pinfunction "2_2") (pintype "passive"))
      (node (ref "D18") (pin "A") (pinfunction "A_A") (pintype "passive"))
      (node (ref "D305") (pin "3") (pinfunction "3_3") (pintype "passive"))
      (node (ref "D805") (pin "3") (pinfunction "3_3") (pintype "passive"))
      (node (ref "EC30") (pin "2") (pinfunction "2_2") (pintype "passive"))
      (node (ref "EC31") (pin "2") (pinfunction "2_2") (pintype "passive"))
      (node (ref "EC32") (pin "2") (pinfunction "2_2") (pintype "passive"))
      (node (ref "EC33") (pin "2") (pinfunction "2_2") (pintype "passive"))
      (node (ref "EC34") (pin "2") (pinfunction "2_2") (pintype "passive"))
      (node (ref "EC35") (pin "2") (pinfunction "2_2") (pintype "passive"))
      (node (ref "EC36") (pin "2") (pinfunction "2_2") (pintype "passive"))
      (node (ref "EC37") (pin "2") (pinfunction "2_2") (pintype "passive"))
      (node (ref "EC38") (pin "2") (pinfunction "2_2") (pintype "passive"))
      (node (ref "EC39") (pin "2") (pinfunction "2_2") (pintype "passive"))
      (node (ref "EC40") (pin "2") (pinfunction "2_2") (pintype "passive"))
      (node (ref "EC41") (pin "2") (pinfunction "2_2") (pintype "passive"))
      (node (ref "EC42") (pin "2") (pinfunction "2_2") (pintype "passive"))
      (node (ref "ER101") (pin "2") (pinfunction "2_2") (pintype "passive"))
      (node (ref "ER102") (pin "2") (pinfunction "2_2") (pintype "passive"))
      (node (ref "ER103") (pin "2") (pinfunction "2_2") (pintype "passive"))
      (node (ref "ER104") (pin "2") (pinfunction "2_2") (pintype "passive"))
      (node (ref "ER115") (pin "1") (pinfunction "1_1") (pintype "passive"))
      (node (ref "ER117") (pin "1") (pinfunction "1_1") (pintype "passive"))
      (node (ref "ER120") (pin "1") (pinfunction "1_1") (pintype "passive"))
      (node (ref "ER128") (pin "1") (pinfunction "1_1") (pintype "passive"))
      (node (ref "ER129") (pin "2") (pinfunction "2_2") (pintype "passive"))
      (node (ref "G1") (pin "-") (pinfunction "-_-") (pintype "passive"))
      (node (ref "IC2") (pin "8") (pinfunction "GND_8") (pintype "power_in"))
      (node (ref "IC4") (pin "15") (pinfunction "INH_15") (pintype "input"))
      (node (ref "IC5") (pin "10") (pinfunction "SER_10") (pintype "input"))
      (node (ref "IC5") (pin "15") (pinfunction "INH_15") (pintype "input"))
      (node (ref "IC5") (pin "3") (pinfunction "E_3") (pintype "input"))
      (node (ref "IC5") (pin "4") (pinfunction "F_4") (pintype "input"))
      (node (ref "IC5") (pin "5") (pinfunction "G_5") (pintype "input"))
      (node (ref "IC5") (pin "6") (pinfunction "H_6") (pintype "input"))
      (node (ref "J1") (pin "2") (pinfunction "2_2") (pintype "bidirectional"))
      (node (ref "J2") (pin "2") (pinfunction "2_2") (pintype "bidirectional"))
      (node (ref "J3") (pin "2") (pinfunction "2_2") (pintype "bidirectional"))
      (node (ref "J4") (pin "2") (pinfunction "2_2") (pintype "bidirectional"))
      (node (ref "J5") (pin "2") (pinfunction "2_2") (pintype "bidirectional"))
      (node (ref "J6") (pin "2") (pinfunction "2_2") (pintype "bidirectional"))
      (node (ref "R168") (pin "2") (pinfunction "2_2") (pintype "passive"))
      (node (ref "R18") (pin "1") (pinfunction "1_1") (pintype "passive"))
      (node (ref "R26") (pin "2") (pinfunction "2_2") (pintype "passive"))
      (node (ref "R27") (pin "1") (pinfunction "1_1") (pintype "passive"))
      (node (ref "R281") (pin "1") (pinfunction "1_1") (pintype "bidirectional"))
      (node (ref "R281") (pin "2") (pinfunction "2_2") (pintype "bidirectional"))
      (node (ref "R281") (pin "3") (pinfunction "3_3") (pintype "bidirectional"))
      (node (ref "R281") (pin "4") (pinfunction "4_4") (pintype "bidirectional"))
      (node (ref "R282") (pin "1") (pinfunction "1_1") (pintype "bidirectional"))
      (node (ref "R282") (pin "2") (pinfunction "2_2") (pintype "bidirectional"))
      (node (ref "R282") (pin "3") (pinfunction "3_3") (pintype "bidirectional"))
      (node (ref "R282") (pin "4") (pinfunction "4_4") (pintype "bidirectional"))
      (node (ref "R291") (pin "1") (pinfunction "1_1") (pintype "bidirectional"))
      (node (ref "R291") (pin "2") (pinfunction "2_2") (pintype "bidirectional"))
      (node (ref "R291") (pin "3") (pinfunction "3_3") (pintype "bidirectional"))
      (node (ref "R291") (pin "4") (pinfunction "4_4") (pintype "bidirectional"))
      (node (ref "R301") (pin "2") (pinfunction "2_2") (pintype "passive"))
      (node (ref "R302") (pin "2") (pinfunction "2_2") (pintype "passive"))
      (node (ref "R304") (pin "1") (pinfunction "1_1") (pintype "passive"))
      (node (ref "R34") (pin "1") (pinfunction "1_1") (pintype "passive"))
      (node (ref "R35") (pin "1") (pinfunction "1_1") (pintype "bidirectional"))
      (node (ref "R35") (pin "2") (pinfunction "2_2") (pintype "bidirectional"))
      (node (ref "R35") (pin "3") (pinfunction "3_3") (pintype "bidirectional"))
      (node (ref "R35") (pin "4") (pinfunction "4_4") (pintype "bidirectional"))
      (node (ref "R39") (pin "1") (pinfunction "1_1") (pintype "passive"))
      (node (ref "R401") (pin "2") (pinfunction "2_2") (pintype "passive"))
      (node (ref "R402") (pin "2") (pinfunction "2_2") (pintype "passive"))
      (node (ref "R53") (pin "1") (pinfunction "1_1") (pintype "passive"))
      (node (ref "R54") (pin "1") (pinfunction "1_1") (pintype "passive"))
      (node (ref "R55") (pin "1") (pinfunction "1_1") (pintype "passive"))
      (node (ref "R56") (pin "1") (pinfunction "1_1") (pintype "passive"))
      (node (ref "R57") (pin "1") (pinfunction "1_1") (pintype "passive"))
      (node (ref "R58") (pin "1") (pinfunction "1_1") (pintype "passive"))
      (node (ref "R59") (pin "1") (pinfunction "1_1") (pintype "passive"))
      (node (ref "R6") (pin "1") (pinfunction "1_1") (pintype "passive"))
      (node (ref "R60") (pin "1") (pinfunction "1_1") (pintype "passive"))
      (node (ref "R61") (pin "1") (pinfunction "1_1") (pintype "passive"))
      (node (ref "R62") (pin "1") (pinfunction "1_1") (pintype "passive"))
      (node (ref "R63") (pin "1") (pinfunction "1_1") (pintype "passive"))
      (node (ref "R64") (pin "1") (pinfunction "1_1") (pintype "passive"))
      (node (ref "R65") (pin "1") (pinfunction "1_1") (pintype "passive"))
      (node (ref "R66") (pin "1") (pinfunction "1_1") (pintype "passive"))
      (node (ref "R67") (pin "1") (pinfunction "1_1") (pintype "passive"))
      (node (ref "R68") (pin "1") (pinfunction "1_1") (pintype "passive"))
      (node (ref "R801") (pin "2") (pinfunction "2_2") (pintype "passive"))
      (node (ref "R802") (pin "2") (pinfunction "2_2") (pintype "passive"))
      (node (ref "RTC1") (pin "5") (pinfunction "GND_5") (pintype "power_in"))
      (node (ref "S1") (pin "2") (pinfunction "2_2") (pintype "bidirectional"))
      (node (ref "S1") (pin "4") (pinfunction "4_4") (pintype "bidirectional"))
      (node (ref "S2") (pin "1") (pinfunction "1_1") (pintype "bidirectional"))
      (node (ref "S2") (pin "3") (pinfunction "3_3") (pintype "bidirectional"))
      (node (ref "TP8") (pin "P$1") (pinfunction "TP_P$1") (pintype "bidirectional"))
      (node (ref "U1") (pin "A1") (pinfunction "DGND_A1") (pintype "bidirectional"))
      (node (ref "U1") (pin "A20") (pinfunction "DGND_A20") (pintype "bidirectional"))
      (node (ref "U1") (pin "D15") (pinfunction "DGND_D15") (pintype "bidirectional"))
      (node (ref "U1") (pin "D16") (pinfunction "DGND_D16") (pintype "bidirectional"))
      (node (ref "U1") (pin "D17") (pinfunction "DGND_D17") (pintype "bidirectional"))
      (node (ref "U1") (pin "D4") (pinfunction "DGND_D4") (pintype "bidirectional"))
      (node (ref "U1") (pin "D5") (pinfunction "DGND_D5") (pintype "bidirectional"))
      (node (ref "U1") (pin "E10") (pinfunction "DGND_E10") (pintype "bidirectional"))
      (node (ref "U1") (pin "E11") (pinfunction "DGND_E11") (pintype "bidirectional"))
      (node (ref "U1") (pin "E12") (pinfunction "DGND_E12") (pintype "bidirectional"))
      (node (ref "U1") (pin "E13") (pinfunction "DGND_E13") (pintype "bidirectional"))
      (node (ref "U1") (pin "E14") (pinfunction "DGND_E14") (pintype "bidirectional"))
      (node (ref "U1") (pin "E15") (pinfunction "DGND_E15") (pintype "bidirectional"))
      (node (ref "U1") (pin "E16") (pinfunction "DGND_E16") (pintype "bidirectional"))
      (node (ref "U1") (pin "E17") (pinfunction "DGND_E17") (pintype "bidirectional"))
      (node (ref "U1") (pin "E4") (pinfunction "DGND_E4") (pintype "bidirectional"))
      (node (ref "U1") (pin "E5") (pinfunction "DGND_E5") (pintype "bidirectional"))
      (node (ref "U1") (pin "E6") (pinfunction "DGND_E6") (pintype "bidirectional"))
      (node (ref "U1") (pin "E7") (pinfunction "DGND_E7") (pintype "bidirectional"))
      (node (ref "U1") (pin "E8") (pinfunction "DGND_E8") (pintype "bidirectional"))
      (node (ref "U1") (pin "E9") (pinfunction "DGND_E9") (pintype "bidirectional"))
      (node (ref "U1") (pin "F10") (pinfunction "DGND_F10") (pintype "bidirectional"))
      (node (ref "U1") (pin "F11") (pinfunction "DGND_F11") (pintype "bidirectional"))
      (node (ref "U1") (pin "F16") (pinfunction "DGND_F16") (pintype "bidirectional"))
      (node (ref "U1") (pin "F17") (pinfunction "DGND_F17") (pintype "bidirectional"))
      (node (ref "U1") (pin "F5") (pinfunction "DGND_F5") (pintype "bidirectional"))
      (node (ref "U1") (pin "G16") (pinfunction "DGND_G16") (pintype "bidirectional"))
      (node (ref "U1") (pin "G5") (pinfunction "DGND_G5") (pintype "bidirectional"))
      (node (ref "U1") (pin "H16") (pinfunction "DGND_H16") (pintype "bidirectional"))
      (node (ref "U1") (pin "H5") (pinfunction "DGND_H5") (pintype "bidirectional"))
      (node (ref "U1") (pin "J10") (pinfunction "DGND_J10") (pintype "bidirectional"))
      (node (ref "U1") (pin "J11") (pinfunction "DGND_J11") (pintype "bidirectional"))
      (node (ref "U1") (pin "J12") (pinfunction "DGND_J12") (pintype "bidirectional"))
      (node (ref "U1") (pin "J13") (pinfunction "DGND_J13") (pintype "bidirectional"))
      (node (ref "U1") (pin "J16") (pinfunction "DGND_J16") (pintype "bidirectional"))
      (node (ref "U1") (pin "J5") (pinfunction "DGND_J5") (pintype "bidirectional"))
      (node (ref "U1") (pin "J9") (pinfunction "DGND_J9") (pintype "bidirectional"))
      (node (ref "U1") (pin "K12") (pinfunction "DGND_K12") (pintype "bidirectional"))
      (node (ref "U1") (pin "K15") (pinfunction "DGND_K15") (pintype "bidirectional"))
      (node (ref "U1") (pin "K16") (pinfunction "DGND_K16") (pintype "bidirectional"))
      (node (ref "U1") (pin "K5") (pinfunction "DGND_K5") (pintype "bidirectional"))
      (node (ref "U1") (pin "K6") (pinfunction "DGND_K6") (pintype "bidirectional"))
      (node (ref "U1") (pin "K7") (pinfunction "DGND_K7") (pintype "bidirectional"))
      (node (ref "U1") (pin "K8") (pinfunction "DGND_K8") (pintype "bidirectional"))
      (node (ref "U1") (pin "K9") (pinfunction "DGND_K9") (pintype "bidirectional"))
      (node (ref "U1") (pin "L15") (pinfunction "DGND_L15") (pintype "bidirectional"))
      (node (ref "U1") (pin "L16") (pinfunction "DGND_L16") (pintype "bidirectional"))
      (node (ref "U1") (pin "L5") (pinfunction "DGND_L5") (pintype "bidirectional"))
      (node (ref "U1") (pin "L6") (pinfunction "DGND_L6") (pintype "bidirectional"))
      (node (ref "U1") (pin "M15") (pinfunction "DGND_M15") (pintype "bidirectional"))
      (node (ref "U1") (pin "M16") (pinfunction "DGND_M16") (pintype "bidirectional"))
      (node (ref "U1") (pin "M5") (pinfunction "DGND_M5") (pintype "bidirectional"))
      (node (ref "U1") (pin "N15") (pinfunction "DGND_N15") (pintype "bidirectional"))
      (node (ref "U1") (pin "N16") (pinfunction "DGND_N16") (pintype "bidirectional"))
      (node (ref "U1") (pin "N5") (pinfunction "DGND_N5") (pintype "bidirectional"))
      (node (ref "U1") (pin "N6") (pinfunction "DGND_N6") (pintype "bidirectional"))
      (node (ref "U1") (pin "P12") (pinfunction "DGND_P12") (pintype "bidirectional"))
      (node (ref "U1") (pin "P13") (pinfunction "DGND_P13") (pintype "bidirectional"))
      (node (ref "U1") (pin "P14") (pinfunction "DGND_P14") (pintype "bidirectional"))
      (node (ref "U1") (pin "P15") (pinfunction "DGND_P15") (pintype "bidirectional"))
      (node (ref "U1") (pin "P16") (pinfunction "DGND_P16") (pintype "bidirectional"))
      (node (ref "U1") (pin "P5") (pinfunction "DGND_P5") (pintype "bidirectional"))
      (node (ref "U1") (pin "P6") (pinfunction "DGND_P6") (pintype "bidirectional"))
      (node (ref "U1") (pin "P7") (pinfunction "DGND_P7") (pintype "bidirectional"))
      (node (ref "U1") (pin "P8") (pinfunction "DGND_P8") (pintype "bidirectional"))
      (node (ref "U1") (pin "P9") (pinfunction "DGND_P9") (pintype "bidirectional"))
      (node (ref "U1") (pin "R10") (pinfunction "DGND_R10") (pintype "bidirectional"))
      (node (ref "U1") (pin "R11") (pinfunction "DGND_R11") (pintype "bidirectional"))
      (node (ref "U1") (pin "R12") (pinfunction "DGND_R12") (pintype "bidirectional"))
      (node (ref "U1") (pin "R16") (pinfunction "DGND_R16") (pintype "bidirectional"))
      (node (ref "U1") (pin "R5") (pinfunction "DGND_R5") (pintype "bidirectional"))
      (node (ref "U1") (pin "R9") (pinfunction "DGND_R9") (pintype "bidirectional"))
      (node (ref "U1") (pin "T10") (pinfunction "DGND_T10") (pintype "bidirectional"))
      (node (ref "U1") (pin "T11") (pinfunction "DGND_T11") (pintype "bidirectional"))
      (node (ref "U1") (pin "T12") (pinfunction "DGND_T12") (pintype "bidirectional"))
      (node (ref "U1") (pin "T13") (pinfunction "DGND_T13") (pintype "bidirectional"))
      (node (ref "U1") (pin "T14") (pinfunction "DGND_T14") (pintype "bidirectional"))
      (node (ref "U1") (pin "T15") (pinfunction "DGND_T15") (pintype "bidirectional"))
      (node (ref "U1") (pin "T16") (pinfunction "DGND_T16") (pintype "bidirectional"))
      (node (ref "U1") (pin "T17") (pinfunction "DGND_T17") (pintype "bidirectional"))
      (node (ref "U1") (pin "T4") (pinfunction "DGND_T4") (pintype "bidirectional"))
      (node (ref "U1") (pin "T5") (pinfunction "DGND_T5") (pintype "bidirectional"))
      (node (ref "U1") (pin "T6") (pinfunction "DGND_T6") (pintype "bidirectional"))
      (node (ref "U1") (pin "T7") (pinfunction "DGND_T7") (pintype "bidirectional"))
      (node (ref "U1") (pin "T8") (pinfunction "DGND_T8") (pintype "bidirectional"))
      (node (ref "U1") (pin "T9") (pinfunction "DGND_T9") (pintype "bidirectional"))
      (node (ref "U1") (pin "U15") (pinfunction "RTC_KALDO_ENN_U15") (pintype "bidirectional"))
      (node (ref "U1") (pin "U16") (pinfunction "DGND_U16") (pintype "bidirectional"))
      (node (ref "U1") (pin "U17") (pinfunction "DGND_U17") (pintype "bidirectional"))
      (node (ref "U1") (pin "U4") (pinfunction "DGND_U4") (pintype "bidirectional"))
      (node (ref "U1") (pin "U5") (pinfunction "DGND_U5") (pintype "bidirectional"))
      (node (ref "U1") (pin "W13") (pinfunction "OSC1_GND_W13") (pintype "bidirectional"))
      (node (ref "U1") (pin "Y1") (pinfunction "DGND_Y1") (pintype "bidirectional"))
      (node (ref "U1") (pin "Y20") (pinfunction "DGND_Y20") (pintype "bidirectional"))
      (node (ref "U16") (pin "18") (pinfunction "PIRQ#_18") (pintype "bidirectional"))
      (node (ref "U16") (pin "19") (pinfunction "ATEST_19") (pintype "bidirectional"))
      (node (ref "U16") (pin "2") (pinfunction "GND_2") (pintype "bidirectional"))
      (node (ref "U16") (pin "20") (pinfunction "TWI_WAKEUP#_20") (pintype "bidirectional"))
      (node (ref "U16") (pin "21") (pinfunction "ATEST_21") (pintype "bidirectional"))
      (node (ref "U16") (pin "23") (pinfunction "GND_23") (pintype "bidirectional"))
      (node (ref "U16") (pin "24") (pinfunction "ATEST_24") (pintype "bidirectional"))
      (node (ref "U16") (pin "32") (pinfunction "GND_32") (pintype "bidirectional"))
      (node (ref "U16") (pin "5") (pinfunction "TESTL_5") (pintype "bidirectional"))
      (node (ref "U16") (pin "6") (pinfunction "XTAMPER_6") (pintype "bidirectional"))
      (node (ref "U16") (pin "9") (pinfunction "GND_9") (pintype "bidirectional"))
      (node (ref "U2") (pin "4") (pinfunction "GND_4") (pintype "power_in"))
      (node (ref "U27") (pin "33") (pinfunction "GND_EP_33") (pintype "power_in"))
      (node (ref "U28") (pin "2") (pinfunction "GND_2") (pintype "power_in"))
      (node (ref "U29") (pin "5") (pinfunction "GND_5") (pintype "power_in"))
      (node (ref "U4") (pin "1") (pinfunction "GND_1") (pintype "bidirectional"))
      (node (ref "U40") (pin "3") (pinfunction "GND1_3") (pintype "power_in"))
      (node (ref "U6") (pin "1") (pinfunction "*1OE_1") (pintype "input"))
      (node (ref "U6") (pin "4") (pinfunction "GND_4") (pintype "power_in"))
      (node (ref "VREG1") (pin "3") (pinfunction "GND_3") (pintype "power_in"))
      (node (ref "VREG1") (pin "5") (pinfunction "EN_5") (pintype "input"))
      (node (ref "VREG1") (pin "6") (pinfunction "GND_6") (pintype "power_in"))
      (node (ref "VREG2") (pin "GND") (pinfunction "GND_GND") (pintype "input"))
      (node (ref "X1") (pin "GND") (pinfunction "GND_GND") (pintype "input"))
      (node (ref "X2") (pin "8") (pinfunction "D_GND_8") (pintype "passive"))
      (node (ref "X24") (pin "2") (pinfunction "1_2") (pintype "passive"))
      (node (ref "X3") (pin "1") (pinfunction "SK_1") (pintype "passive"))
      (node (ref "X4") (pin "10") (pinfunction "GND2_10") (pintype "bidirectional"))
      (node (ref "X4") (pin "12") (pinfunction "GND3_12") (pintype "bidirectional"))
      (node (ref "X4") (pin "16") (pinfunction "GND4_16") (pintype "bidirectional"))
      (node (ref "X4") (pin "20") (pinfunction "GND5_20") (pintype "bidirectional"))
      (node (ref "X4") (pin "4") (pinfunction "TDIS_4") (pintype "bidirectional"))
      (node (ref "X4") (pin "8") (pinfunction "GND1_8") (pintype "bidirectional"))
      (node (ref "X5") (pin "6") (pinfunction "VSS_6") (pintype "bidirectional"))
      (node (ref "X6") (pin "1") (pinfunction "1_1") (pintype "bidirectional"))
      (node (ref "X8") (pin "3") (pinfunction "SK_3") (pintype "passive"))
    )
    (net (code "164") (name "ISO_GND") (class "Default")
      (node (ref "C402") (pin "2") (pinfunction "2_2") (pintype "passive"))
      (node (ref "C403") (pin "2") (pinfunction "2_2") (pintype "passive"))
      (node (ref "C405") (pin "2") (pinfunction "2_2") (pintype "passive"))
      (node (ref "C406") (pin "-") (pinfunction "-_-") (pintype "passive"))
      (node (ref "D405") (pin "3") (pinfunction "3_3") (pintype "passive"))
      (node (ref "GDT1") (pin "3") (pinfunction "3_3") (pintype "passive"))
      (node (ref "T4") (pin "P$6") (pinfunction "6_P$6") (pintype "passive"))
      (node (ref "T4") (pin "P$7") (pinfunction "7_P$7") (pintype "passive"))
      (node (ref "U40") (pin "15") (pinfunction "GND2_15") (pintype "power_in"))
      (node (ref "U40") (pin "9") (pinfunction "GND2_2_9") (pintype "power_in"))
      (node (ref "VREG4") (pin "2") (pinfunction "GND_2") (pintype "power_in"))
      (node (ref "X41") (pin "3") (pinfunction "1_3") (pintype "passive"))
    )
    (net (code "165") (name "Net-(C105-Pad1)") (class "Default")
      (node (ref "C105") (pin "1") (pinfunction "1_1") (pintype "passive"))
      (node (ref "J24") (pin "1") (pinfunction "1_1") (pintype "bidirectional"))
      (node (ref "VREG2") (pin "IN") (pinfunction "IN_IN") (pintype "input"))
    )
    (net (code "166") (name "Net-(D1-C)") (class "Default")
      (node (ref "D1") (pin "2") (pinfunction "C_2") (pintype "passive"))
      (node (ref "R26") (pin "1") (pinfunction "1_1") (pintype "passive"))
    )
    (net (code "167") (name "Net-(D4-C)") (class "Default")
      (node (ref "D4") (pin "2") (pinfunction "C_2") (pintype "passive"))
      (node (ref "R35") (pin "5") (pinfunction "5_5") (pintype "bidirectional"))
    )
    (net (code "168") (name "Net-(D5-C)") (class "Default")
      (node (ref "D5") (pin "2") (pinfunction "C_2") (pintype "passive"))
      (node (ref "R35") (pin "6") (pinfunction "6_6") (pintype "bidirectional"))
    )
    (net (code "169") (name "Net-(D6-C)") (class "Default")
      (node (ref "D6") (pin "2") (pinfunction "C_2") (pintype "passive"))
      (node (ref "R35") (pin "7") (pinfunction "7_7") (pintype "bidirectional"))
    )
    (net (code "170") (name "Net-(D7-C)") (class "Default")
      (node (ref "D7") (pin "2") (pinfunction "C_2") (pintype "passive"))
      (node (ref "R35") (pin "8") (pinfunction "8_8") (pintype "bidirectional"))
    )
    (net (code "171") (name "Net-(D19-C)") (class "Default")
      (node (ref "D19") (pin "2") (pinfunction "C_2") (pintype "passive"))
      (node (ref "R168") (pin "1") (pinfunction "1_1") (pintype "passive"))
    )
    (net (code "172") (name "Net-(D31-C)") (class "Default")
      (node (ref "D31") (pin "2") (pinfunction "C_2") (pintype "passive"))
      (node (ref "R171") (pin "1") (pinfunction "1_1") (pintype "passive"))
    )
    (net (code "173") (name "Net-(D32-C)") (class "Default")
      (node (ref "D32") (pin "2") (pinfunction "C_2") (pintype "passive"))
      (node (ref "R172") (pin "1") (pinfunction "1_1") (pintype "passive"))
    )
    (net (code "174") (name "Net-(D33-C)") (class "Default")
      (node (ref "D33") (pin "2") (pinfunction "C_2") (pintype "passive"))
      (node (ref "R173") (pin "1") (pinfunction "1_1") (pintype "passive"))
    )
    (net (code "175") (name "Net-(D34-C)") (class "Default")
      (node (ref "D34") (pin "2") (pinfunction "C_2") (pintype "passive"))
      (node (ref "R174") (pin "1") (pinfunction "1_1") (pintype "passive"))
    )
    (net (code "176") (name "Net-(D35-C)") (class "Default")
      (node (ref "D35") (pin "2") (pinfunction "C_2") (pintype "passive"))
      (node (ref "R175") (pin "1") (pinfunction "1_1") (pintype "passive"))
    )
    (net (code "177") (name "Net-(D301-C)") (class "Default")
      (node (ref "D301") (pin "2") (pinfunction "C_2") (pintype "passive"))
      (node (ref "R301") (pin "1") (pinfunction "1_1") (pintype "passive"))
    )
    (net (code "178") (name "Net-(D302-C)") (class "Default")
      (node (ref "D302") (pin "2") (pinfunction "C_2") (pintype "passive"))
      (node (ref "R302") (pin "1") (pinfunction "1_1") (pintype "passive"))
    )
    (net (code "179") (name "Net-(D401-C)") (class "Default")
      (node (ref "D401") (pin "2") (pinfunction "C_2") (pintype "passive"))
      (node (ref "R401") (pin "1") (pinfunction "1_1") (pintype "passive"))
    )
    (net (code "180") (name "Net-(D402-C)") (class "Default")
      (node (ref "D402") (pin "2") (pinfunction "C_2") (pintype "passive"))
      (node (ref "R402") (pin "1") (pinfunction "1_1") (pintype "passive"))
    )
    (net (code "181") (name "Net-(D801-C)") (class "Default")
      (node (ref "D801") (pin "2") (pinfunction "C_2") (pintype "passive"))
      (node (ref "R801") (pin "1") (pinfunction "1_1") (pintype "passive"))
    )
    (net (code "182") (name "Net-(D802-C)") (class "Default")
      (node (ref "D802") (pin "2") (pinfunction "C_2") (pintype "passive"))
      (node (ref "R802") (pin "1") (pinfunction "1_1") (pintype "passive"))
    )
    (net (code "183") (name "Net-(F1-1)") (class "Default")
      (node (ref "F1") (pin "P$1") (pinfunction "1_P$1") (pintype "bidirectional"))
      (node (ref "X24") (pin "1") (pinfunction "1_1") (pintype "passive"))
      (node (ref "X3") (pin "4") (pinfunction "SK_4") (pintype "passive"))
    )
    (net (code "184") (name "Net-(F1-2)") (class "Default")
      (node (ref "D3") (pin "A") (pinfunction "A_A") (pintype "passive"))
      (node (ref "F1") (pin "P$2") (pinfunction "2_P$2") (pintype "bidirectional"))
    )
    (net (code "185") (name "Net-(F401-Pad1)") (class "Default")
      (node (ref "F401") (pin "1") (pinfunction "1_1") (pintype "passive"))
      (node (ref "GDT1") (pin "2") (pinfunction "2_2") (pintype "passive"))
      (node (ref "X41") (pin "1") (pinfunction "1_1") (pintype "passive"))
    )
    (net (code "186") (name "Net-(IC2-O1)") (class "Default")
      (node (ref "IC2") (pin "16") (pinfunction "O1_16") (pintype "open_collector"))
      (node (ref "K1") (pin "2") (pinfunction "2_2") (pintype "passive"))
      (node (ref "R171") (pin "2") (pinfunction "2_2") (pintype "passive"))
    )
    (net (code "187") (name "Net-(IC2-O2)") (class "Default")
      (node (ref "IC2") (pin "15") (pinfunction "O2_15") (pintype "open_collector"))
      (node (ref "K2") (pin "2") (pinfunction "2_2") (pintype "passive"))
      (node (ref "R172") (pin "2") (pinfunction "2_2") (pintype "passive"))
    )
    (net (code "188") (name "Net-(IC2-O3)") (class "Default")
      (node (ref "IC2") (pin "14") (pinfunction "O3_14") (pintype "open_collector"))
      (node (ref "K3") (pin "2") (pinfunction "2_2") (pintype "passive"))
      (node (ref "R173") (pin "2") (pinfunction "2_2") (pintype "passive"))
    )
    (net (code "189") (name "Net-(IC2-O4)") (class "Default")
      (node (ref "IC2") (pin "13") (pinfunction "O4_13") (pintype "open_collector"))
      (node (ref "K4") (pin "2") (pinfunction "2_2") (pintype "passive"))
      (node (ref "R174") (pin "2") (pinfunction "2_2") (pintype "passive"))
    )
    (net (code "190") (name "Net-(IC2-O5)") (class "Default")
      (node (ref "IC2") (pin "12") (pinfunction "O5_12") (pintype "open_collector"))
      (node (ref "K5") (pin "2") (pinfunction "2_2") (pintype "passive"))
      (node (ref "R175") (pin "2") (pinfunction "2_2") (pintype "passive"))
    )
    (net (code "191") (name "Net-(IC4A-A)") (class "Default")
      (node (ref "IC4") (pin "11") (pinfunction "A_11") (pintype "input"))
      (node (ref "R281") (pin "8") (pinfunction "8_8") (pintype "bidirectional"))
      (node (ref "S11") (pin "1") (pinfunction "1_1") (pintype "passive"))
    )
    (net (code "192") (name "Net-(IC4A-B)") (class "Default")
      (node (ref "IC4") (pin "12") (pinfunction "B_12") (pintype "input"))
      (node (ref "R281") (pin "7") (pinfunction "7_7") (pintype "bidirectional"))
      (node (ref "S11") (pin "2") (pinfunction "2_2") (pintype "passive"))
    )
    (net (code "193") (name "Net-(IC4A-C)") (class "Default")
      (node (ref "IC4") (pin "13") (pinfunction "C_13") (pintype "input"))
      (node (ref "R281") (pin "6") (pinfunction "6_6") (pintype "bidirectional"))
      (node (ref "S11") (pin "4") (pinfunction "4_4") (pintype "passive"))
    )
    (net (code "194") (name "Net-(IC4A-D)") (class "Default")
      (node (ref "IC4") (pin "14") (pinfunction "D_14") (pintype "input"))
      (node (ref "R281") (pin "5") (pinfunction "5_5") (pintype "bidirectional"))
      (node (ref "S11") (pin "8") (pinfunction "8_8") (pintype "passive"))
    )
    (net (code "195") (name "Net-(IC4A-E)") (class "Default")
      (node (ref "IC4") (pin "3") (pinfunction "E_3") (pintype "input"))
      (node (ref "R282") (pin "8") (pinfunction "8_8") (pintype "bidirectional"))
      (node (ref "S12") (pin "1") (pinfunction "1_1") (pintype "passive"))
    )
    (net (code "196") (name "Net-(IC4A-F)") (class "Default")
      (node (ref "IC4") (pin "4") (pinfunction "F_4") (pintype "input"))
      (node (ref "R282") (pin "7") (pinfunction "7_7") (pintype "bidirectional"))
      (node (ref "S12") (pin "2") (pinfunction "2_2") (pintype "passive"))
    )
    (net (code "197") (name "Net-(IC4A-G)") (class "Default")
      (node (ref "IC4") (pin "5") (pinfunction "G_5") (pintype "input"))
      (node (ref "R282") (pin "6") (pinfunction "6_6") (pintype "bidirectional"))
      (node (ref "S12") (pin "4") (pinfunction "4_4") (pintype "passive"))
    )
    (net (code "198") (name "Net-(IC4A-H)") (class "Default")
      (node (ref "IC4") (pin "6") (pinfunction "H_6") (pintype "input"))
      (node (ref "R282") (pin "5") (pinfunction "5_5") (pintype "bidirectional"))
      (node (ref "S12") (pin "8") (pinfunction "8_8") (pintype "passive"))
    )
    (net (code "199") (name "Net-(IC4A-SER)") (class "Default")
      (node (ref "IC4") (pin "10") (pinfunction "SER_10") (pintype "input"))
      (node (ref "IC5") (pin "9") (pinfunction "QH_9") (pintype "output"))
    )
    (net (code "200") (name "Net-(IC5A-A)") (class "Default")
      (node (ref "IC5") (pin "11") (pinfunction "A_11") (pintype "input"))
      (node (ref "R291") (pin "8") (pinfunction "8_8") (pintype "bidirectional"))
      (node (ref "S13") (pin "8") (pinfunction "8_8") (pintype "passive"))
    )
    (net (code "201") (name "Net-(IC5A-B)") (class "Default")
      (node (ref "IC5") (pin "12") (pinfunction "B_12") (pintype "input"))
      (node (ref "R291") (pin "7") (pinfunction "7_7") (pintype "bidirectional"))
      (node (ref "S13") (pin "7") (pinfunction "7_7") (pintype "passive"))
    )
    (net (code "202") (name "Net-(IC5A-C)") (class "Default")
      (node (ref "IC5") (pin "13") (pinfunction "C_13") (pintype "input"))
      (node (ref "R291") (pin "6") (pinfunction "6_6") (pintype "bidirectional"))
      (node (ref "S13") (pin "6") (pinfunction "6_6") (pintype "passive"))
    )
    (net (code "203") (name "Net-(IC5A-D)") (class "Default")
      (node (ref "IC5") (pin "14") (pinfunction "D_14") (pintype "input"))
      (node (ref "R291") (pin "5") (pinfunction "5_5") (pintype "bidirectional"))
      (node (ref "S13") (pin "5") (pinfunction "5_5") (pintype "passive"))
    )
    (net (code "204") (name "Net-(IC10A-+IN)") (class "Default")
      (node (ref "C111") (pin "1") (pinfunction "1_1") (pintype "passive"))
      (node (ref "IC10") (pin "3") (pinfunction "+IN_3") (pintype "input"))
      (node (ref "J13") (pin "1") (pinfunction "1_1") (pintype "bidirectional"))
      (node (ref "R214") (pin "2") (pinfunction "2_2") (pintype "passive"))
    )
    (net (code "205") (name "Net-(IC10B-+IN)") (class "Default")
      (node (ref "C121") (pin "1") (pinfunction "1_1") (pintype "passive"))
      (node (ref "IC10") (pin "5") (pinfunction "+IN_5") (pintype "input"))
      (node (ref "J23") (pin "1") (pinfunction "1_1") (pintype "bidirectional"))
      (node (ref "R224") (pin "2") (pinfunction "2_2") (pintype "passive"))
    )
    (net (code "206") (name "Net-(IC11A-+IN)") (class "Default")
      (node (ref "C131") (pin "1") (pinfunction "1_1") (pintype "passive"))
      (node (ref "IC11") (pin "3") (pinfunction "+IN_3") (pintype "input"))
      (node (ref "J33") (pin "1") (pinfunction "1_1") (pintype "bidirectional"))
      (node (ref "R234") (pin "2") (pinfunction "2_2") (pintype "passive"))
    )
    (net (code "207") (name "Net-(IC11B-+IN)") (class "Default")
      (node (ref "C141") (pin "1") (pinfunction "1_1") (pintype "passive"))
      (node (ref "IC11") (pin "5") (pinfunction "+IN_5") (pintype "input"))
      (node (ref "J43") (pin "1") (pinfunction "1_1") (pintype "bidirectional"))
      (node (ref "R244") (pin "2") (pinfunction "2_2") (pintype "passive"))
    )
    (net (code "208") (name "Net-(IC12A-+IN)") (class "Default")
      (node (ref "C151") (pin "1") (pinfunction "1_1") (pintype "passive"))
      (node (ref "IC12") (pin "3") (pinfunction "+IN_3") (pintype "input"))
      (node (ref "J53") (pin "1") (pinfunction "1_1") (pintype "bidirectional"))
      (node (ref "R254") (pin "2") (pinfunction "2_2") (pintype "passive"))
    )
    (net (code "209") (name "Net-(IC12B-+IN)") (class "Default")
      (node (ref "C161") (pin "1") (pinfunction "1_1") (pintype "passive"))
      (node (ref "IC12") (pin "5") (pinfunction "+IN_5") (pintype "input"))
      (node (ref "J63") (pin "1") (pinfunction "1_1") (pintype "bidirectional"))
      (node (ref "R264") (pin "2") (pinfunction "2_2") (pintype "passive"))
    )
    (net (code "210") (name "Net-(J3-Pad1)") (class "Default")
      (node (ref "J3") (pin "1") (pinfunction "1_1") (pintype "bidirectional"))
      (node (ref "R69") (pin "2") (pinfunction "2_2") (pintype "passive"))
    )
    (net (code "211") (name "Net-(J11-Pad2)") (class "Default")
      (node (ref "J11") (pin "2") (pinfunction "2_2") (pintype "bidirectional"))
      (node (ref "R211") (pin "2") (pinfunction "2_2") (pintype "passive"))
    )
    (net (code "212") (name "Net-(J12-Pad2)") (class "Default")
      (node (ref "J12") (pin "2") (pinfunction "2_2") (pintype "bidirectional"))
      (node (ref "R212") (pin "1") (pinfunction "1_1") (pintype "passive"))
    )
    (net (code "213") (name "Net-(J13-Pad2)") (class "Default")
      (node (ref "J13") (pin "2") (pinfunction "2_2") (pintype "bidirectional"))
      (node (ref "R213") (pin "1") (pinfunction "1_1") (pintype "passive"))
    )
    (net (code "214") (name "Net-(J21-Pad2)") (class "Default")
      (node (ref "J21") (pin "2") (pinfunction "2_2") (pintype "bidirectional"))
      (node (ref "R221") (pin "2") (pinfunction "2_2") (pintype "passive"))
    )
    (net (code "215") (name "Net-(J22-Pad2)") (class "Default")
      (node (ref "J22") (pin "2") (pinfunction "2_2") (pintype "bidirectional"))
      (node (ref "R222") (pin "1") (pinfunction "1_1") (pintype "passive"))
    )
    (net (code "216") (name "Net-(J23-Pad2)") (class "Default")
      (node (ref "J23") (pin "2") (pinfunction "2_2") (pintype "bidirectional"))
      (node (ref "R223") (pin "1") (pinfunction "1_1") (pintype "passive"))
    )
    (net (code "217") (name "Net-(J31-Pad2)") (class "Default")
      (node (ref "J31") (pin "2") (pinfunction "2_2") (pintype "bidirectional"))
      (node (ref "R231") (pin "2") (pinfunction "2_2") (pintype "passive"))
    )
    (net (code "218") (name "Net-(J32-Pad2)") (class "Default")
      (node (ref "J32") (pin "2") (pinfunction "2_2") (pintype "bidirectional"))
      (node (ref "R232") (pin "1") (pinfunction "1_1") (pintype "passive"))
    )
    (net (code "219") (name "Net-(J33-Pad2)") (class "Default")
      (node (ref "J33") (pin "2") (pinfunction "2_2") (pintype "bidirectional"))
      (node (ref "R233") (pin "1") (pinfunction "1_1") (pintype "passive"))
    )
    (net (code "220") (name "Net-(J41-Pad2)") (class "Default")
      (node (ref "J41") (pin "2") (pinfunction "2_2") (pintype "bidirectional"))
      (node (ref "R241") (pin "2") (pinfunction "2_2") (pintype "passive"))
    )
    (net (code "221") (name "Net-(J42-Pad2)") (class "Default")
      (node (ref "J42") (pin "2") (pinfunction "2_2") (pintype "bidirectional"))
      (node (ref "R242") (pin "1") (pinfunction "1_1") (pintype "passive"))
    )
    (net (code "222") (name "Net-(J43-Pad2)") (class "Default")
      (node (ref "J43") (pin "2") (pinfunction "2_2") (pintype "bidirectional"))
      (node (ref "R243") (pin "1") (pinfunction "1_1") (pintype "passive"))
    )
    (net (code "223") (name "Net-(J51-Pad2)") (class "Default")
      (node (ref "J51") (pin "2") (pinfunction "2_2") (pintype "bidirectional"))
      (node (ref "R251") (pin "2") (pinfunction "2_2") (pintype "passive"))
    )
    (net (code "224") (name "Net-(J52-Pad2)") (class "Default")
      (node (ref "J52") (pin "2") (pinfunction "2_2") (pintype "bidirectional"))
      (node (ref "R252") (pin "1") (pinfunction "1_1") (pintype "passive"))
    )
    (net (code "225") (name "Net-(J53-Pad2)") (class "Default")
      (node (ref "J53") (pin "2") (pinfunction "2_2") (pintype "bidirectional"))
      (node (ref "R253") (pin "1") (pinfunction "1_1") (pintype "passive"))
    )
    (net (code "226") (name "Net-(J61-Pad2)") (class "Default")
      (node (ref "J61") (pin "2") (pinfunction "2_2") (pintype "bidirectional"))
      (node (ref "R261") (pin "2") (pinfunction "2_2") (pintype "passive"))
    )
    (net (code "227") (name "Net-(J62-Pad2)") (class "Default")
      (node (ref "J62") (pin "2") (pinfunction "2_2") (pintype "bidirectional"))
      (node (ref "R262") (pin "1") (pinfunction "1_1") (pintype "passive"))
    )
    (net (code "228") (name "Net-(J63-Pad2)") (class "Default")
      (node (ref "J63") (pin "2") (pinfunction "2_2") (pintype "bidirectional"))
      (node (ref "R263") (pin "1") (pinfunction "1_1") (pintype "passive"))
    )
    (net (code "229") (name "Net-(K5B-P)") (class "Default")
      (node (ref "K5") (pin "C") (pinfunction "P_C") (pintype "passive"))
      (node (ref "X21") (pin "1") (pinfunction "SK_1") (pintype "passive"))
    )
    (net (code "230") (name "Net-(K5B-S)") (class "Default")
      (node (ref "K5") (pin "NO") (pinfunction "S_NO") (pintype "passive"))
      (node (ref "X21") (pin "2") (pinfunction "SK_2") (pintype "passive"))
    )
    (net (code "231") (name "Net-(R10-Pad1)") (class "Default")
      (node (ref "R10") (pin "1") (pinfunction "1_1") (pintype "passive"))
      (node (ref "X1") (pin "VBUS") (pinfunction "VBUS_VBUS") (pintype "input"))
    )
    (net (code "232") (name "Net-(R11-Pad1)") (class "Default")
      (node (ref "R11") (pin "1") (pinfunction "1_1") (pintype "passive"))
      (node (ref "S1") (pin "1") (pinfunction "1_1") (pintype "bidirectional"))
      (node (ref "S1") (pin "3") (pinfunction "3_3") (pintype "bidirectional"))
    )
    (net (code "233") (name "Net-(RTC1-VBAT)") (class "Default")
      (node (ref "G1") (pin "+") (pinfunction "+_+") (pintype "passive"))
      (node (ref "RTC1") (pin "6") (pinfunction "VBAT_6") (pintype "power_in"))
    )
    (net (code "234") (name "Net-(T4-1)") (class "Default")
      (node (ref "T4") (pin "P$1") (pinfunction "1_P$1") (pintype "passive"))
      (node (ref "U40") (pin "1") (pinfunction "D1_1") (pintype "passive"))
    )
    (net (code "235") (name "Net-(T4-4)") (class "Default")
      (node (ref "T4") (pin "P$4") (pinfunction "4_P$4") (pintype "passive"))
      (node (ref "U40") (pin "2") (pinfunction "D2_2") (pintype "passive"))
    )
    (net (code "236") (name "Net-(T4-5)") (class "Default")
      (node (ref "D404") (pin "A") (pinfunction "A_A") (pintype "passive"))
      (node (ref "T4") (pin "P$5") (pinfunction "5_P$5") (pintype "passive"))
    )
    (net (code "237") (name "Net-(T4-8)") (class "Default")
      (node (ref "D403") (pin "A") (pinfunction "A_A") (pintype "passive"))
      (node (ref "T4") (pin "P$8") (pinfunction "8_P$8") (pintype "passive"))
    )
    (net (code "238") (name "Net-(U1A-EEPROM_WP)") (class "Default")
      (node (ref "J1") (pin "1") (pinfunction "1_1") (pintype "bidirectional"))
      (node (ref "U1") (pin "M2") (pinfunction "EEPROM_WP_M2") (pintype "bidirectional"))
    )
    (net (code "239") (name "Net-(U1A-PWRONRSTN_OD)") (class "Default")
      (node (ref "R5") (pin "1") (pinfunction "1_1") (pintype "passive"))
      (node (ref "U1") (pin "C17") (pinfunction "PWRONRSTN_OD_C17") (pintype "bidirectional"))
    )
    (net (code "240") (name "Net-(U1A-SYS_VDD1_CTL)") (class "Default")
      (node (ref "TP33") (pin "TP") (pinfunction "TP_TP") (pintype "input"))
      (node (ref "U1") (pin "F18") (pinfunction "SYS_VDD1_CTL_F18") (pintype "bidirectional"))
    )
    (net (code "241") (name "Net-(U1C-XDMA_EVENT_INTR0)") (class "Default")
      (node (ref "R4") (pin "1") (pinfunction "1_1") (pintype "passive"))
      (node (ref "U1") (pin "W14") (pinfunction "XDMA_EVENT_INTR0_W14") (pintype "bidirectional"))
    )
    (net (code "242") (name "Net-(U1C-XDMA_EVENT_INTR1)") (class "Default")
      (node (ref "R3") (pin "1") (pinfunction "1_1") (pintype "passive"))
      (node (ref "U1") (pin "V14") (pinfunction "XDMA_EVENT_INTR1_V14") (pintype "bidirectional"))
    )
    (net (code "243") (name "Net-(U1D-LCD_AC_BIAS_EN)") (class "Default")
      (node (ref "R28") (pin "1") (pinfunction "1_1") (pintype "passive"))
      (node (ref "U1") (pin "V20") (pinfunction "LCD_AC_BIAS_EN_V20") (pintype "bidirectional"))
    )
    (net (code "244") (name "Net-(U1D-LCD_HSYNC)") (class "Default")
      (node (ref "R29") (pin "1") (pinfunction "1_1") (pintype "passive"))
      (node (ref "U1") (pin "U19") (pinfunction "LCD_HSYNC_U19") (pintype "bidirectional"))
    )
    (net (code "245") (name "Net-(U1D-LCD_PCLK)") (class "Default")
      (node (ref "R31") (pin "1") (pinfunction "1_1") (pintype "passive"))
      (node (ref "U1") (pin "U20") (pinfunction "LCD_PCLK_U20") (pintype "bidirectional"))
    )
    (net (code "246") (name "Net-(U1D-LCD_VSYNC)") (class "Default")
      (node (ref "R30") (pin "1") (pinfunction "1_1") (pintype "passive"))
      (node (ref "U1") (pin "U18") (pinfunction "LCD_VSYNC_U18") (pintype "bidirectional"))
    )
    (net (code "247") (name "Net-(U4-MR#)") (class "Default")
      (node (ref "R11") (pin "2") (pinfunction "2_2") (pintype "passive"))
      (node (ref "R5") (pin "2") (pinfunction "2_2") (pintype "passive"))
      (node (ref "U4") (pin "3") (pinfunction "MR#_3") (pintype "bidirectional"))
    )
    (net (code "248") (name "Net-(U4-RESET#)") (class "Default")
      (node (ref "R8") (pin "2") (pinfunction "2_2") (pintype "passive"))
      (node (ref "U4") (pin "2") (pinfunction "RESET#_2") (pintype "bidirectional"))
    )
    (net (code "249") (name "Net-(U5-CATHODE)") (class "Default")
      (node (ref "Q1") (pin "B") (pinfunction "B_B") (pintype "passive"))
      (node (ref "R21") (pin "1") (pinfunction "1_1") (pintype "passive"))
      (node (ref "U5") (pin "2") (pinfunction "CATHODE_2") (pintype "bidirectional"))
    )
    (net (code "250") (name "Net-(U5-REF)") (class "Default")
      (node (ref "R15") (pin "2") (pinfunction "2_2") (pintype "passive"))
      (node (ref "R20") (pin "1") (pinfunction "1_1") (pintype "passive"))
      (node (ref "U5") (pin "1") (pinfunction "REF_1") (pintype "bidirectional"))
    )
    (net (code "251") (name "Net-(U27-NINT{slash}TXER{slash}TXD4)") (class "Default")
      (node (ref "ER129") (pin "1") (pinfunction "1_1") (pintype "passive"))
      (node (ref "U27") (pin "18") (pinfunction "NINT/TXER/TXD4_18") (pintype "bidirectional"))
    )
    (net (code "252") (name "Net-(U27-RBIAS)") (class "Default")
      (node (ref "ER128") (pin "2") (pinfunction "2_2") (pintype "passive"))
      (node (ref "U27") (pin "32") (pinfunction "RBIAS_32") (pintype "passive"))
    )
    (net (code "253") (name "Net-(U27-VDDCR)") (class "Default")
      (node (ref "EC33") (pin "1") (pinfunction "1_1") (pintype "passive"))
      (node (ref "EC35") (pin "1") (pinfunction "1_1") (pintype "passive"))
      (node (ref "U27") (pin "6") (pinfunction "VDDCR_6") (pintype "power_in"))
    )
    (net (code "254") (name "Net-(U27-XTAL1{slash}CLKIN)") (class "Default")
      (node (ref "ER126") (pin "1") (pinfunction "1_1") (pintype "passive"))
      (node (ref "U27") (pin "5") (pinfunction "XTAL1/CLKIN_5") (pintype "input"))
    )
    (net (code "255") (name "Net-(U27-XTAL2)") (class "Default")
      (node (ref "ER125") (pin "1") (pinfunction "1_1") (pintype "passive"))
      (node (ref "ER127") (pin "1") (pinfunction "1_1") (pintype "passive"))
      (node (ref "U27") (pin "4") (pinfunction "XTAL2_4") (pintype "input"))
    )
    (net (code "256") (name "Net-(VREG1-IN)") (class "Default")
      (node (ref "C100") (pin "1") (pinfunction "1_1") (pintype "passive"))
      (node (ref "C101") (pin "1") (pinfunction "1_1") (pintype "passive"))
      (node (ref "D3") (pin "C") (pinfunction "C_C") (pintype "passive"))
      (node (ref "J24") (pin "2") (pinfunction "2_2") (pintype "bidirectional"))
      (node (ref "VREG1") (pin "1") (pinfunction "IN_1") (pintype "input"))
    )
    (net (code "257") (name "Net-(X2-GRNC)") (class "Default")
      (node (ref "ER117") (pin "2") (pinfunction "2_2") (pintype "passive"))
      (node (ref "X2") (pin "10") (pinfunction "GRNC_10") (pintype "passive"))
    )
    (net (code "258") (name "Net-(X2-RCT)") (class "Default")
      (node (ref "EC40") (pin "1") (pinfunction "1_1") (pintype "passive"))
      (node (ref "ER122") (pin "2") (pinfunction "2_2") (pintype "passive"))
      (node (ref "X2") (pin "4") (pinfunction "TCT_4") (pintype "passive"))
      (node (ref "X2") (pin "5") (pinfunction "RCT_5") (pintype "passive"))
    )
    (net (code "259") (name "Net-(X2-YELC)") (class "Default")
      (node (ref "ER115") (pin "2") (pinfunction "2_2") (pintype "passive"))
      (node (ref "X2") (pin "11") (pinfunction "YELC_11") (pintype "passive"))
    )
    (net (code "260") (name "Net-(X10A-SK)") (class "Default")
      (node (ref "J11") (pin "1") (pinfunction "1_1") (pintype "bidirectional"))
      (node (ref "J12") (pin "1") (pinfunction "1_1") (pintype "bidirectional"))
      (node (ref "R181") (pin "1") (pinfunction "1_1") (pintype "passive"))
      (node (ref "R214") (pin "1") (pinfunction "1_1") (pintype "passive"))
      (node (ref "X10") (pin "1") (pinfunction "SK_1") (pintype "passive"))
    )
    (net (code "261") (name "Net-(X10C-SK)") (class "Default")
      (node (ref "J21") (pin "1") (pinfunction "1_1") (pintype "bidirectional"))
      (node (ref "J22") (pin "1") (pinfunction "1_1") (pintype "bidirectional"))
      (node (ref "R182") (pin "1") (pinfunction "1_1") (pintype "passive"))
      (node (ref "R224") (pin "1") (pinfunction "1_1") (pintype "passive"))
      (node (ref "X10") (pin "3") (pinfunction "SK_3") (pintype "passive"))
    )
    (net (code "262") (name "Net-(X11A-SK)") (class "Default")
      (node (ref "J31") (pin "1") (pinfunction "1_1") (pintype "bidirectional"))
      (node (ref "J32") (pin "1") (pinfunction "1_1") (pintype "bidirectional"))
      (node (ref "R183") (pin "1") (pinfunction "1_1") (pintype "passive"))
      (node (ref "R234") (pin "1") (pinfunction "1_1") (pintype "passive"))
      (node (ref "X11") (pin "1") (pinfunction "SK_1") (pintype "passive"))
    )
    (net (code "263") (name "Net-(X11C-SK)") (class "Default")
      (node (ref "J41") (pin "1") (pinfunction "1_1") (pintype "bidirectional"))
      (node (ref "J42") (pin "1") (pinfunction "1_1") (pintype "bidirectional"))
      (node (ref "R184") (pin "1") (pinfunction "1_1") (pintype "passive"))
      (node (ref "R244") (pin "1") (pinfunction "1_1") (pintype "passive"))
      (node (ref "X11") (pin "3") (pinfunction "SK_3") (pintype "passive"))
    )
    (net (code "264") (name "Net-(X12A-SK)") (class "Default")
      (node (ref "J51") (pin "1") (pinfunction "1_1") (pintype "bidirectional"))
      (node (ref "J52") (pin "1") (pinfunction "1_1") (pintype "bidirectional"))
      (node (ref "R185") (pin "1") (pinfunction "1_1") (pintype "passive"))
      (node (ref "R254") (pin "1") (pinfunction "1_1") (pintype "passive"))
      (node (ref "X12") (pin "1") (pinfunction "SK_1") (pintype "passive"))
    )
    (net (code "265") (name "Net-(X12C-SK)") (class "Default")
      (node (ref "J61") (pin "1") (pinfunction "1_1") (pintype "bidirectional"))
      (node (ref "J62") (pin "1") (pinfunction "1_1") (pintype "bidirectional"))
      (node (ref "R186") (pin "1") (pinfunction "1_1") (pintype "passive"))
      (node (ref "R264") (pin "1") (pinfunction "1_1") (pintype "passive"))
      (node (ref "X12") (pin "3") (pinfunction "SK_3") (pintype "passive"))
    )
    (net (code "266") (name "Net-(X41B-1)") (class "Default")
      (node (ref "F402") (pin "1") (pinfunction "1_1") (pintype "passive"))
      (node (ref "GDT1") (pin "1") (pinfunction "1_1") (pintype "passive"))
      (node (ref "X41") (pin "2") (pinfunction "1_2") (pintype "passive"))
    )
    (net (code "267") (name "Net-(Y7-1)") (class "Default")
      (node (ref "EC41") (pin "1") (pinfunction "1_1") (pintype "passive"))
      (node (ref "ER127") (pin "2") (pinfunction "2_2") (pintype "passive"))
      (node (ref "Y7") (pin "P$1") (pinfunction "1_P$1") (pintype "passive"))
    )
    (net (code "268") (name "Net-(Y7-2)") (class "Default")
      (node (ref "EC42") (pin "1") (pinfunction "1_1") (pintype "passive"))
      (node (ref "ER125") (pin "2") (pinfunction "2_2") (pintype "passive"))
      (node (ref "ER126") (pin "2") (pinfunction "2_2") (pintype "passive"))
      (node (ref "Y7") (pin "P$2") (pinfunction "2_P$2") (pintype "passive"))
    )
    (net (code "269") (name "SYS_ADC_1P8V") (class "Default")
      (node (ref "C10") (pin "1") (pinfunction "1_1") (pintype "passive"))
      (node (ref "IC14") (pin "3") (pinfunction "+IN_3") (pintype "input"))
      (node (ref "IC14") (pin "5") (pinfunction "+IN_5") (pintype "input"))
      (node (ref "R33") (pin "2") (pinfunction "2_2") (pintype "passive"))
      (node (ref "U1") (pin "Y12") (pinfunction "SYS_ADC_1P8V_Y12") (pintype "bidirectional"))
    )
    (net (code "270") (name "SYS_RTC_1P8V") (class "Default")
      (node (ref "Q1") (pin "C") (pinfunction "C_C") (pintype "passive"))
      (node (ref "R15") (pin "1") (pinfunction "1_1") (pintype "passive"))
      (node (ref "TP14") (pin "TP") (pinfunction "TP_TP") (pintype "input"))
      (node (ref "U1") (pin "K13") (pinfunction "SYS_RTC_1P8V_K13") (pintype "power_in"))
      (node (ref "U1") (pin "K14") (pinfunction "SYS_RTC_1P8V_K14") (pintype "power_in"))
      (node (ref "U1") (pin "L13") (pinfunction "SYS_RTC_1P8V_L13") (pintype "power_in"))
      (node (ref "U1") (pin "L14") (pinfunction "SYS_RTC_1P8V_L14") (pintype "power_in"))
      (node (ref "U1") (pin "M13") (pinfunction "VDDS_RTC_M13") (pintype "bidirectional"))
      (node (ref "U1") (pin "M14") (pinfunction "VDDS_M14") (pintype "bidirectional"))
      (node (ref "U5") (pin "3") (pinfunction "ANODE_3") (pintype "bidirectional"))
    )
    (net (code "271") (name "SYS_VDD1_3P3V") (class "Default")
      (node (ref "C104") (pin "1") (pinfunction "1_1") (pintype "passive"))
      (node (ref "C15") (pin "1") (pinfunction "1_1") (pintype "passive"))
      (node (ref "C21") (pin "1") (pinfunction "1_1") (pintype "passive"))
      (node (ref "C22") (pin "1") (pinfunction "1_1") (pintype "passive"))
      (node (ref "C301") (pin "1") (pinfunction "1_1") (pintype "passive"))
      (node (ref "C401") (pin "1") (pinfunction "1_1") (pintype "passive"))
      (node (ref "C404") (pin "1") (pinfunction "1_1") (pintype "passive"))
      (node (ref "C6") (pin "2") (pinfunction "2_2") (pintype "passive"))
      (node (ref "C79") (pin "1") (pinfunction "1_1") (pintype "passive"))
      (node (ref "C801") (pin "1") (pinfunction "1_1") (pintype "passive"))
      (node (ref "C85") (pin "1") (pinfunction "1_1") (pintype "passive"))
      (node (ref "C87") (pin "1") (pinfunction "1_1") (pintype "passive"))
      (node (ref "C88") (pin "1") (pinfunction "1_1") (pintype "passive"))
      (node (ref "EC34") (pin "1") (pinfunction "1_1") (pintype "passive"))
      (node (ref "ER100") (pin "1") (pinfunction "1_1") (pintype "passive"))
      (node (ref "ER105") (pin "1") (pinfunction "1_1") (pintype "passive"))
      (node (ref "ER98") (pin "1") (pinfunction "1_1") (pintype "passive"))
      (node (ref "ER99") (pin "1") (pinfunction "1_1") (pintype "passive"))
      (node (ref "FB7") (pin "1") (pinfunction "1_1") (pintype "passive"))
      (node (ref "IC14") (pin "8") (pinfunction "V+_8") (pintype "power_in"))
      (node (ref "R12") (pin "2") (pinfunction "2_2") (pintype "passive"))
      (node (ref "R13") (pin "2") (pinfunction "2_2") (pintype "passive"))
      (node (ref "R163") (pin "2") (pinfunction "2_2") (pintype "passive"))
      (node (ref "R164") (pin "1") (pinfunction "1_1") (pintype "passive"))
      (node (ref "R169") (pin "2") (pinfunction "2_2") (pintype "passive"))
      (node (ref "R170") (pin "2") (pinfunction "2_2") (pintype "passive"))
      (node (ref "R22") (pin "2") (pinfunction "2_2") (pintype "passive"))
      (node (ref "R303") (pin "2") (pinfunction "2_2") (pintype "passive"))
      (node (ref "R40") (pin "2") (pinfunction "2_2") (pintype "passive"))
      (node (ref "R41") (pin "2") (pinfunction "2_2") (pintype "passive"))
      (node (ref "R70") (pin "2") (pinfunction "2_2") (pintype "passive"))
      (node (ref "R71") (pin "2") (pinfunction "2_2") (pintype "passive"))
      (node (ref "R72") (pin "2") (pinfunction "2_2") (pintype "passive"))
      (node (ref "R73") (pin "2") (pinfunction "2_2") (pintype "passive"))
      (node (ref "R74") (pin "2") (pinfunction "2_2") (pintype "passive"))
      (node (ref "R75") (pin "2") (pinfunction "2_2") (pintype "passive"))
      (node (ref "R76") (pin "2") (pinfunction "2_2") (pintype "passive"))
      (node (ref "R77") (pin "2") (pinfunction "2_2") (pintype "passive"))
      (node (ref "R78") (pin "2") (pinfunction "2_2") (pintype "passive"))
      (node (ref "R79") (pin "2") (pinfunction "2_2") (pintype "passive"))
      (node (ref "R80") (pin "2") (pinfunction "2_2") (pintype "passive"))
      (node (ref "R81") (pin "2") (pinfunction "2_2") (pintype "passive"))
      (node (ref "R82") (pin "2") (pinfunction "2_2") (pintype "passive"))
      (node (ref "R83") (pin "2") (pinfunction "2_2") (pintype "passive"))
      (node (ref "R84") (pin "2") (pinfunction "2_2") (pintype "passive"))
      (node (ref "R85") (pin "2") (pinfunction "2_2") (pintype "passive"))
      (node (ref "R86") (pin "2") (pinfunction "2_2") (pintype "passive"))
      (node (ref "R87") (pin "2") (pinfunction "2_2") (pintype "passive"))
      (node (ref "R88") (pin "2") (pinfunction "2_2") (pintype "passive"))
      (node (ref "R89") (pin "2") (pinfunction "2_2") (pintype "passive"))
      (node (ref "R90") (pin "2") (pinfunction "2_2") (pintype "passive"))
      (node (ref "R91") (pin "2") (pinfunction "2_2") (pintype "passive"))
      (node (ref "R92") (pin "2") (pinfunction "2_2") (pintype "passive"))
      (node (ref "RTC1") (pin "2") (pinfunction "VCC_2") (pintype "power_in"))
      (node (ref "S11") (pin "C") (pinfunction "C_C") (pintype "passive"))
      (node (ref "S12") (pin "C") (pinfunction "C_C") (pintype "passive"))
      (node (ref "S13") (pin "1") (pinfunction "1_1") (pintype "passive"))
      (node (ref "S13") (pin "2") (pinfunction "2_2") (pintype "passive"))
      (node (ref "S13") (pin "3") (pinfunction "3_3") (pintype "passive"))
      (node (ref "S13") (pin "4") (pinfunction "4_4") (pintype "passive"))
      (node (ref "T4") (pin "P$2") (pinfunction "2_P$2") (pintype "passive"))
      (node (ref "T4") (pin "P$3") (pinfunction "3_P$3") (pintype "passive"))
      (node (ref "TP12") (pin "TP") (pinfunction "TP_TP") (pintype "input"))
      (node (ref "U1") (pin "F8") (pinfunction "EMMC_VCC_F8") (pintype "bidirectional"))
      (node (ref "U1") (pin "F9") (pinfunction "EMMC_VCC_F9") (pintype "bidirectional"))
      (node (ref "U1") (pin "G8") (pinfunction "EMMC_VCC_G8") (pintype "bidirectional"))
      (node (ref "U1") (pin "G9") (pinfunction "EMMC_VCC_G9") (pintype "bidirectional"))
      (node (ref "U1") (pin "H14") (pinfunction "SYS_VDD1_3P3V_H14") (pintype "power_in"))
      (node (ref "U1") (pin "H15") (pinfunction "SYS_VDD1_3P3V_H15") (pintype "power_in"))
      (node (ref "U1") (pin "H7") (pinfunction "EMMC_VCCQ_H7") (pintype "bidirectional"))
      (node (ref "U1") (pin "H8") (pinfunction "EMMC_VCCQ_H8") (pintype "bidirectional"))
      (node (ref "U1") (pin "J14") (pinfunction "SYS_VDD1_3P3V_J14") (pintype "power_in"))
      (node (ref "U1") (pin "J15") (pinfunction "SYS_VDD1_3P3V_J15") (pintype "power_in"))
      (node (ref "U1") (pin "J7") (pinfunction "EMMC_VCCQ_J7") (pintype "bidirectional"))
      (node (ref "U1") (pin "J8") (pinfunction "EMMC_VCCQ_J8") (pintype "bidirectional"))
      (node (ref "U16") (pin "1") (pinfunction "VCC_1") (pintype "bidirectional"))
      (node (ref "U16") (pin "22") (pinfunction "VCC_22") (pintype "bidirectional"))
      (node (ref "U16") (pin "8") (pinfunction "VCC_8") (pintype "bidirectional"))
      (node (ref "U27") (pin "12") (pinfunction "VDDIO_12") (pintype "power_in"))
      (node (ref "U28") (pin "3") (pinfunction "VCC_3") (pintype "power_in"))
      (node (ref "U29") (pin "8") (pinfunction "VCC_8") (pintype "power_in"))
      (node (ref "U4") (pin "4") (pinfunction "VCC_4") (pintype "bidirectional"))
      (node (ref "U40") (pin "4") (pinfunction "VCC1_4") (pintype "power_in"))
      (node (ref "U6") (pin "7") (pinfunction "2OE_7") (pintype "input"))
      (node (ref "U6") (pin "8") (pinfunction "VCC_8") (pintype "power_in"))
      (node (ref "X4") (pin "5") (pinfunction "TVDD_5") (pintype "bidirectional"))
      (node (ref "X5") (pin "4") (pinfunction "VDD_4") (pintype "bidirectional"))
    )
    (net (code "272") (name "SYS_VDD2_3P3V") (class "Default")
      (node (ref "D1") (pin "1") (pinfunction "A_1") (pintype "passive"))
      (node (ref "TP13") (pin "TP") (pinfunction "TP_TP") (pintype "input"))
      (node (ref "U1") (pin "F12") (pinfunction "SYS_VDD2_3P3V_F12") (pintype "power_in"))
      (node (ref "U1") (pin "F13") (pinfunction "SYS_VDD2_3P3V_F13") (pintype "power_in"))
      (node (ref "U1") (pin "G12") (pinfunction "SYS_VDD2_3P3V_G12") (pintype "power_in"))
      (node (ref "U1") (pin "G13") (pinfunction "SYS_VDD2_3P3V_G13") (pintype "power_in"))
    )
    (net (code "273") (name "SYS_VDD3_3P3V") (class "Default")
      (node (ref "Q1") (pin "E") (pinfunction "E_E") (pintype "passive"))
      (node (ref "R20") (pin "2") (pinfunction "2_2") (pintype "passive"))
      (node (ref "R21") (pin "2") (pinfunction "2_2") (pintype "passive"))
      (node (ref "TP16") (pin "TP") (pinfunction "TP_TP") (pintype "input"))
      (node (ref "U1") (pin "K10") (pinfunction "SYS_VDD3_3P3V_K10") (pintype "power_in"))
      (node (ref "U1") (pin "K11") (pinfunction "SYS_VDD3_3P3V_K11") (pintype "power_in"))
      (node (ref "U1") (pin "L10") (pinfunction "SYS_VDD3_3P3V_L10") (pintype "power_in"))
      (node (ref "U1") (pin "L11") (pinfunction "SYS_VDD3_3P3V_L11") (pintype "power_in"))
      (node (ref "U1") (pin "L12") (pinfunction "SYS_VDD3_3P3V_L12") (pintype "power_in"))
      (node (ref "U1") (pin "L7") (pinfunction "SYS_VDD3_3P3V_L7") (pintype "power_in"))
      (node (ref "U1") (pin "L8") (pinfunction "SYS_VDD3_3P3V_L8") (pintype "power_in"))
      (node (ref "U1") (pin "L9") (pinfunction "SYS_VDD3_3P3V_L9") (pintype "power_in"))
      (node (ref "U1") (pin "M10") (pinfunction "VDDSHV2_M10") (pintype "power_in"))
      (node (ref "U1") (pin "M11") (pinfunction "VDDSHV1_M11") (pintype "power_in"))
      (node (ref "U1") (pin "M12") (pinfunction "VDDSHV6_M12") (pintype "power_in"))
      (node (ref "U1") (pin "M7") (pinfunction "VDDSHV4_M7") (pintype "power_in"))
      (node (ref "U1") (pin "M8") (pinfunction "VDDSHV5_M8") (pintype "power_in"))
      (node (ref "U1") (pin "M9") (pinfunction "VDDSHV3_M9") (pintype "power_in"))
    )
    (net (code "274") (name "SYS_VDD_1P8V") (class "Default")
      (node (ref "TP15") (pin "TP") (pinfunction "TP_TP") (pintype "input"))
      (node (ref "U1") (pin "N10") (pinfunction "SYS_VDD_1P8V_N10") (pintype "power_in"))
      (node (ref "U1") (pin "N11") (pinfunction "SYS_VDD_1P8V_N11") (pintype "power_in"))
      (node (ref "U1") (pin "N12") (pinfunction "SYS_VDD_1P8V_N12") (pintype "power_in"))
      (node (ref "U1") (pin "N13") (pinfunction "SYS_VDD_1P8V_N13") (pintype "power_in"))
      (node (ref "U1") (pin "N14") (pinfunction "SYS_VDD_1P8V_N14") (pintype "power_in"))
      (node (ref "U1") (pin "N7") (pinfunction "SYS_VDD_1P8V_N7") (pintype "power_in"))
      (node (ref "U1") (pin "N8") (pinfunction "SYS_VDD_1P8V_N8") (pintype "power_in"))
      (node (ref "U1") (pin "N9") (pinfunction "SYS_VDD_1P8V_N9") (pintype "power_in"))
      (node (ref "U1") (pin "P10") (pinfunction "SYS_VDD_1P8V_P10") (pintype "power_in"))
      (node (ref "U1") (pin "P11") (pinfunction "SYS_VDD_1P8V_P11") (pintype "power_in"))
    )
    (net (code "275") (name "SYS_VOUT") (class "Default")
      (node (ref "C4") (pin "1") (pinfunction "1_1") (pintype "passive"))
      (node (ref "TP11") (pin "TP") (pinfunction "TP_TP") (pintype "input"))
      (node (ref "U1") (pin "F14") (pinfunction "SYS_VOUT_F14") (pintype "power_in"))
      (node (ref "U1") (pin "F15") (pinfunction "SYS_VOUT_F15") (pintype "power_in"))
      (node (ref "U1") (pin "G14") (pinfunction "SYS_VOUT_G14") (pintype "power_in"))
      (node (ref "U1") (pin "G15") (pinfunction "SYS_VOUT_G15") (pintype "power_in"))
    )
    (net (code "276") (name "VDD_5V") (class "Default")
      (node (ref "C102") (pin "1") (pinfunction "1_1") (pintype "passive"))
      (node (ref "C11") (pin "+") (pinfunction "+_+") (pintype "passive"))
      (node (ref "L2") (pin "2") (pinfunction "2_2") (pintype "passive"))
      (node (ref "U1") (pin "C18") (pinfunction "VIN_AC_C18") (pintype "power_in"))
      (node (ref "U1") (pin "C19") (pinfunction "VIN_AC_C19") (pintype "power_in"))
      (node (ref "U1") (pin "C20") (pinfunction "VIN_AC_C20") (pintype "power_in"))
      (node (ref "VREG1") (pin "4") (pinfunction "FB_4") (pintype "input"))
    )
    (net (code "277") (name "VDD_BAT") (class "Default")
      (node (ref "TP5") (pin "P$1") (pinfunction "TP_P$1") (pintype "bidirectional"))
      (node (ref "U1") (pin "D18") (pinfunction "VIN_BAT_D18") (pintype "power_in"))
      (node (ref "U1") (pin "D19") (pinfunction "VIN_BAT_D19") (pintype "power_in"))
      (node (ref "U1") (pin "D20") (pinfunction "VIN_BAT_D20") (pintype "power_in"))
    )
    (net (code "278") (name "VDD_ETH_PHY") (class "Default")
      (node (ref "EC30") (pin "1") (pinfunction "1_1") (pintype "passive"))
      (node (ref "EC31") (pin "1") (pinfunction "1_1") (pintype "passive"))
      (node (ref "EC32") (pin "1") (pinfunction "1_1") (pintype "passive"))
      (node (ref "ER106") (pin "1") (pinfunction "1_1") (pintype "passive"))
      (node (ref "ER107") (pin "1") (pinfunction "1_1") (pintype "passive"))
      (node (ref "ER108") (pin "1") (pinfunction "1_1") (pintype "passive"))
      (node (ref "ER109") (pin "1") (pinfunction "1_1") (pintype "passive"))
      (node (ref "ER122") (pin "1") (pinfunction "1_1") (pintype "passive"))
      (node (ref "FB7") (pin "2") (pinfunction "2_2") (pintype "passive"))
      (node (ref "U27") (pin "1") (pinfunction "VDD2A_1") (pintype "power_in"))
      (node (ref "U27") (pin "27") (pinfunction "VDD1A_27") (pintype "power_in"))
    )
    (net (code "279") (name "VDD_USB_5V") (class "Default")
      (node (ref "C3") (pin "1") (pinfunction "1_1") (pintype "passive"))
      (node (ref "R10") (pin "2") (pinfunction "2_2") (pintype "passive"))
      (node (ref "U1") (pin "B18") (pinfunction "VIN_USB_B18") (pintype "power_in"))
      (node (ref "U1") (pin "B19") (pinfunction "VIN_USB_B19") (pintype "power_in"))
      (node (ref "U1") (pin "B20") (pinfunction "VIN_USB_B20") (pintype "power_in"))
      (node (ref "U1") (pin "K1") (pinfunction "USB0_VBUS_K1") (pintype "bidirectional"))
      (node (ref "U2") (pin "6") (pinfunction "VBUS_6") (pintype "passive"))
    )
    (net (code "280") (name "unconnected-(F401-Pad2)") (class "Default")
      (node (ref "F401") (pin "2") (pinfunction "2_2") (pintype "passive"))
    )
    (net (code "281") (name "unconnected-(F402-Pad2)") (class "Default")
      (node (ref "F402") (pin "2") (pinfunction "2_2") (pintype "passive"))
    )
    (net (code "282") (name "unconnected-(FUD1-PadP$1)") (class "Default")
      (node (ref "FUD1") (pin "P$1") (pinfunction "P$1_P$1") (pintype "no_connect"))
    )
    (net (code "283") (name "unconnected-(FUD2-PadP$1)") (class "Default")
      (node (ref "FUD2") (pin "P$1") (pinfunction "P$1_P$1") (pintype "no_connect"))
    )
    (net (code "284") (name "unconnected-(FUD3-PadP$1)") (class "Default")
      (node (ref "FUD3") (pin "P$1") (pinfunction "P$1_P$1") (pintype "no_connect"))
    )
    (net (code "285") (name "unconnected-(FUD4-PadP$1)") (class "Default")
      (node (ref "FUD4") (pin "P$1") (pinfunction "P$1_P$1") (pintype "no_connect"))
    )
    (net (code "286") (name "unconnected-(FUD5-PadP$1)") (class "Default")
      (node (ref "FUD5") (pin "P$1") (pinfunction "P$1_P$1") (pintype "no_connect"))
    )
    (net (code "287") (name "unconnected-(FUD6-PadP$1)") (class "Default")
      (node (ref "FUD6") (pin "P$1") (pinfunction "P$1_P$1") (pintype "no_connect"))
    )
    (net (code "288") (name "unconnected-(G1-+-Pad+@1)") (class "Default")
      (node (ref "G1") (pin "+@1") (pinfunction "+_+@1") (pintype "passive"))
    )
    (net (code "289") (name "unconnected-(IC2-I6-Pad6)") (class "Default")
      (node (ref "IC2") (pin "6") (pinfunction "I6_6") (pintype "input"))
    )
    (net (code "290") (name "unconnected-(IC2-I7-Pad7)") (class "Default")
      (node (ref "IC2") (pin "7") (pinfunction "I7_7") (pintype "input"))
    )
    (net (code "291") (name "unconnected-(IC2-O6-Pad11)") (class "Default")
      (node (ref "IC2") (pin "11") (pinfunction "O6_11") (pintype "open_collector"))
    )
    (net (code "292") (name "unconnected-(IC2-O7-Pad10)") (class "Default")
      (node (ref "IC2") (pin "10") (pinfunction "O7_10") (pintype "open_collector"))
    )
    (net (code "293") (name "unconnected-(IC4A-~{QH}-Pad7)") (class "Default")
      (node (ref "IC4") (pin "7") (pinfunction "~{QH}_7") (pintype "output"))
    )
    (net (code "294") (name "unconnected-(IC5A-~{QH}-Pad7)") (class "Default")
      (node (ref "IC5") (pin "7") (pinfunction "~{QH}_7") (pintype "output"))
    )
    (net (code "295") (name "unconnected-(K1B-O-PadNC)") (class "Default")
      (node (ref "K1") (pin "NC") (pinfunction "O_NC") (pintype "passive"))
    )
    (net (code "296") (name "unconnected-(K2B-O-PadNC)") (class "Default")
      (node (ref "K2") (pin "NC") (pinfunction "O_NC") (pintype "passive"))
    )
    (net (code "297") (name "unconnected-(K3B-O-PadNC)") (class "Default")
      (node (ref "K3") (pin "NC") (pinfunction "O_NC") (pintype "passive"))
    )
    (net (code "298") (name "unconnected-(K4B-O-PadNC)") (class "Default")
      (node (ref "K4") (pin "NC") (pinfunction "O_NC") (pintype "passive"))
    )
    (net (code "299") (name "unconnected-(K5B-O-PadNC)") (class "Default")
      (node (ref "K5") (pin "NC") (pinfunction "O_NC") (pintype "passive"))
    )
    (net (code "300") (name "unconnected-(RTC1-SQW-Pad3)") (class "Default")
      (node (ref "RTC1") (pin "3") (pinfunction "SQW_3") (pintype "output"))
    )
    (net (code "301") (name "unconnected-(U1A-VDDS_RTC-PadU14)") (class "Default")
      (node (ref "U1") (pin "U14") (pinfunction "VDDS_RTC_U14") (pintype "bidirectional"))
    )
    (net (code "302") (name "unconnected-(U1B-USB0_CE-PadL3)") (class "Default")
      (node (ref "U1") (pin "L3") (pinfunction "USB0_CE_L3") (pintype "bidirectional"))
    )
    (net (code "303") (name "unconnected-(U1B-USB1_CE-PadJ3)") (class "Default")
      (node (ref "U1") (pin "J3") (pinfunction "USB1_CE_J3") (pintype "bidirectional"))
    )
    (net (code "304") (name "unconnected-(U1B-USB1_DM-PadH2)") (class "Default")
      (node (ref "U1") (pin "H2") (pinfunction "USB1_DM_H2") (pintype "bidirectional"))
    )
    (net (code "305") (name "unconnected-(U1B-USB1_DP-PadJ2)") (class "Default")
      (node (ref "U1") (pin "J2") (pinfunction "USB1_DP_J2") (pintype "bidirectional"))
    )
    (net (code "306") (name "unconnected-(U1B-USB1_DRVVBUS-PadH3)") (class "Default")
      (node (ref "U1") (pin "H3") (pinfunction "USB1_DRVVBUS_H3") (pintype "bidirectional"))
    )
    (net (code "307") (name "unconnected-(U1B-USB1_ID-PadJ1)") (class "Default")
      (node (ref "U1") (pin "J1") (pinfunction "USB1_ID_J1") (pintype "bidirectional"))
    )
    (net (code "308") (name "unconnected-(U1B-USB1_VBUS-PadH1)") (class "Default")
      (node (ref "U1") (pin "H1") (pinfunction "USB1_VBUS_H1") (pintype "bidirectional"))
    )
    (net (code "309") (name "unconnected-(U1C-ECAP0_IN_PWM0_OUT-PadV15)") (class "Default")
      (node (ref "U1") (pin "V15") (pinfunction "ECAP0_IN_PWM0_OUT_V15") (pintype "bidirectional"))
    )
    (net (code "310") (name "unconnected-(U1C-EMMC_RSTN-PadA4)") (class "Default")
      (node (ref "U1") (pin "A4") (pinfunction "EMMC_RSTN_A4") (pintype "bidirectional"))
    )
    (net (code "311") (name "unconnected-(U1C-GPMC_A0-PadA13)") (class "Default")
      (node (ref "U1") (pin "A13") (pinfunction "GPMC_A0_A13") (pintype "bidirectional"))
    )
    (net (code "312") (name "unconnected-(U1C-GPMC_A4-PadB12)") (class "Default")
      (node (ref "U1") (pin "B12") (pinfunction "GPMC_A4_B12") (pintype "bidirectional"))
    )
    (net (code "313") (name "unconnected-(U1C-GPMC_A9-PadA10)") (class "Default")
      (node (ref "U1") (pin "A10") (pinfunction "GPMC_A9_A10") (pintype "bidirectional"))
    )
    (net (code "314") (name "unconnected-(U1C-GPMC_A10-PadB10)") (class "Default")
      (node (ref "U1") (pin "B10") (pinfunction "GPMC_A10_B10") (pintype "bidirectional"))
    )
    (net (code "315") (name "unconnected-(U1C-GPMC_A11-PadC10)") (class "Default")
      (node (ref "U1") (pin "C10") (pinfunction "GPMC_A11_C10") (pintype "bidirectional"))
    )
    (net (code "316") (name "unconnected-(U1C-GPMC_AD10-PadB16)") (class "Default")
      (node (ref "U1") (pin "B16") (pinfunction "GPMC_AD10_B16") (pintype "bidirectional"))
    )
    (net (code "317") (name "unconnected-(U1C-GPMC_AD11-PadA16)") (class "Default")
      (node (ref "U1") (pin "A16") (pinfunction "GPMC_AD11_A16") (pintype "bidirectional"))
    )
    (net (code "318") (name "unconnected-(U1C-GPMC_ADVN_ALE-PadL19)") (class "Default")
      (node (ref "U1") (pin "L19") (pinfunction "GPMC_ADVN_ALE_L19") (pintype "bidirectional"))
    )
    (net (code "319") (name "unconnected-(U1C-GPMC_BEN0_CLE-PadL20)") (class "Default")
      (node (ref "U1") (pin "L20") (pinfunction "GPMC_BEN0_CLE_L20") (pintype "bidirectional"))
    )
    (net (code "320") (name "unconnected-(U1C-GPMC_CLK-PadA14)") (class "Default")
      (node (ref "U1") (pin "A14") (pinfunction "GPMC_CLK_A14") (pintype "bidirectional"))
    )
    (net (code "321") (name "unconnected-(U1C-GPMC_OEN_REN-PadK19)") (class "Default")
      (node (ref "U1") (pin "K19") (pinfunction "GPMC_OEN_REN_K19") (pintype "bidirectional"))
    )
    (net (code "322") (name "unconnected-(U1C-GPMC_WEN-PadK18)") (class "Default")
      (node (ref "U1") (pin "K18") (pinfunction "GPMC_WEN_K18") (pintype "bidirectional"))
    )
    (net (code "323") (name "unconnected-(U1C-MCASP0_ACLKR-PadY15)") (class "Default")
      (node (ref "U1") (pin "Y15") (pinfunction "MCASP0_ACLKR_Y15") (pintype "bidirectional"))
    )
    (net (code "324") (name "unconnected-(U1C-MCASP0_AHCLKX-PadV16)") (class "Default")
      (node (ref "U1") (pin "V16") (pinfunction "MCASP0_AHCLKX_V16") (pintype "bidirectional"))
    )
    (net (code "325") (name "unconnected-(U1C-MCASP0_AXR1-PadV17)") (class "Default")
      (node (ref "U1") (pin "V17") (pinfunction "MCASP0_AXR1_V17") (pintype "bidirectional"))
    )
    (net (code "326") (name "unconnected-(U1C-SPI0_CS0-PadY4)") (class "Default")
      (node (ref "U1") (pin "Y4") (pinfunction "SPI0_CS0_Y4") (pintype "bidirectional"))
    )
    (net (code "327") (name "unconnected-(U1D-RMII1_REF_CLK-PadM3)") (class "Default")
      (node (ref "U1") (pin "M3") (pinfunction "RMII1_REF_CLK_M3") (pintype "bidirectional"))
    )
    (net (code "328") (name "unconnected-(U1F-CAP_VDD_RTC-PadV13)") (class "Default")
      (node (ref "U1") (pin "V13") (pinfunction "CAP_VDD_RTC_V13") (pintype "bidirectional"))
    )
    (net (code "329") (name "unconnected-(U1G-NC-PadA2)") (class "Default")
      (node (ref "U1") (pin "A2") (pinfunction "NC_A2") (pintype "bidirectional"))
    )
    (net (code "330") (name "unconnected-(U1G-NC-PadA3)") (class "Default")
      (node (ref "U1") (pin "A3") (pinfunction "NC_A3") (pintype "bidirectional"))
    )
    (net (code "331") (name "unconnected-(U1G-NC-PadA5)") (class "Default")
      (node (ref "U1") (pin "A5") (pinfunction "NC_A5") (pintype "bidirectional"))
    )
    (net (code "332") (name "unconnected-(U1G-NC-PadA6)") (class "Default")
      (node (ref "U1") (pin "A6") (pinfunction "NC_A6") (pintype "bidirectional"))
    )
    (net (code "333") (name "unconnected-(U1G-NC-PadA7)") (class "Default")
      (node (ref "U1") (pin "A7") (pinfunction "NC_A7") (pintype "bidirectional"))
    )
    (net (code "334") (name "unconnected-(U1G-NC-PadA8)") (class "Default")
      (node (ref "U1") (pin "A8") (pinfunction "NC_A8") (pintype "bidirectional"))
    )
    (net (code "335") (name "unconnected-(U1G-NC-PadB1)") (class "Default")
      (node (ref "U1") (pin "B1") (pinfunction "NC_B1") (pintype "bidirectional"))
    )
    (net (code "336") (name "unconnected-(U1G-NC-PadB2)") (class "Default")
      (node (ref "U1") (pin "B2") (pinfunction "NC_B2") (pintype "bidirectional"))
    )
    (net (code "337") (name "unconnected-(U1G-NC-PadB3)") (class "Default")
      (node (ref "U1") (pin "B3") (pinfunction "NC_B3") (pintype "bidirectional"))
    )
    (net (code "338") (name "unconnected-(U1G-NC-PadB4)") (class "Default")
      (node (ref "U1") (pin "B4") (pinfunction "NC_B4") (pintype "bidirectional"))
    )
    (net (code "339") (name "unconnected-(U1G-NC-PadB5)") (class "Default")
      (node (ref "U1") (pin "B5") (pinfunction "NC_B5") (pintype "bidirectional"))
    )
    (net (code "340") (name "unconnected-(U1G-NC-PadB6)") (class "Default")
      (node (ref "U1") (pin "B6") (pinfunction "NC_B6") (pintype "bidirectional"))
    )
    (net (code "341") (name "unconnected-(U1G-NC-PadB7)") (class "Default")
      (node (ref "U1") (pin "B7") (pinfunction "NC_B7") (pintype "bidirectional"))
    )
    (net (code "342") (name "unconnected-(U1G-NC-PadB8)") (class "Default")
      (node (ref "U1") (pin "B8") (pinfunction "NC_B8") (pintype "bidirectional"))
    )
    (net (code "343") (name "unconnected-(U1G-NC-PadC1)") (class "Default")
      (node (ref "U1") (pin "C1") (pinfunction "NC_C1") (pintype "bidirectional"))
    )
    (net (code "344") (name "unconnected-(U1G-NC-PadC2)") (class "Default")
      (node (ref "U1") (pin "C2") (pinfunction "NC_C2") (pintype "bidirectional"))
    )
    (net (code "345") (name "unconnected-(U1G-NC-PadC3)") (class "Default")
      (node (ref "U1") (pin "C3") (pinfunction "NC_C3") (pintype "bidirectional"))
    )
    (net (code "346") (name "unconnected-(U1G-NC-PadC4)") (class "Default")
      (node (ref "U1") (pin "C4") (pinfunction "NC_C4") (pintype "bidirectional"))
    )
    (net (code "347") (name "unconnected-(U1G-NC-PadC5)") (class "Default")
      (node (ref "U1") (pin "C5") (pinfunction "NC_C5") (pintype "bidirectional"))
    )
    (net (code "348") (name "unconnected-(U1G-NC-PadC6)") (class "Default")
      (node (ref "U1") (pin "C6") (pinfunction "NC_C6") (pintype "bidirectional"))
    )
    (net (code "349") (name "unconnected-(U1G-NC-PadC7)") (class "Default")
      (node (ref "U1") (pin "C7") (pinfunction "NC_C7") (pintype "bidirectional"))
    )
    (net (code "350") (name "unconnected-(U1G-NC-PadC8)") (class "Default")
      (node (ref "U1") (pin "C8") (pinfunction "NC_C8") (pintype "bidirectional"))
    )
    (net (code "351") (name "unconnected-(U1G-NC-PadD1)") (class "Default")
      (node (ref "U1") (pin "D1") (pinfunction "NC_D1") (pintype "bidirectional"))
    )
    (net (code "352") (name "unconnected-(U1G-NC-PadD2)") (class "Default")
      (node (ref "U1") (pin "D2") (pinfunction "NC_D2") (pintype "bidirectional"))
    )
    (net (code "353") (name "unconnected-(U1G-NC-PadD3)") (class "Default")
      (node (ref "U1") (pin "D3") (pinfunction "NC_D3") (pintype "bidirectional"))
    )
    (net (code "354") (name "unconnected-(U1G-NC-PadD6)") (class "Default")
      (node (ref "U1") (pin "D6") (pinfunction "NC_D6") (pintype "bidirectional"))
    )
    (net (code "355") (name "unconnected-(U1G-NC-PadD7)") (class "Default")
      (node (ref "U1") (pin "D7") (pinfunction "NC_D7") (pintype "bidirectional"))
    )
    (net (code "356") (name "unconnected-(U1G-NC-PadD8)") (class "Default")
      (node (ref "U1") (pin "D8") (pinfunction "NC_D8") (pintype "bidirectional"))
    )
    (net (code "357") (name "unconnected-(U1G-NC-PadE1)") (class "Default")
      (node (ref "U1") (pin "E1") (pinfunction "NC_E1") (pintype "bidirectional"))
    )
    (net (code "358") (name "unconnected-(U1G-NC-PadE2)") (class "Default")
      (node (ref "U1") (pin "E2") (pinfunction "NC_E2") (pintype "bidirectional"))
    )
    (net (code "359") (name "unconnected-(U1G-NC-PadE3)") (class "Default")
      (node (ref "U1") (pin "E3") (pinfunction "NC_E3") (pintype "bidirectional"))
    )
    (net (code "360") (name "unconnected-(U1G-NC-PadE18)") (class "Default")
      (node (ref "U1") (pin "E18") (pinfunction "NC_E18") (pintype "bidirectional"))
    )
    (net (code "361") (name "unconnected-(U1G-NC-PadF1)") (class "Default")
      (node (ref "U1") (pin "F1") (pinfunction "NC_F1") (pintype "bidirectional"))
    )
    (net (code "362") (name "unconnected-(U1G-NC-PadF2)") (class "Default")
      (node (ref "U1") (pin "F2") (pinfunction "NC_F2") (pintype "bidirectional"))
    )
    (net (code "363") (name "unconnected-(U1G-NC-PadF3)") (class "Default")
      (node (ref "U1") (pin "F3") (pinfunction "NC_F3") (pintype "bidirectional"))
    )
    (net (code "364") (name "unconnected-(U1G-NC-PadF4)") (class "Default")
      (node (ref "U1") (pin "F4") (pinfunction "NC_F4") (pintype "bidirectional"))
    )
    (net (code "365") (name "unconnected-(U1G-NC-PadF6)") (class "Default")
      (node (ref "U1") (pin "F6") (pinfunction "NC_F6") (pintype "bidirectional"))
    )
    (net (code "366") (name "unconnected-(U1G-NC-PadF7)") (class "Default")
      (node (ref "U1") (pin "F7") (pinfunction "NC_F7") (pintype "bidirectional"))
    )
    (net (code "367") (name "unconnected-(U1G-NC-PadF20)") (class "Default")
      (node (ref "U1") (pin "F20") (pinfunction "NC_F20") (pintype "bidirectional"))
    )
    (net (code "368") (name "unconnected-(U1G-NC-PadG1)") (class "Default")
      (node (ref "U1") (pin "G1") (pinfunction "NC_G1") (pintype "bidirectional"))
    )
    (net (code "369") (name "unconnected-(U1G-NC-PadG2)") (class "Default")
      (node (ref "U1") (pin "G2") (pinfunction "NC_G2") (pintype "bidirectional"))
    )
    (net (code "370") (name "unconnected-(U1G-NC-PadG3)") (class "Default")
      (node (ref "U1") (pin "G3") (pinfunction "NC_G3") (pintype "bidirectional"))
    )
    (net (code "371") (name "unconnected-(U1G-NC-PadG4)") (class "Default")
      (node (ref "U1") (pin "G4") (pinfunction "NC_G4") (pintype "bidirectional"))
    )
    (net (code "372") (name "unconnected-(U1G-NC-PadG6)") (class "Default")
      (node (ref "U1") (pin "G6") (pinfunction "NC_G6") (pintype "bidirectional"))
    )
    (net (code "373") (name "unconnected-(U1G-NC-PadG7)") (class "Default")
      (node (ref "U1") (pin "G7") (pinfunction "NC_G7") (pintype "bidirectional"))
    )
    (net (code "374") (name "unconnected-(U1G-NC-PadG10)") (class "Default")
      (node (ref "U1") (pin "G10") (pinfunction "NC_G10") (pintype "bidirectional"))
    )
    (net (code "375") (name "unconnected-(U1G-NC-PadG11)") (class "Default")
      (node (ref "U1") (pin "G11") (pinfunction "NC_G11") (pintype "bidirectional"))
    )
    (net (code "376") (name "unconnected-(U1G-NC-PadG18)") (class "Default")
      (node (ref "U1") (pin "G18") (pinfunction "NC_G18") (pintype "bidirectional"))
    )
    (net (code "377") (name "unconnected-(U1G-NC-PadG19)") (class "Default")
      (node (ref "U1") (pin "G19") (pinfunction "NC_G19") (pintype "bidirectional"))
    )
    (net (code "378") (name "unconnected-(U1G-NC-PadG20)") (class "Default")
      (node (ref "U1") (pin "G20") (pinfunction "NC_G20") (pintype "bidirectional"))
    )
    (net (code "379") (name "unconnected-(U1G-NC-PadH4)") (class "Default")
      (node (ref "U1") (pin "H4") (pinfunction "NC_H4") (pintype "bidirectional"))
    )
    (net (code "380") (name "unconnected-(U1G-NC-PadH6)") (class "Default")
      (node (ref "U1") (pin "H6") (pinfunction "NC_H6") (pintype "bidirectional"))
    )
    (net (code "381") (name "unconnected-(U1G-NC-PadH9)") (class "Default")
      (node (ref "U1") (pin "H9") (pinfunction "NC_H9") (pintype "bidirectional"))
    )
    (net (code "382") (name "unconnected-(U1G-NC-PadH10)") (class "Default")
      (node (ref "U1") (pin "H10") (pinfunction "NC_H10") (pintype "bidirectional"))
    )
    (net (code "383") (name "unconnected-(U1G-NC-PadH11)") (class "Default")
      (node (ref "U1") (pin "H11") (pinfunction "NC_H11") (pintype "bidirectional"))
    )
    (net (code "384") (name "unconnected-(U1G-NC-PadH12)") (class "Default")
      (node (ref "U1") (pin "H12") (pinfunction "NC_H12") (pintype "bidirectional"))
    )
    (net (code "385") (name "unconnected-(U1G-NC-PadH13)") (class "Default")
      (node (ref "U1") (pin "H13") (pinfunction "NC_H13") (pintype "bidirectional"))
    )
    (net (code "386") (name "unconnected-(U1G-NC-PadH18)") (class "Default")
      (node (ref "U1") (pin "H18") (pinfunction "NC_H18") (pintype "bidirectional"))
    )
    (net (code "387") (name "unconnected-(U1G-NC-PadH19)") (class "Default")
      (node (ref "U1") (pin "H19") (pinfunction "NC_H19") (pintype "bidirectional"))
    )
    (net (code "388") (name "unconnected-(U1G-NC-PadH20)") (class "Default")
      (node (ref "U1") (pin "H20") (pinfunction "NC_H20") (pintype "bidirectional"))
    )
    (net (code "389") (name "unconnected-(U1G-NC-PadJ4)") (class "Default")
      (node (ref "U1") (pin "J4") (pinfunction "NC_J4") (pintype "bidirectional"))
    )
    (net (code "390") (name "unconnected-(U1G-NC-PadJ6)") (class "Default")
      (node (ref "U1") (pin "J6") (pinfunction "NC_J6") (pintype "bidirectional"))
    )
    (net (code "391") (name "unconnected-(U1G-NC-PadJ18)") (class "Default")
      (node (ref "U1") (pin "J18") (pinfunction "NC_J18") (pintype "bidirectional"))
    )
    (net (code "392") (name "unconnected-(U1G-NC-PadJ19)") (class "Default")
      (node (ref "U1") (pin "J19") (pinfunction "NC_J19") (pintype "bidirectional"))
    )
    (net (code "393") (name "unconnected-(U1G-NC-PadJ20)") (class "Default")
      (node (ref "U1") (pin "J20") (pinfunction "NC_J20") (pintype "bidirectional"))
    )
    (net (code "394") (name "unconnected-(U1G-NC-PadK4)") (class "Default")
      (node (ref "U1") (pin "K4") (pinfunction "NC_K4") (pintype "bidirectional"))
    )
    (net (code "395") (name "unconnected-(U1G-NC-PadL4)") (class "Default")
      (node (ref "U1") (pin "L4") (pinfunction "NC_L4") (pintype "bidirectional"))
    )
    (net (code "396") (name "unconnected-(U1G-NC-PadL17)") (class "Default")
      (node (ref "U1") (pin "L17") (pinfunction "NC_L17") (pintype "bidirectional"))
    )
    (net (code "397") (name "unconnected-(U1G-NC-PadM4)") (class "Default")
      (node (ref "U1") (pin "M4") (pinfunction "NC_M4") (pintype "bidirectional"))
    )
    (net (code "398") (name "unconnected-(U1G-NC-PadM6)") (class "Default")
      (node (ref "U1") (pin "M6") (pinfunction "NC_M6") (pintype "bidirectional"))
    )
    (net (code "399") (name "unconnected-(U1G-NC-PadM17)") (class "Default")
      (node (ref "U1") (pin "M17") (pinfunction "NC_M17") (pintype "bidirectional"))
    )
    (net (code "400") (name "unconnected-(U1G-NC-PadN4)") (class "Default")
      (node (ref "U1") (pin "N4") (pinfunction "NC_N4") (pintype "bidirectional"))
    )
    (net (code "401") (name "unconnected-(U1G-NC-PadN17)") (class "Default")
      (node (ref "U1") (pin "N17") (pinfunction "NC_N17") (pintype "bidirectional"))
    )
    (net (code "402") (name "unconnected-(U1G-NC-PadP4)") (class "Default")
      (node (ref "U1") (pin "P4") (pinfunction "NC_P4") (pintype "bidirectional"))
    )
    (net (code "403") (name "unconnected-(U1G-NC-PadP17)") (class "Default")
      (node (ref "U1") (pin "P17") (pinfunction "NC_P17") (pintype "bidirectional"))
    )
    (net (code "404") (name "unconnected-(U1G-NC-PadR4)") (class "Default")
      (node (ref "U1") (pin "R4") (pinfunction "NC_R4") (pintype "bidirectional"))
    )
    (net (code "405") (name "unconnected-(U1G-NC-PadR6)") (class "Default")
      (node (ref "U1") (pin "R6") (pinfunction "NC_R6") (pintype "bidirectional"))
    )
    (net (code "406") (name "unconnected-(U1G-NC-PadR7)") (class "Default")
      (node (ref "U1") (pin "R7") (pinfunction "NC_R7") (pintype "bidirectional"))
    )
    (net (code "407") (name "unconnected-(U1G-NC-PadR8)") (class "Default")
      (node (ref "U1") (pin "R8") (pinfunction "NC_R8") (pintype "bidirectional"))
    )
    (net (code "408") (name "unconnected-(U1G-NC-PadR13)") (class "Default")
      (node (ref "U1") (pin "R13") (pinfunction "NC_R13") (pintype "bidirectional"))
    )
    (net (code "409") (name "unconnected-(U1G-NC-PadR14)") (class "Default")
      (node (ref "U1") (pin "R14") (pinfunction "NC_R14") (pintype "bidirectional"))
    )
    (net (code "410") (name "unconnected-(U1G-NC-PadR15)") (class "Default")
      (node (ref "U1") (pin "R15") (pinfunction "NC_R15") (pintype "bidirectional"))
    )
    (net (code "411") (name "unconnected-(U1G-NC-PadR17)") (class "Default")
      (node (ref "U1") (pin "R17") (pinfunction "NC_R17") (pintype "bidirectional"))
    )
    (net (code "412") (name "unconnected-(U1G-NC-PadU11)") (class "Default")
      (node (ref "U1") (pin "U11") (pinfunction "NC_U11") (pintype "bidirectional"))
    )
    (net (code "413") (name "unconnected-(U2-N.C.-Pad5)") (class "Default")
      (node (ref "U2") (pin "5") (pinfunction "N.C._5") (pintype "no_connect"))
    )
    (net (code "414") (name "unconnected-(U16-NC-Pad7)") (class "Default")
      (node (ref "U16") (pin "7") (pinfunction "NC_7") (pintype "bidirectional"))
    )
    (net (code "415") (name "unconnected-(U16-NC-Pad10)") (class "Default")
      (node (ref "U16") (pin "10") (pinfunction "NC_10") (pintype "bidirectional"))
    )
    (net (code "416") (name "unconnected-(U16-NC-Pad11)") (class "Default")
      (node (ref "U16") (pin "11") (pinfunction "NC_11") (pintype "bidirectional"))
    )
    (net (code "417") (name "unconnected-(U16-NC-Pad13)") (class "Default")
      (node (ref "U16") (pin "13") (pinfunction "NC_13") (pintype "bidirectional"))
    )
    (net (code "418") (name "unconnected-(U16-NC-Pad14)") (class "Default")
      (node (ref "U16") (pin "14") (pinfunction "NC_14") (pintype "bidirectional"))
    )
    (net (code "419") (name "unconnected-(U16-NC-Pad15)") (class "Default")
      (node (ref "U16") (pin "15") (pinfunction "NC_15") (pintype "bidirectional"))
    )
    (net (code "420") (name "unconnected-(U16-NC-Pad16)") (class "Default")
      (node (ref "U16") (pin "16") (pinfunction "NC_16") (pintype "bidirectional"))
    )
    (net (code "421") (name "unconnected-(U16-NC-Pad25)") (class "Default")
      (node (ref "U16") (pin "25") (pinfunction "NC_25") (pintype "bidirectional"))
    )
    (net (code "422") (name "unconnected-(U16-NC-Pad26)") (class "Default")
      (node (ref "U16") (pin "26") (pinfunction "NC_26") (pintype "bidirectional"))
    )
    (net (code "423") (name "unconnected-(U16-NC-Pad27)") (class "Default")
      (node (ref "U16") (pin "27") (pinfunction "NC_27") (pintype "bidirectional"))
    )
    (net (code "424") (name "unconnected-(U16-NC-Pad28)") (class "Default")
      (node (ref "U16") (pin "28") (pinfunction "NC_28") (pintype "bidirectional"))
    )
    (net (code "425") (name "unconnected-(U16-NC-Pad31)") (class "Default")
      (node (ref "U16") (pin "31") (pinfunction "NC_31") (pintype "bidirectional"))
    )
    (net (code "426") (name "unconnected-(U16-PAD-Pad33)") (class "Default")
      (node (ref "U16") (pin "33") (pinfunction "PAD_33") (pintype "bidirectional"))
    )
    (net (code "427") (name "unconnected-(U28-S-Pad8)") (class "Default")
      (node (ref "U28") (pin "8") (pinfunction "S_8") (pintype "input"))
    )
    (net (code "428") (name "unconnected-(U40-NC-Pad10)") (class "Default")
      (node (ref "U40") (pin "10") (pinfunction "NC_10") (pintype "passive"))
    )
    (net (code "429") (name "unconnected-(VREG4-BYPASS-Pad4)") (class "Default")
      (node (ref "VREG4") (pin "4") (pinfunction "BYPASS_4") (pintype "passive"))
    )
    (net (code "430") (name "unconnected-(X2-NC-Pad7)") (class "Default")
      (node (ref "X2") (pin "7") (pinfunction "NC_7") (pintype "passive"))
    )
    (net (code "431") (name "unconnected-(X4-NC-Pad6)") (class "Default")
      (node (ref "X4") (pin "6") (pinfunction "NC_6") (pintype "bidirectional"))
    )
    (net (code "432") (name "unconnected-(X6-Pad2)") (class "Default")
      (node (ref "X6") (pin "2") (pinfunction "2_2") (pintype "bidirectional"))
    )
    (net (code "433") (name "unconnected-(X6-Pad3)") (class "Default")
      (node (ref "X6") (pin "3") (pinfunction "3_3") (pintype "bidirectional"))
    )
    (net (code "434") (name "unconnected-(X6-Pad6)") (class "Default")
      (node (ref "X6") (pin "6") (pinfunction "6_6") (pintype "bidirectional"))
    )
  )
)
